# quantum_AnalougeEngine_V5_1.net
KiCad netlist of a schematic drawn in EAGLE
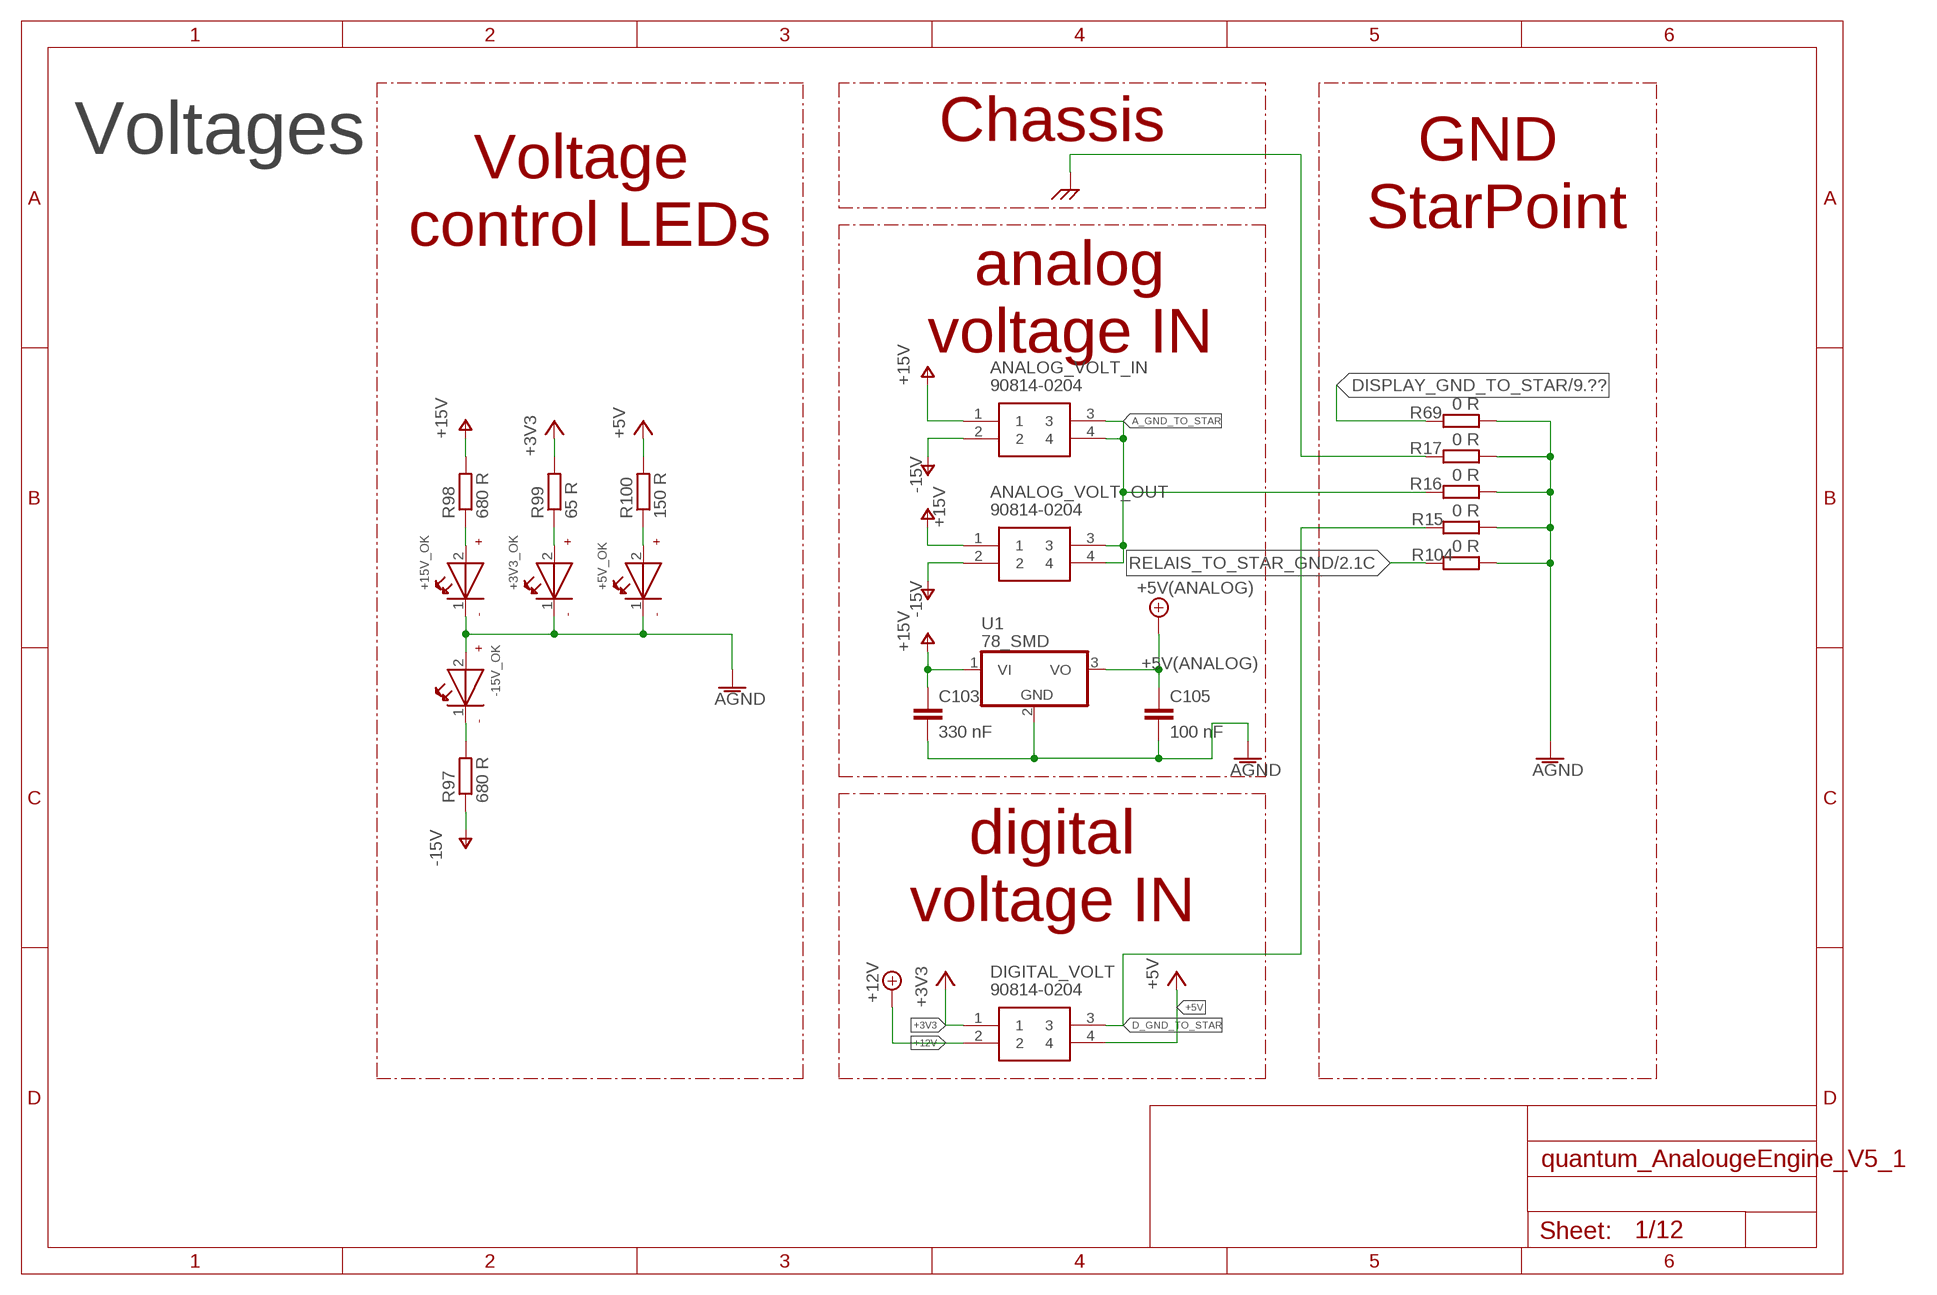
[diagram p0: schematic, sheet 1]
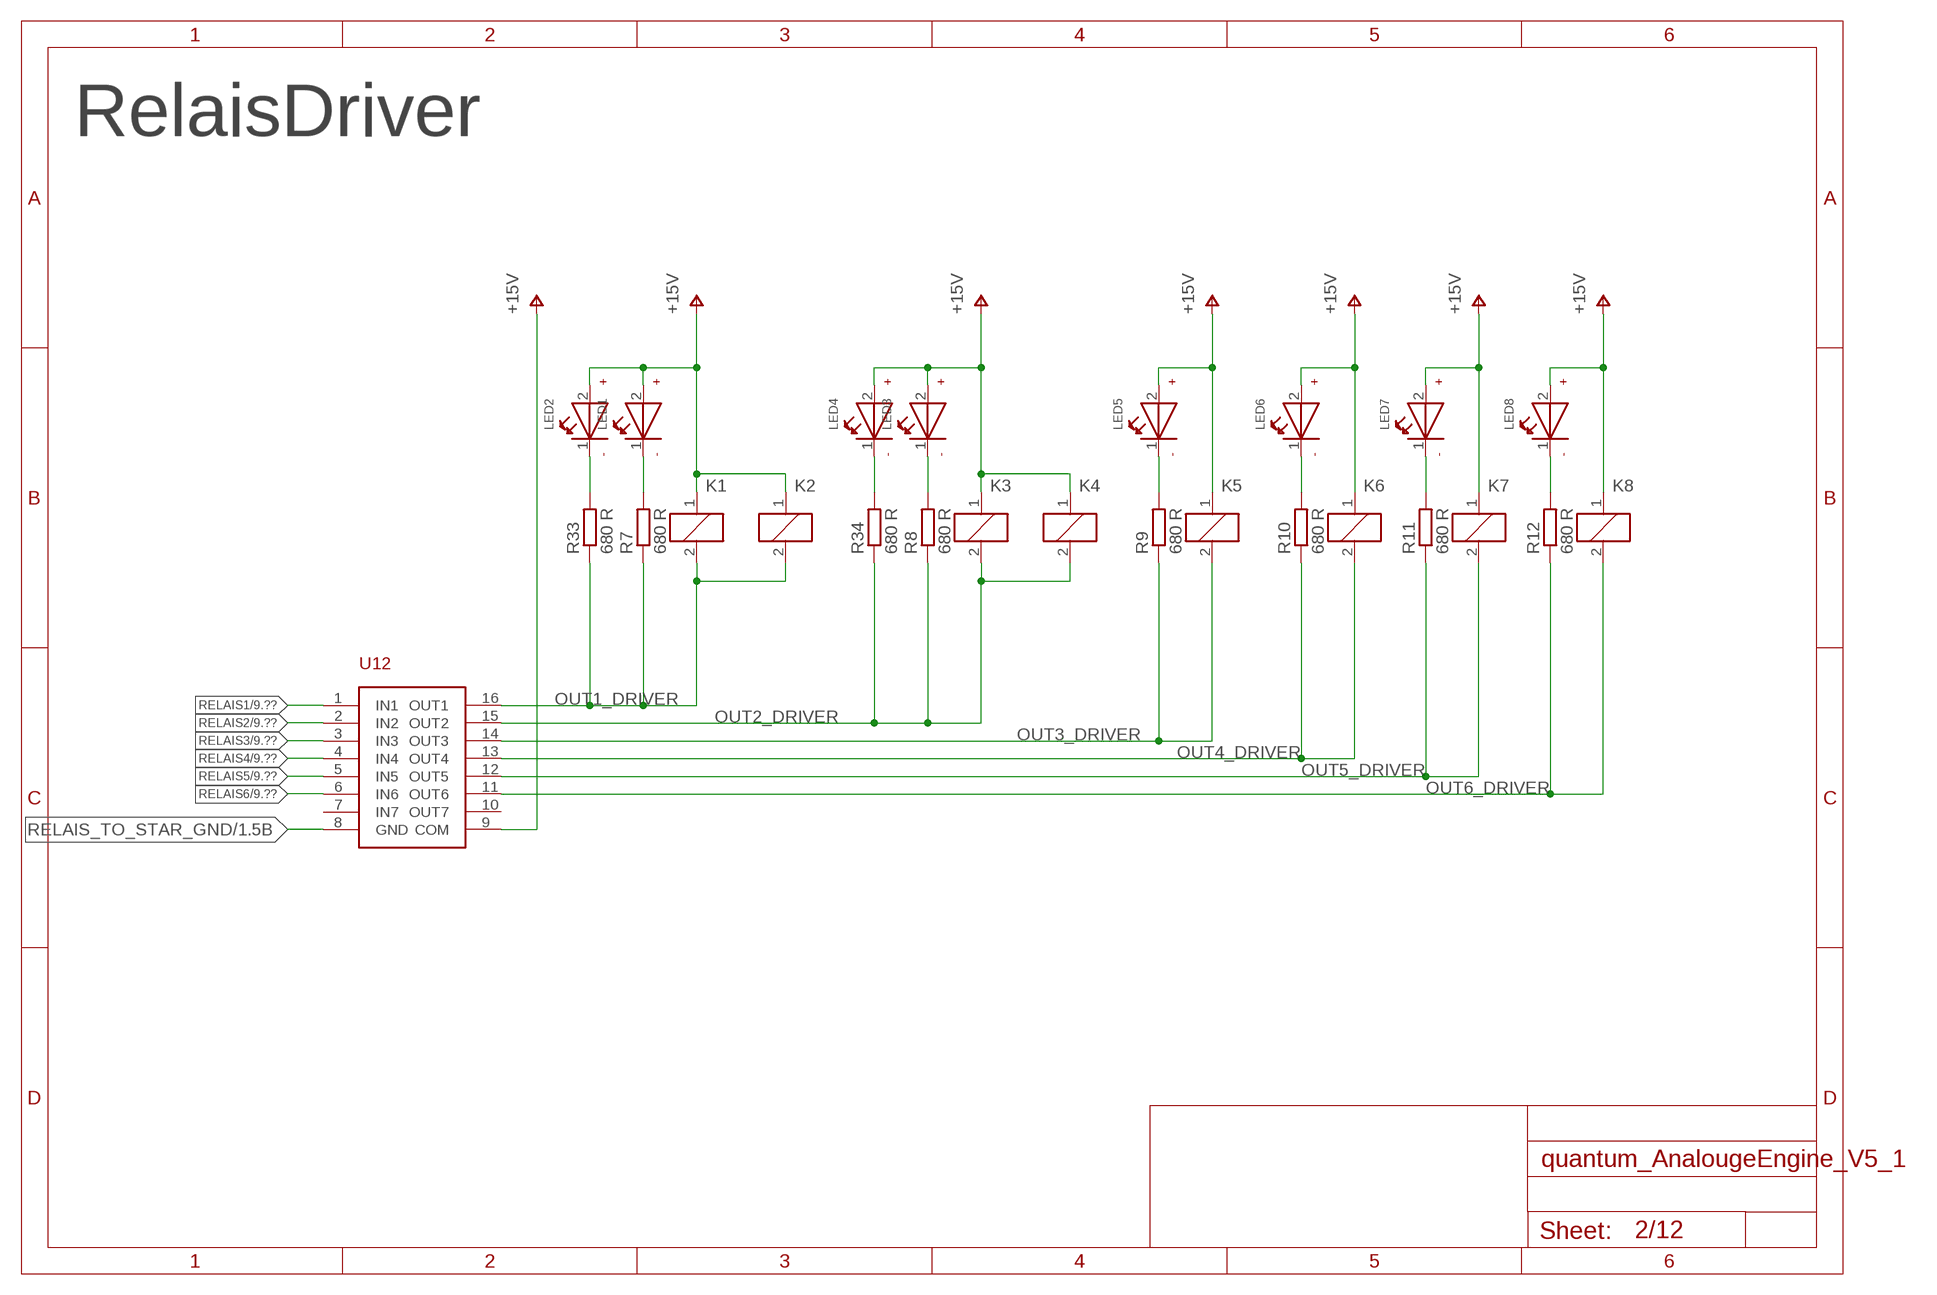
[diagram p1: schematic, sheet 2]
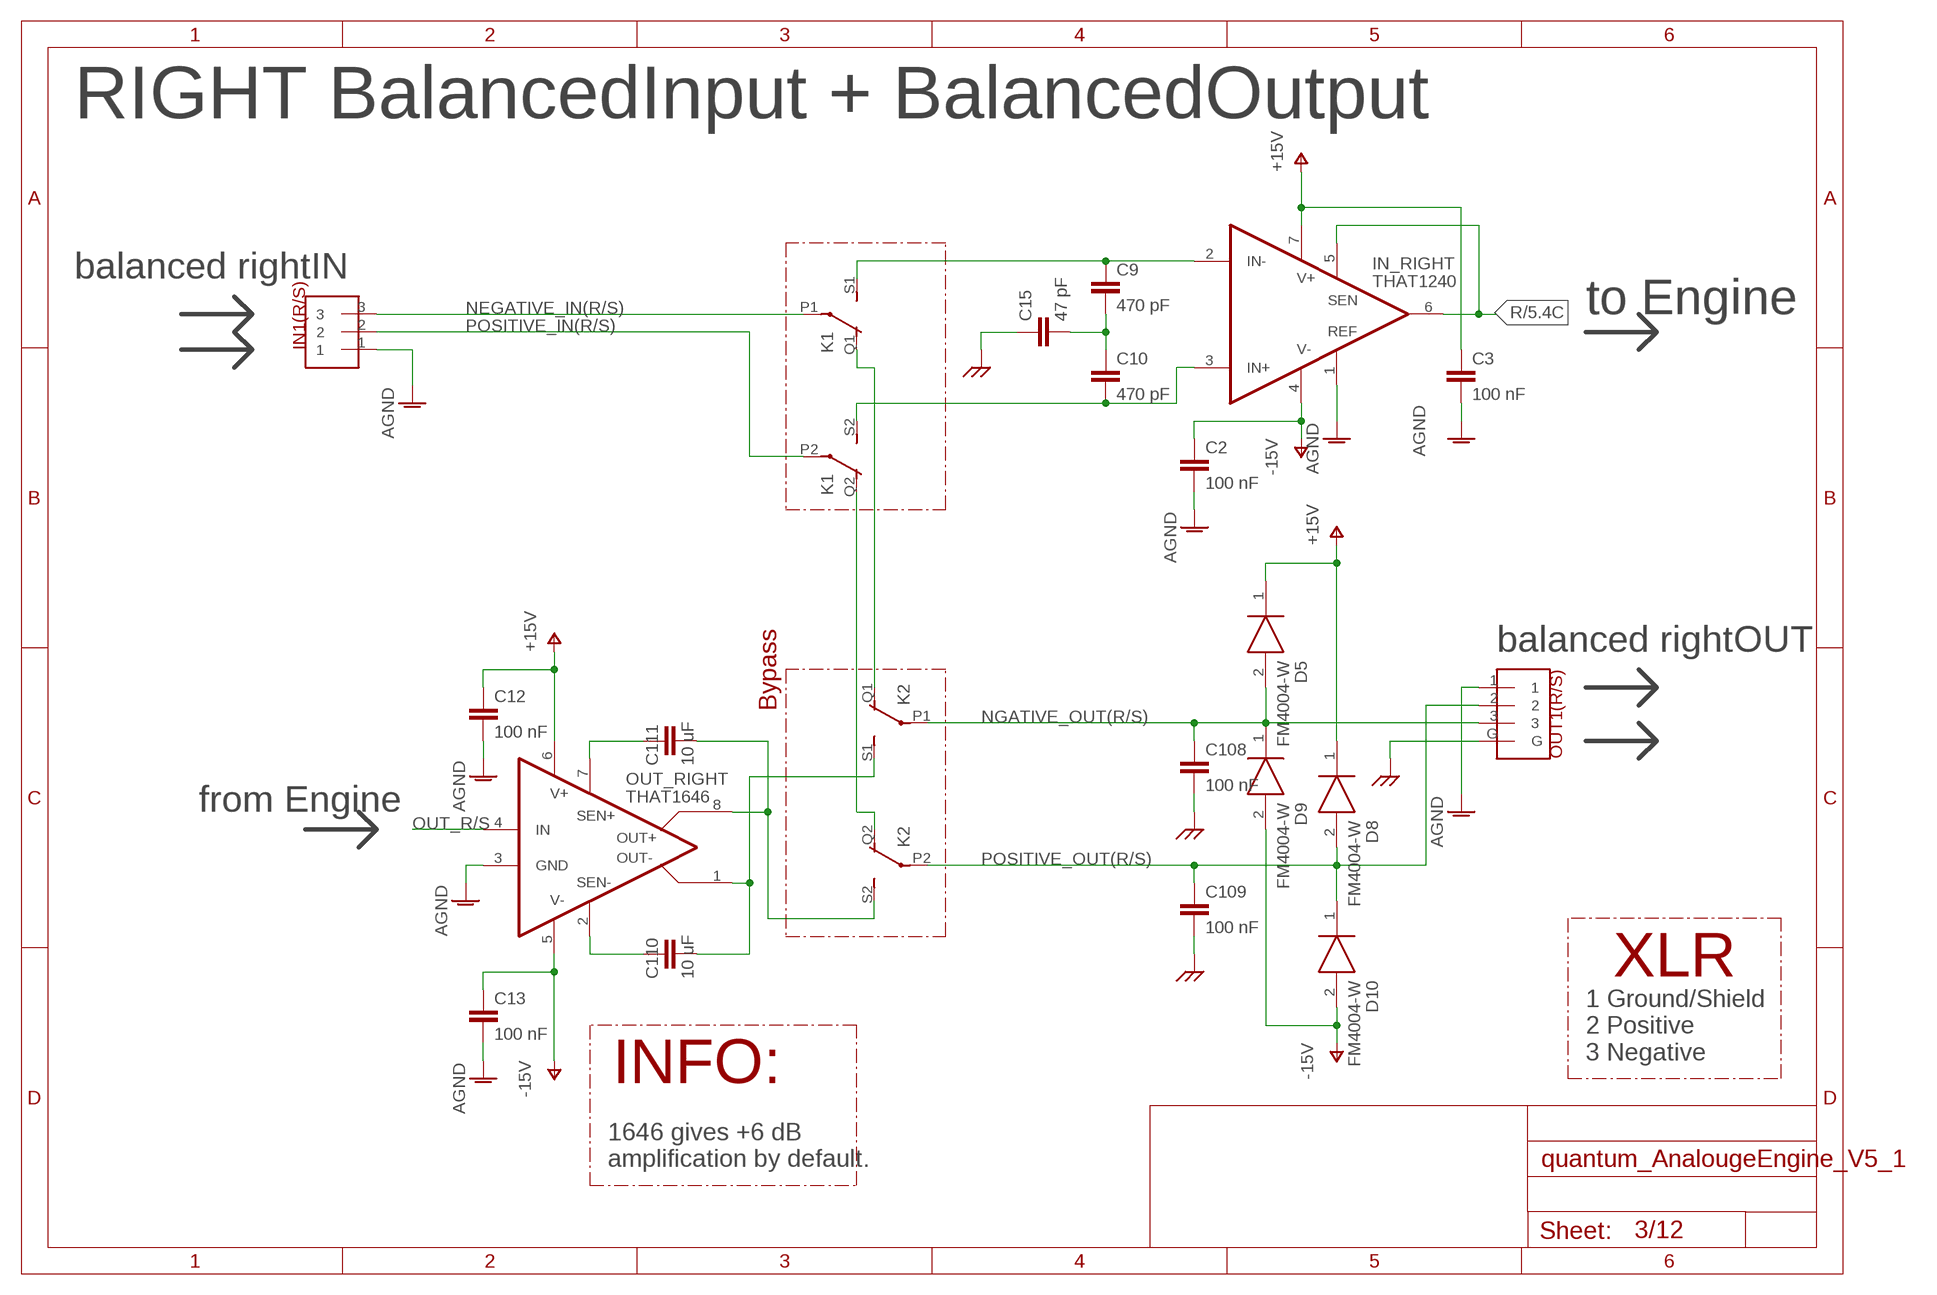
[diagram p2: schematic, sheet 3]
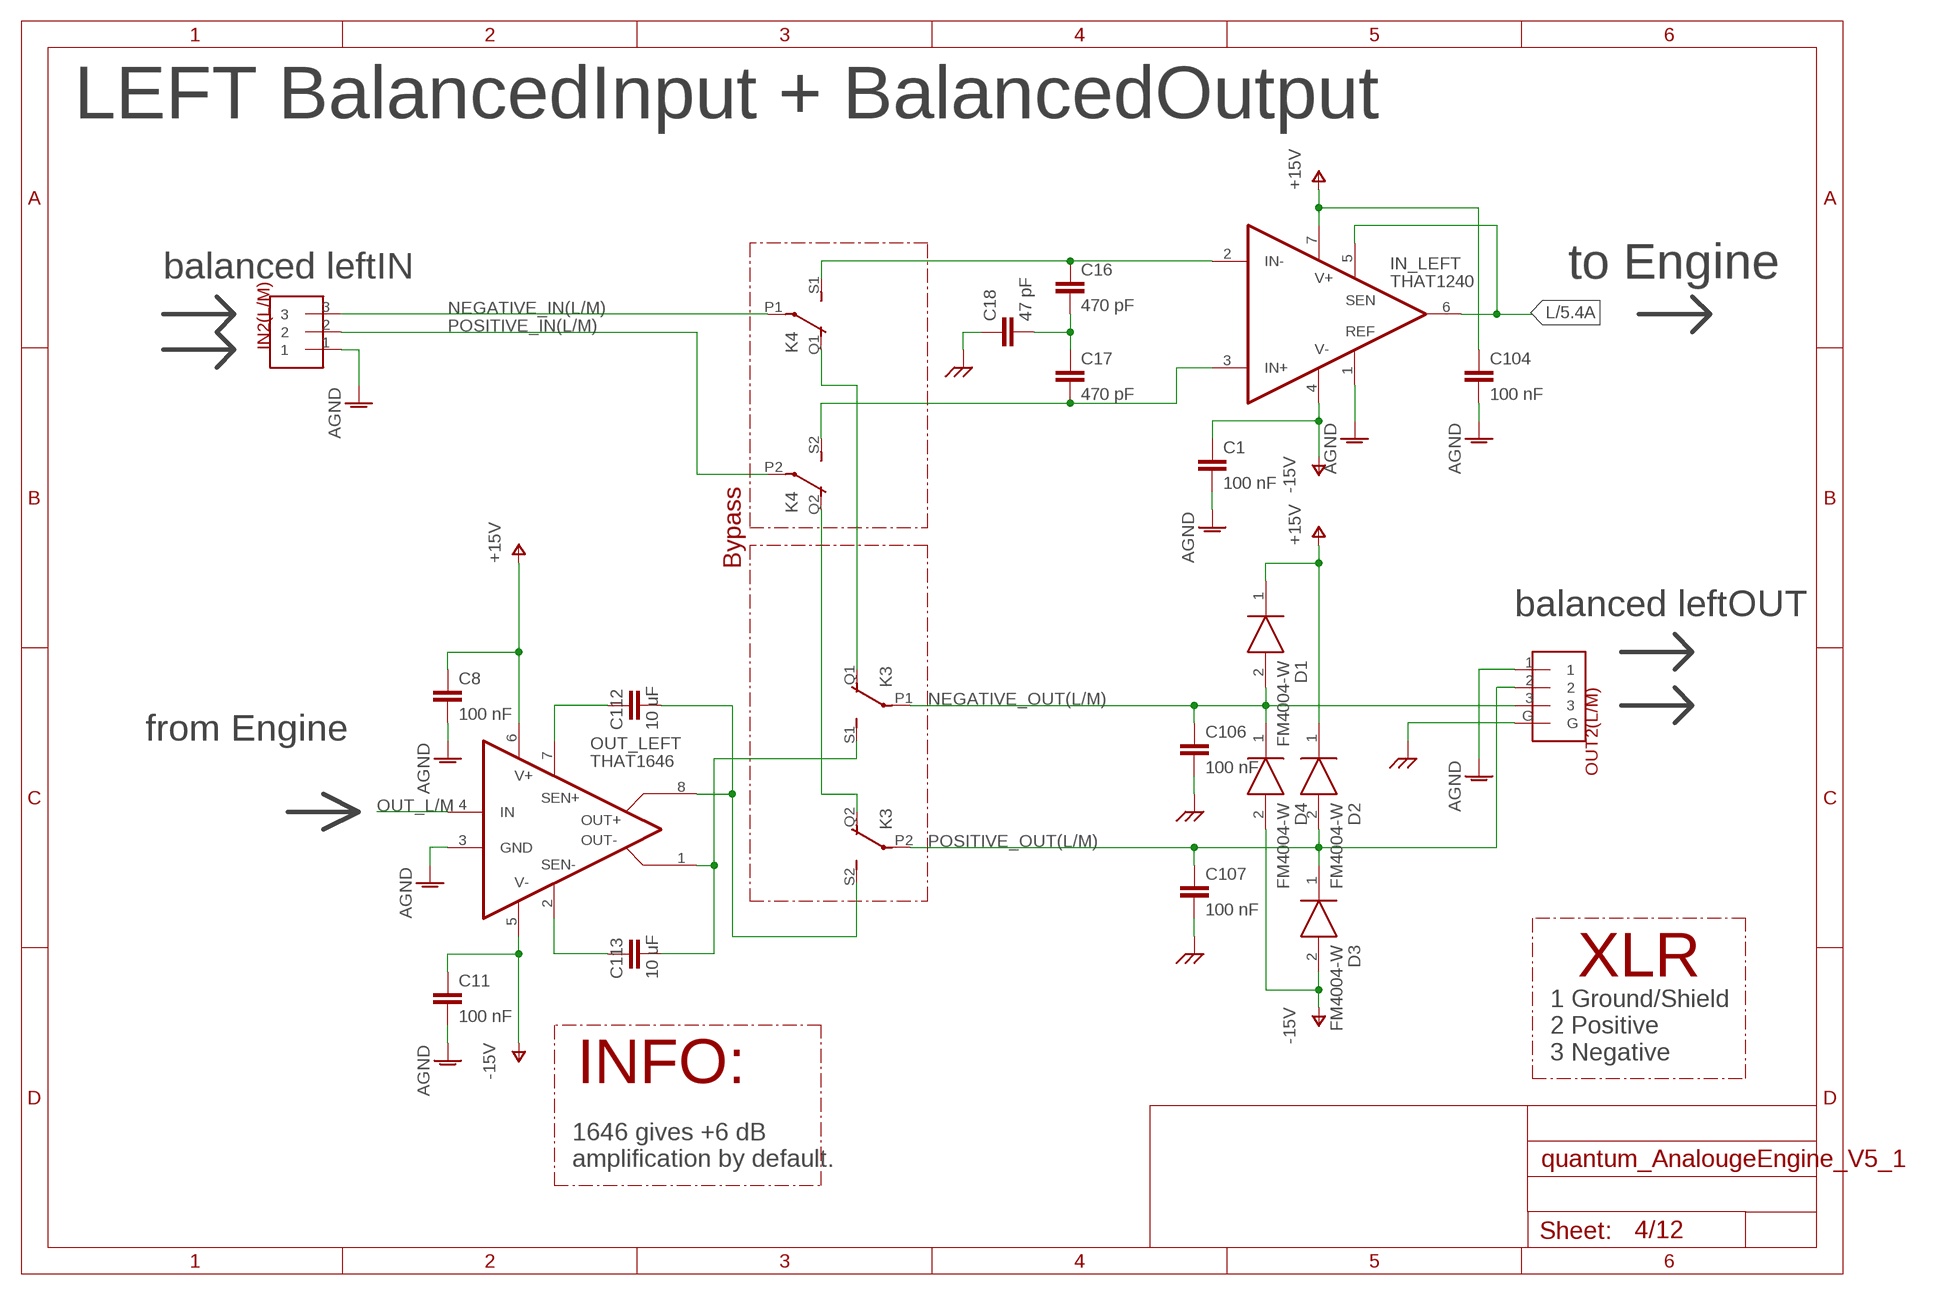
[diagram p3: schematic, sheet 4]
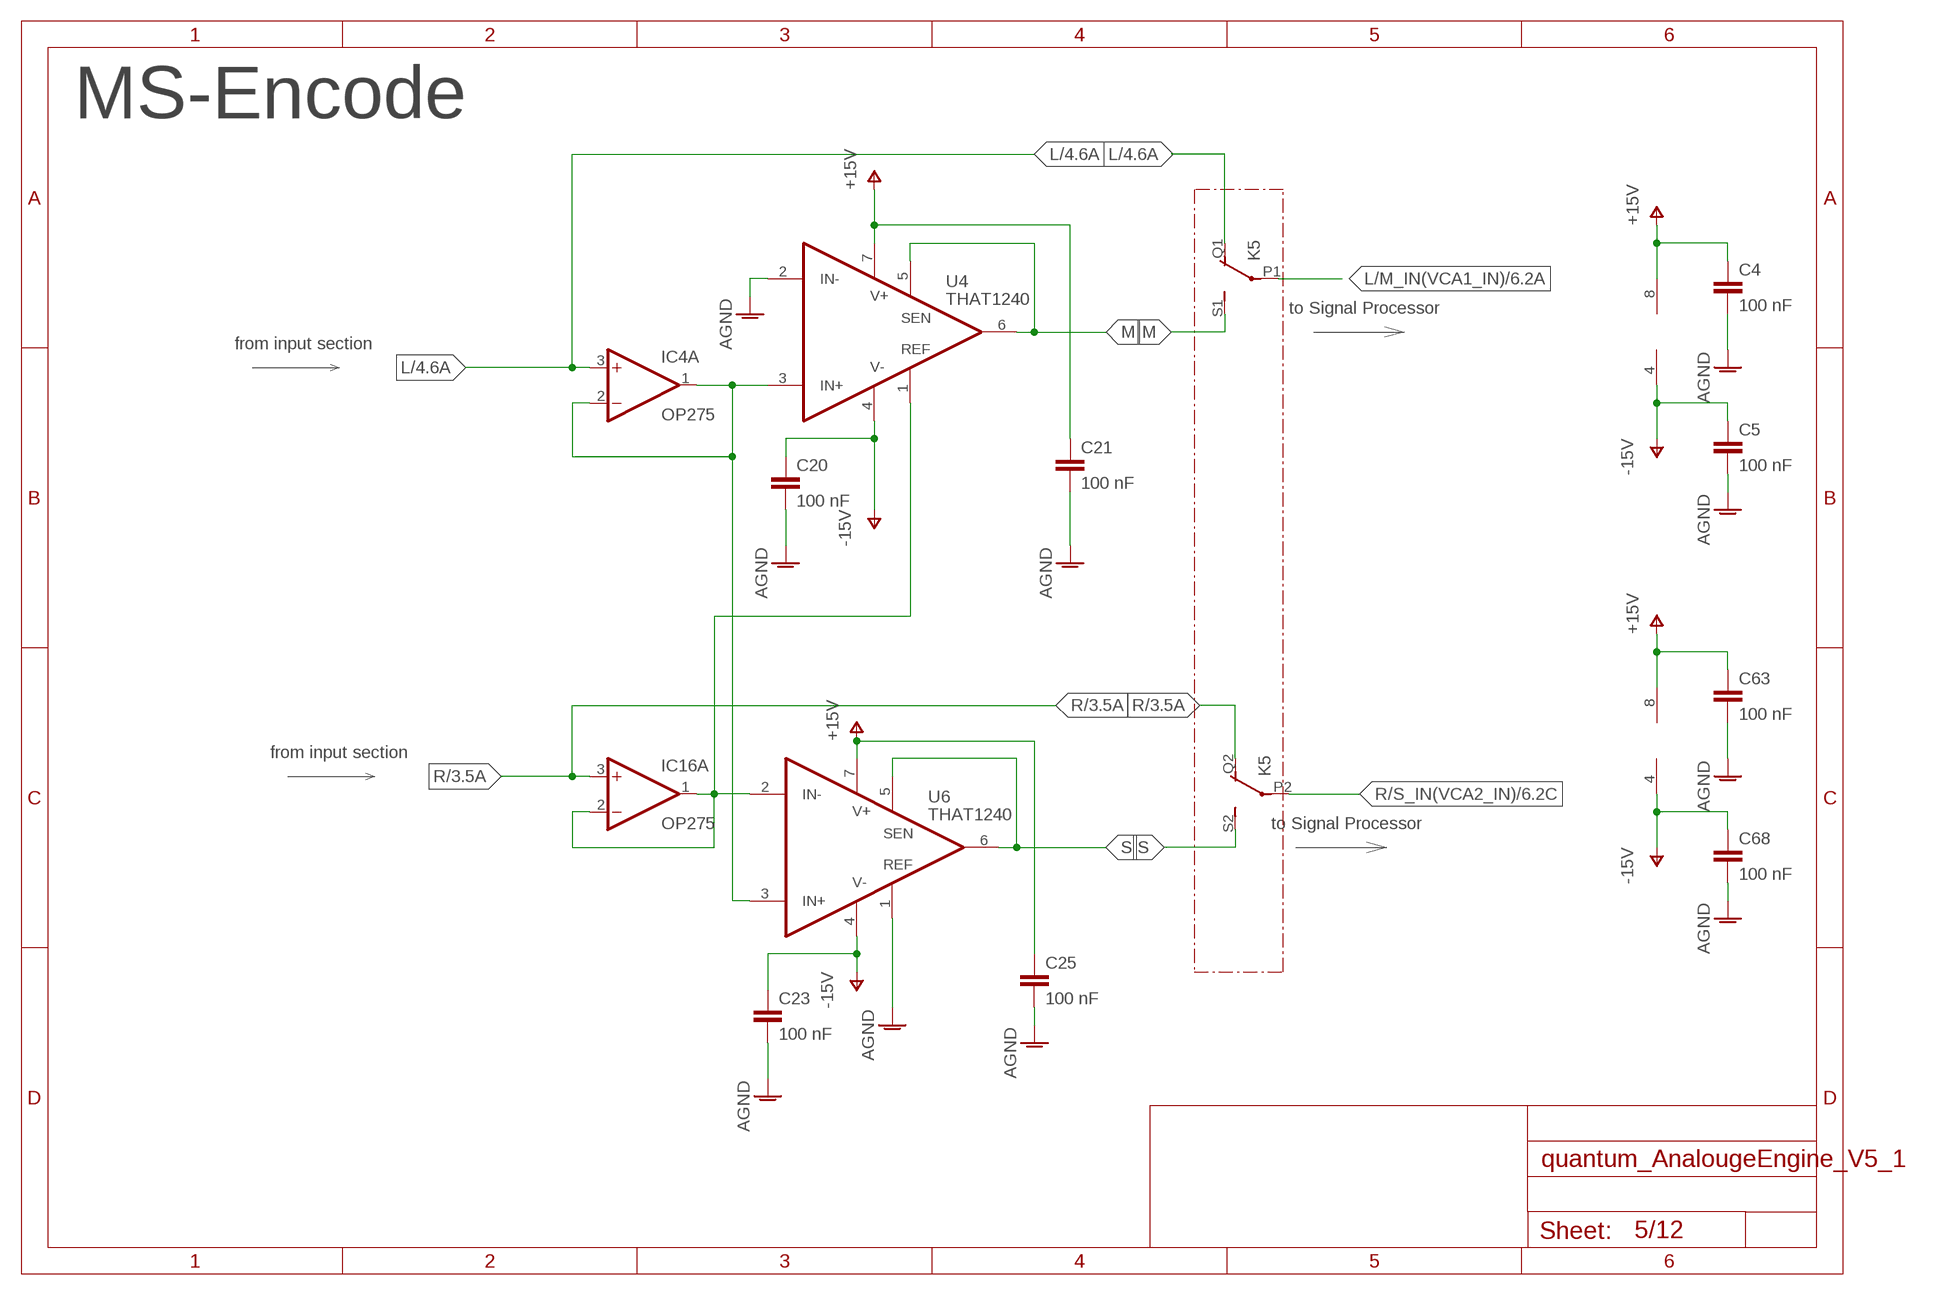
[diagram p4: schematic, sheet 5]
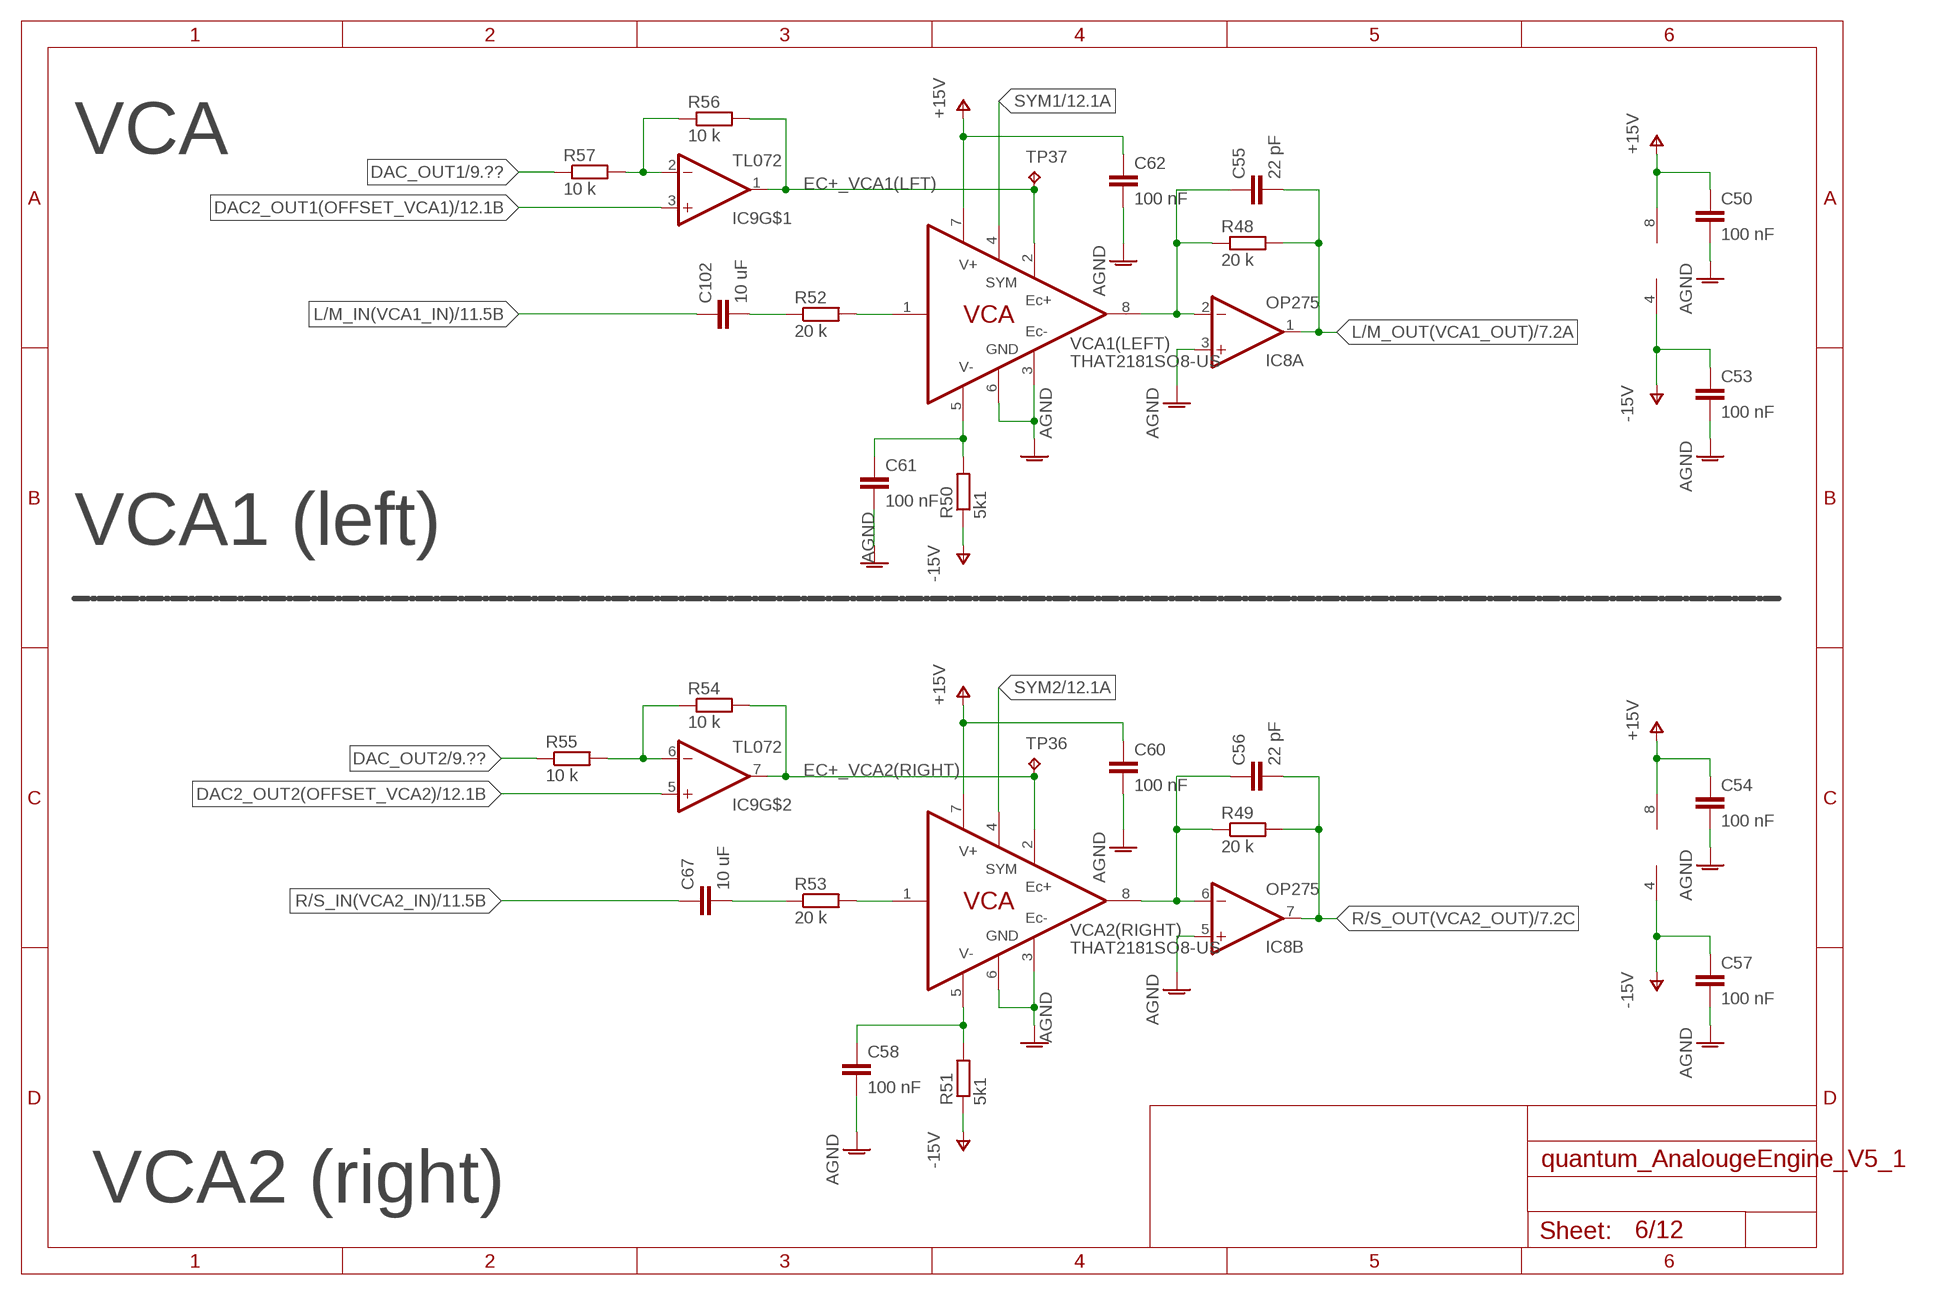
[diagram p5: schematic, sheet 6]
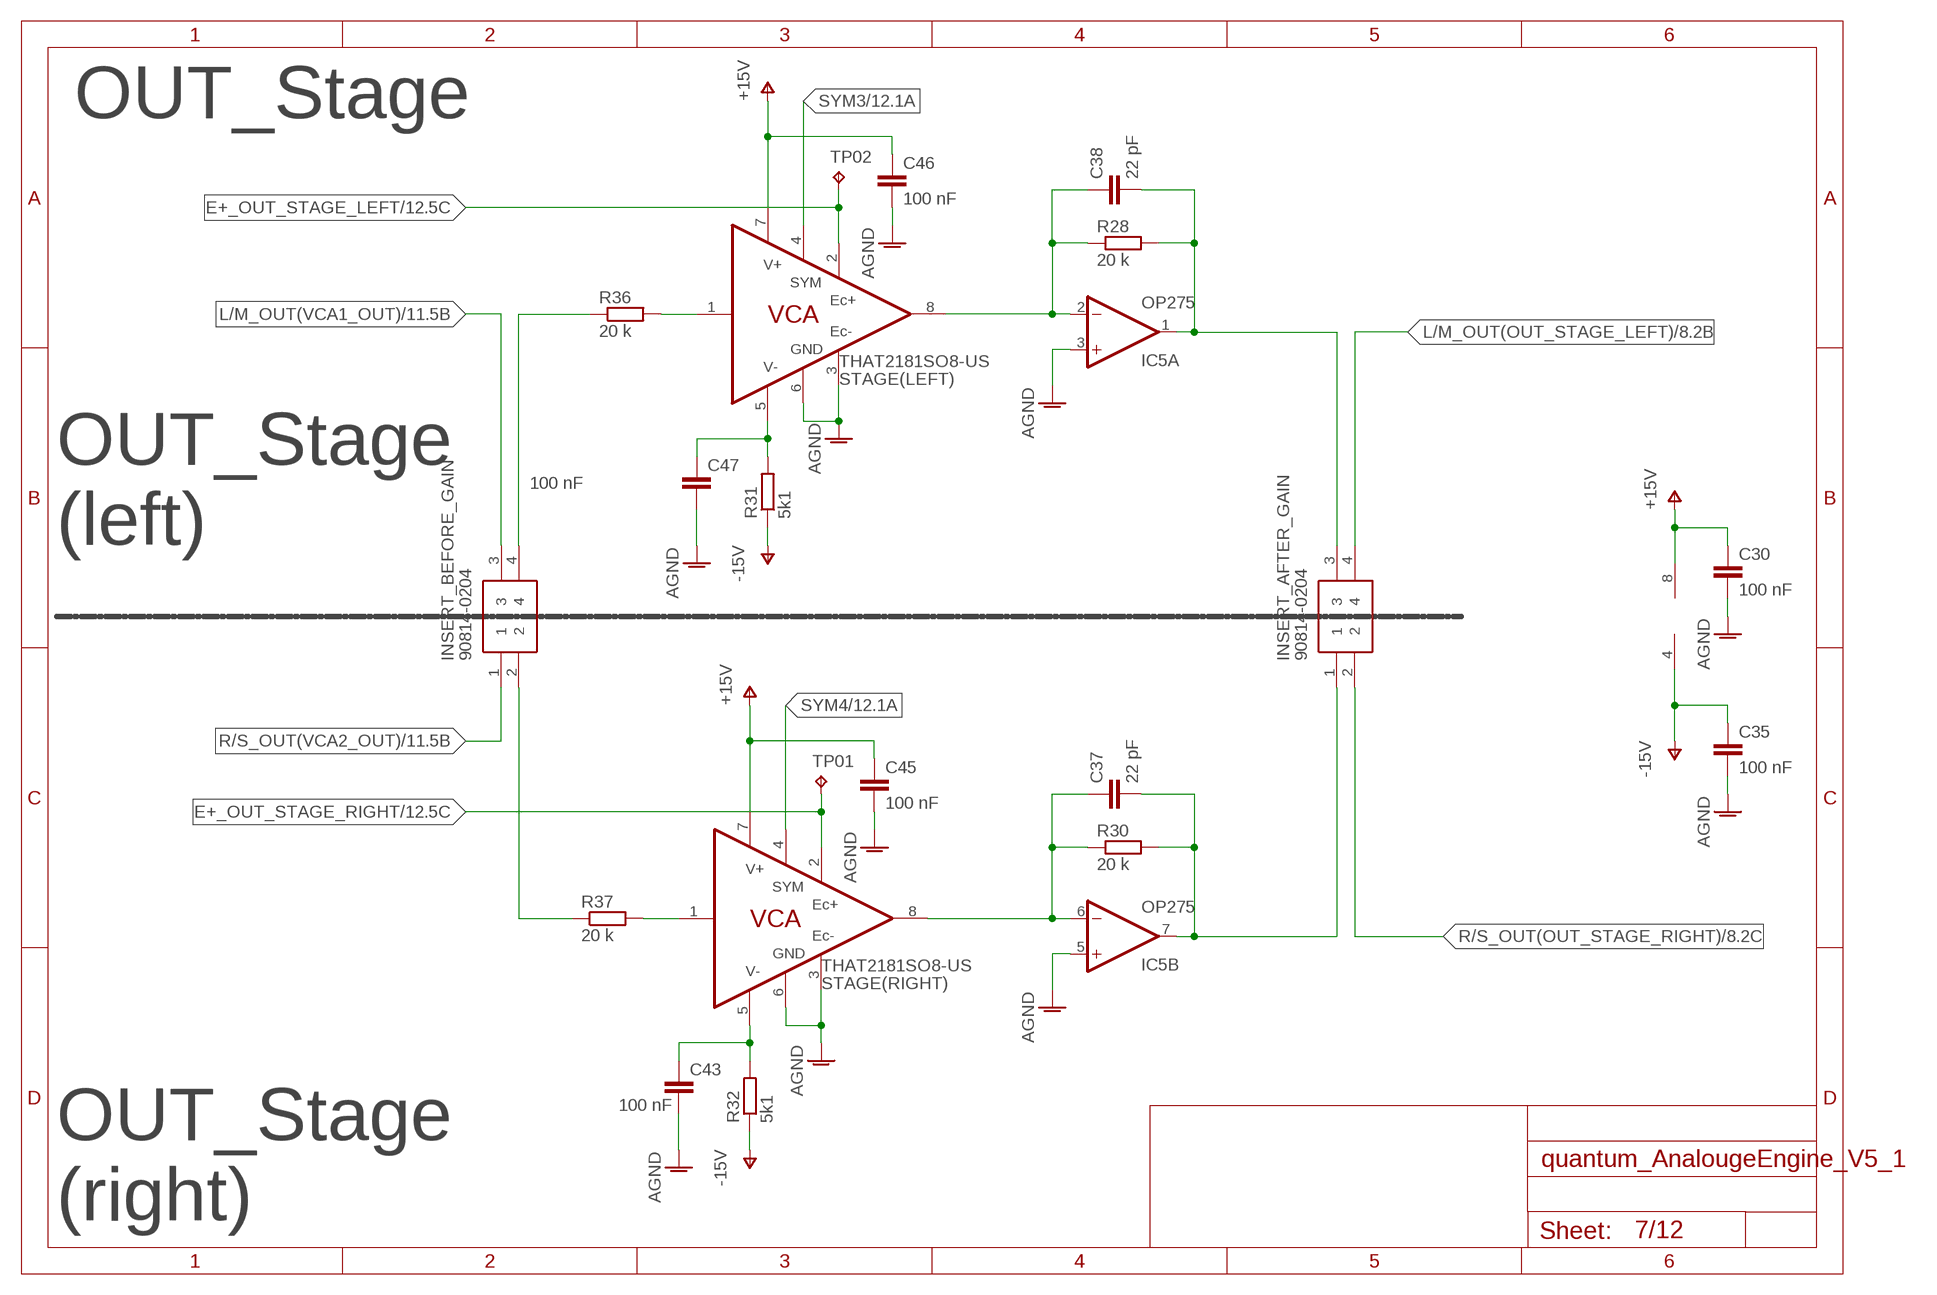
[diagram p6: schematic, sheet 7]
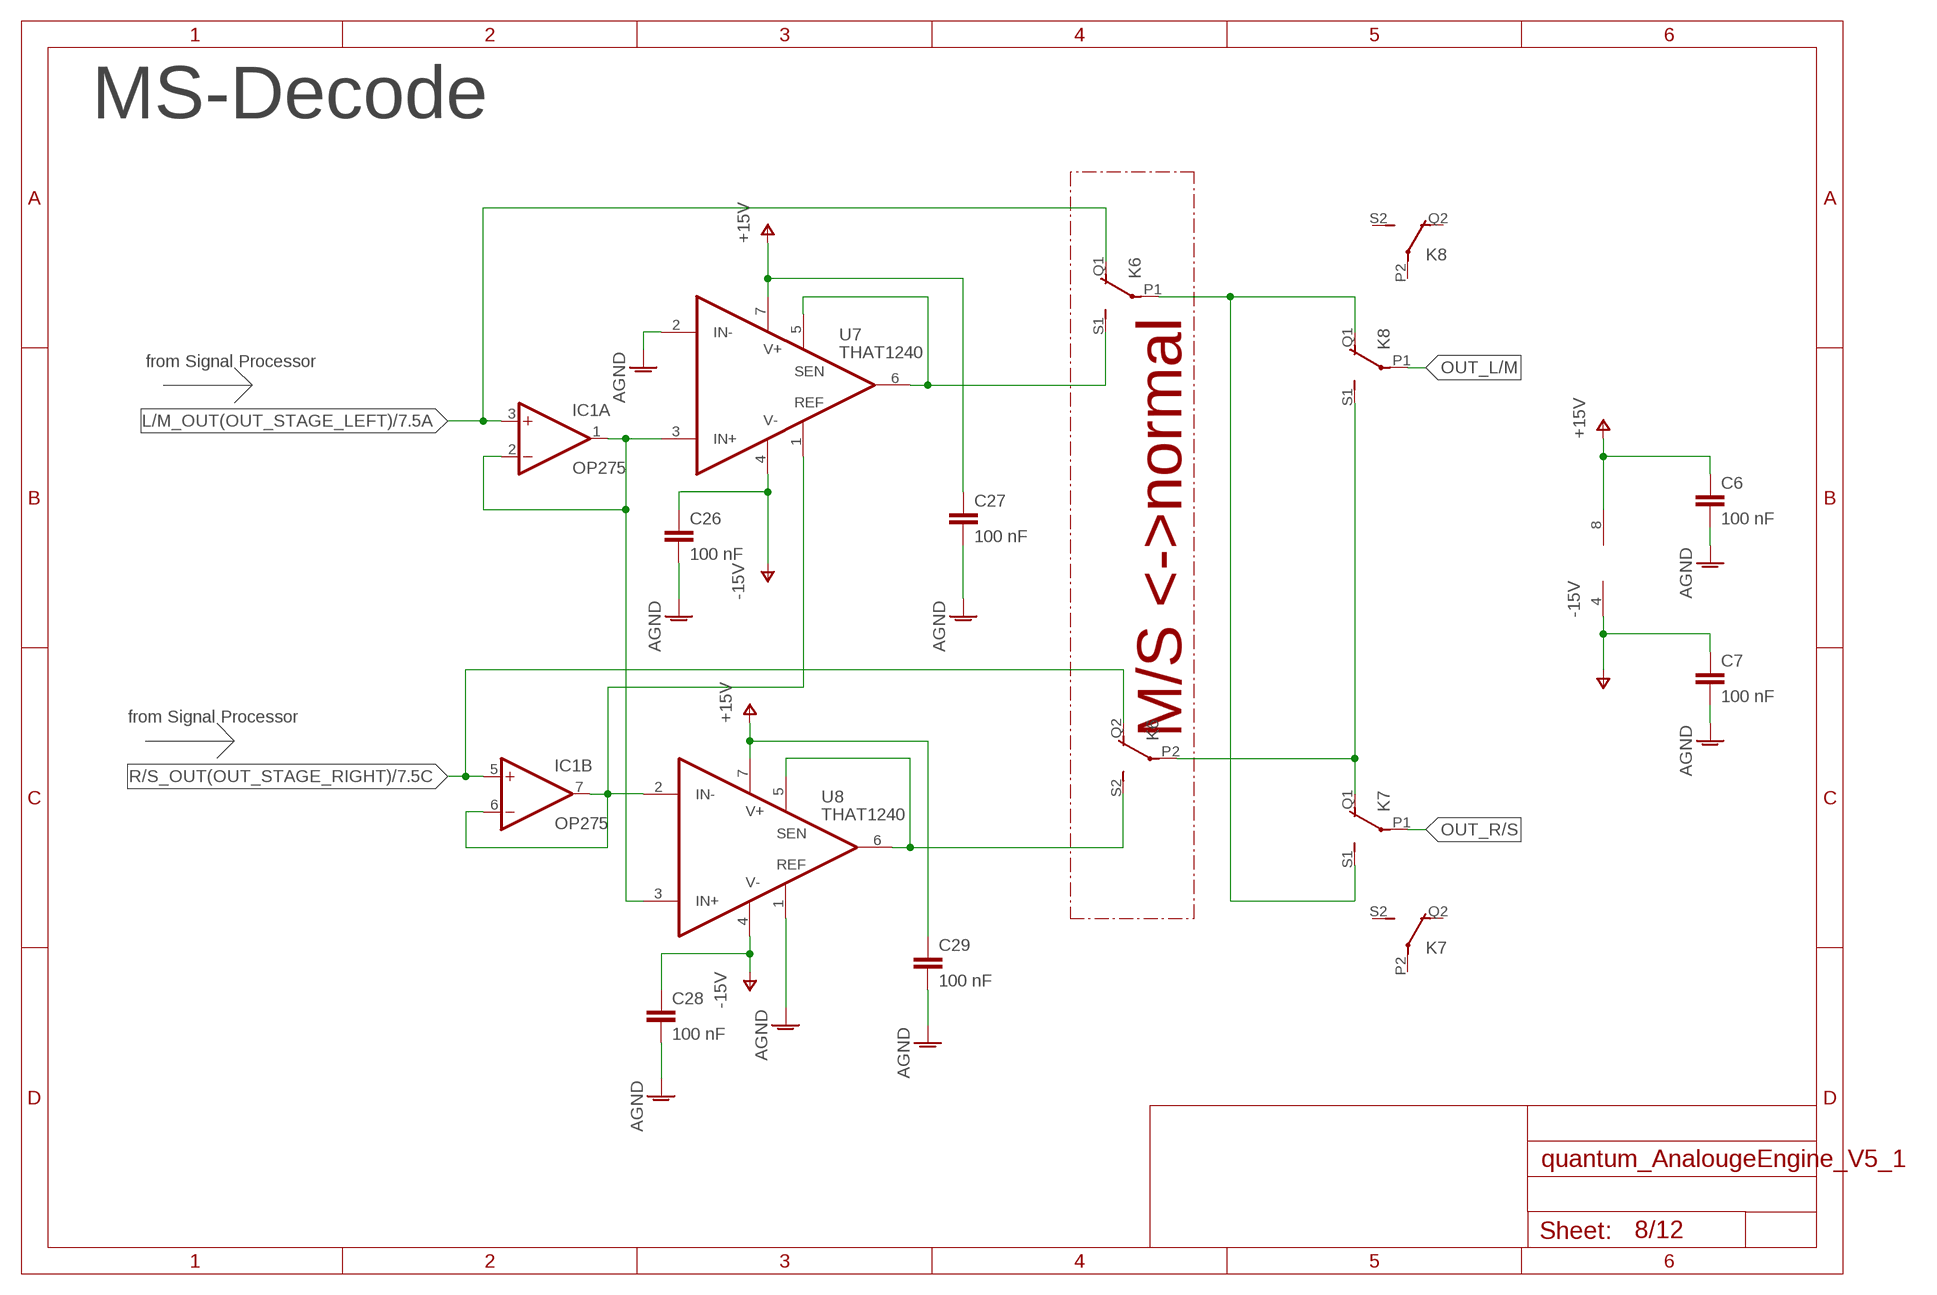
[diagram p7: schematic, sheet 8]
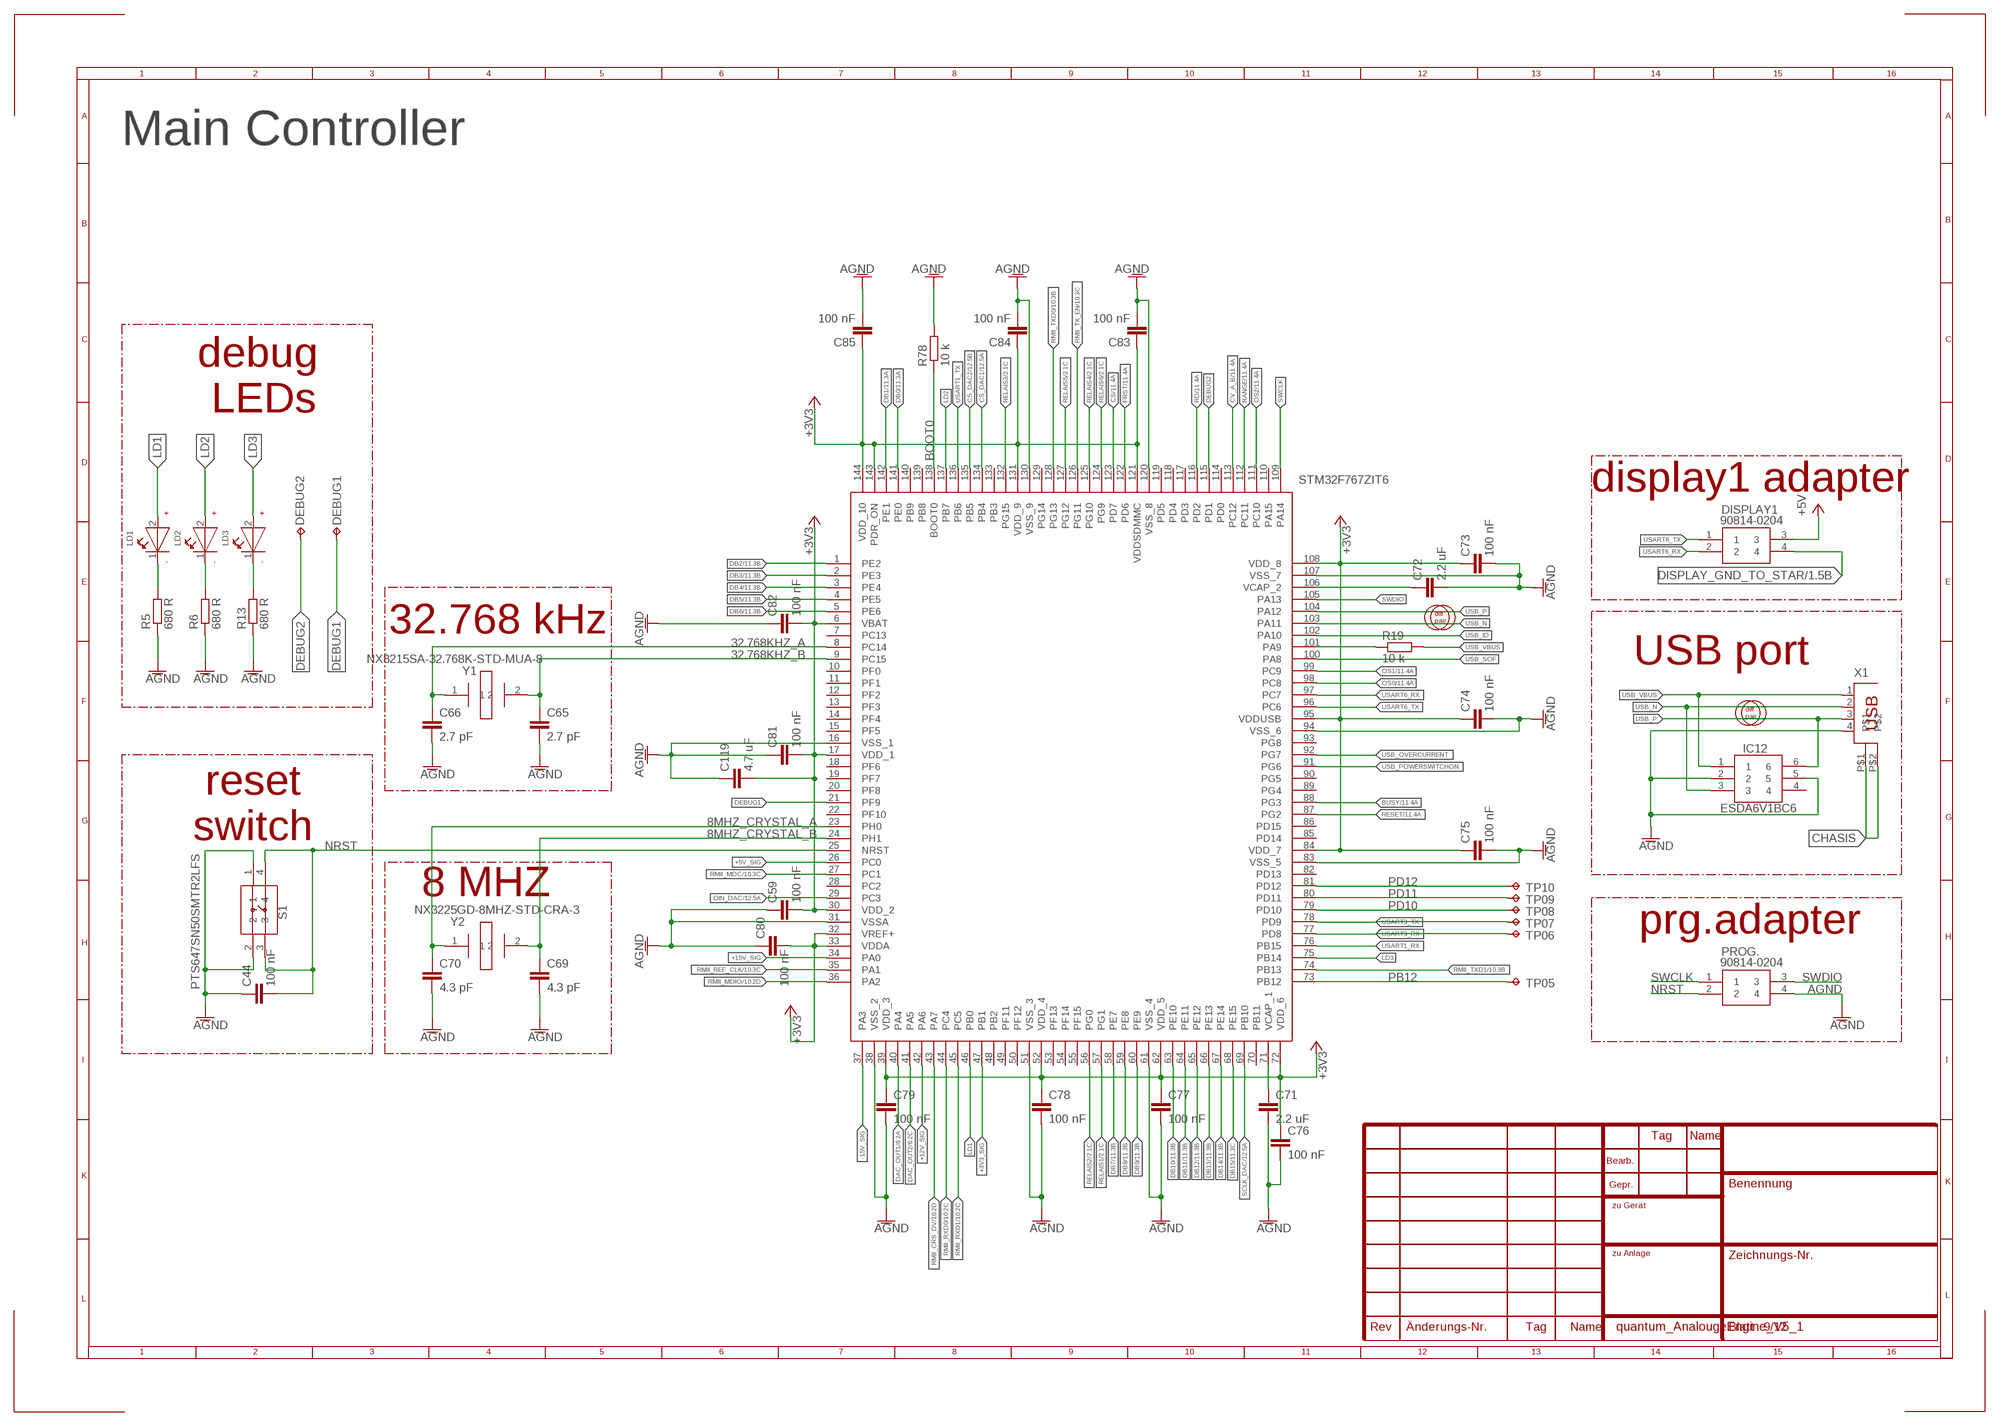
[diagram p8: schematic, sheet 9]
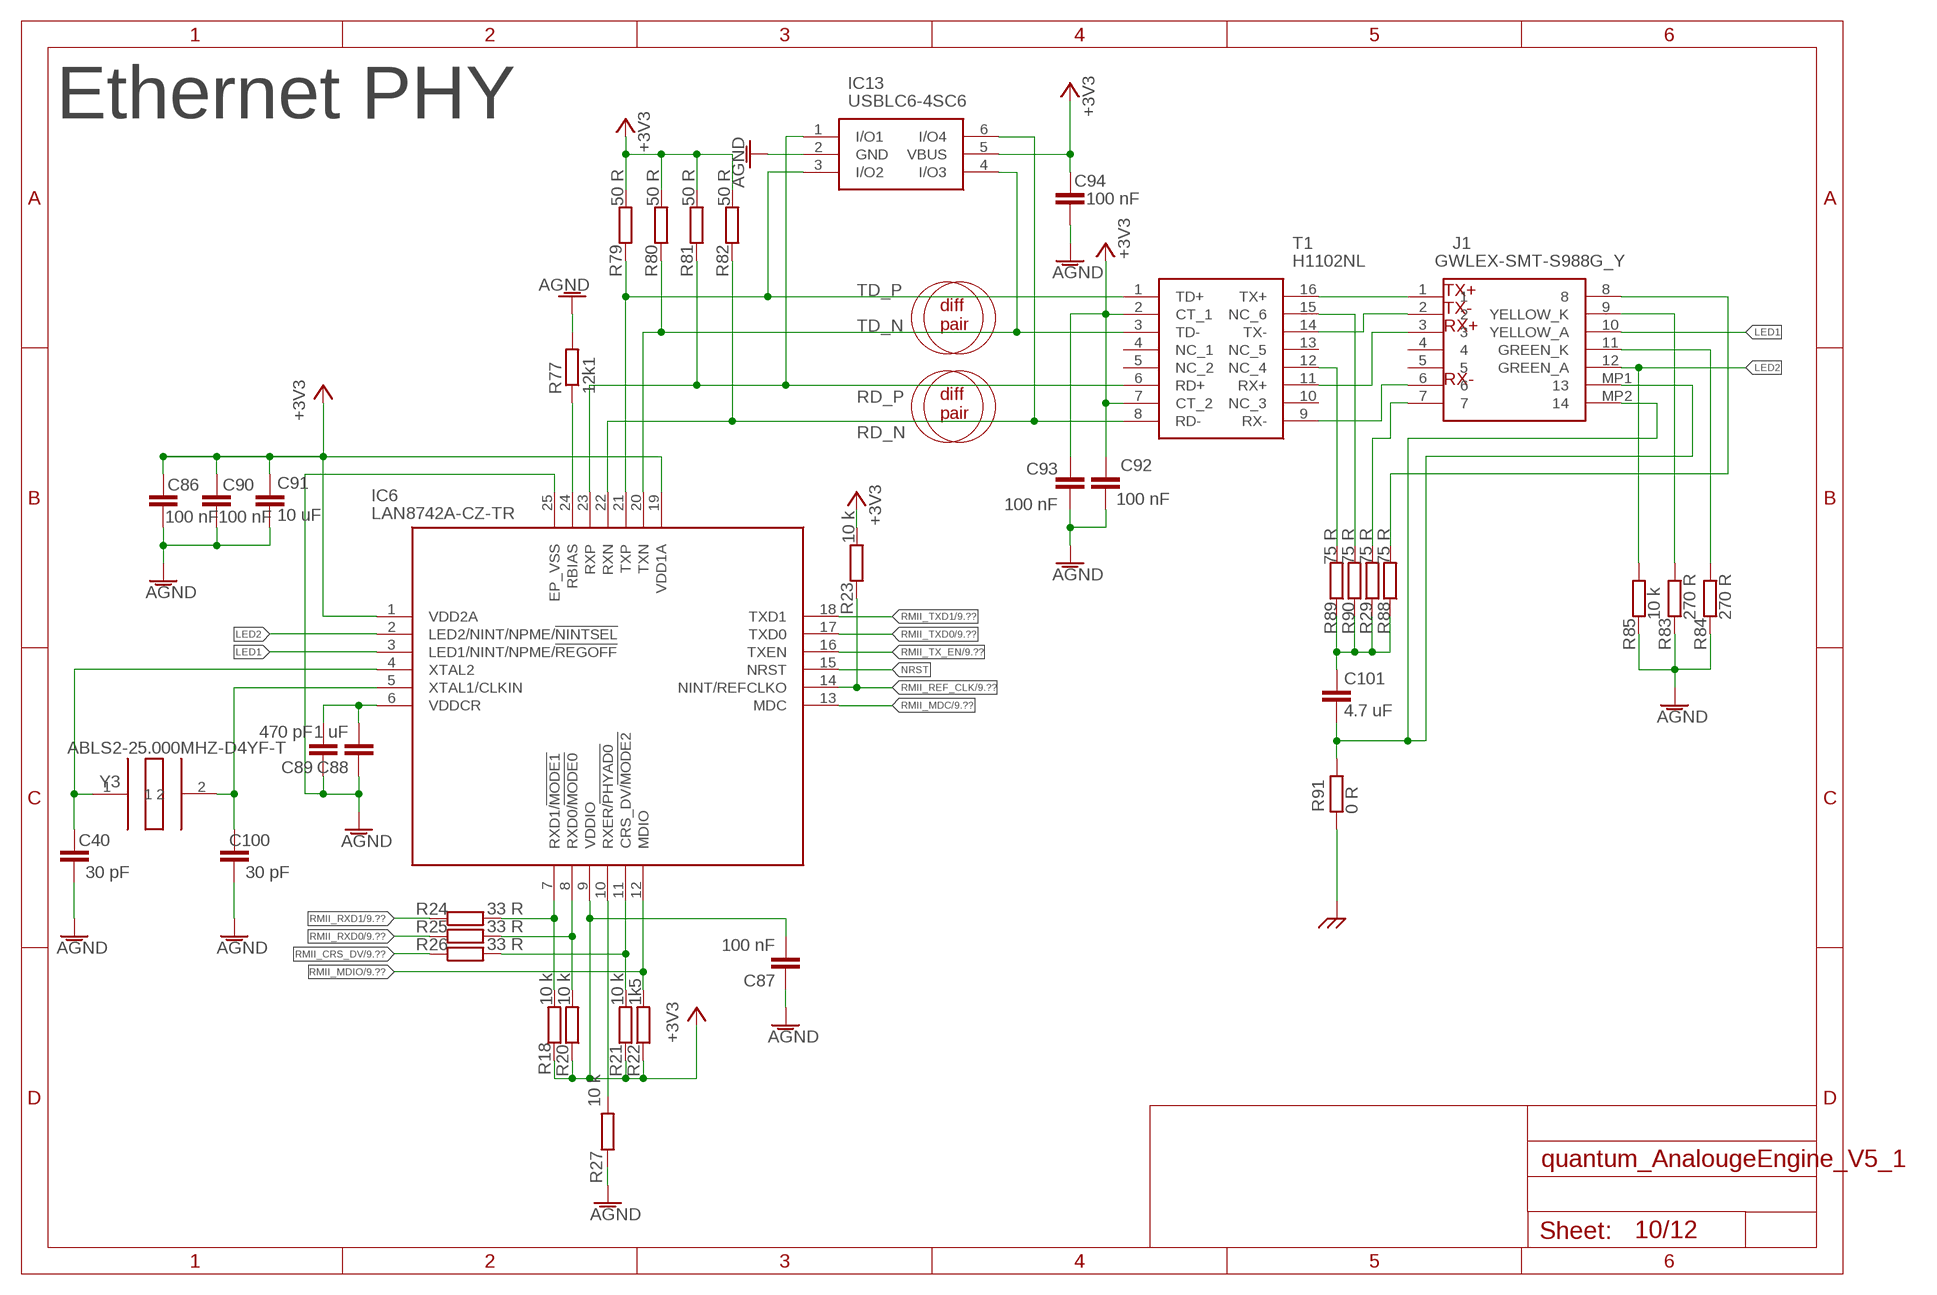
[diagram p9: schematic, sheet 10]
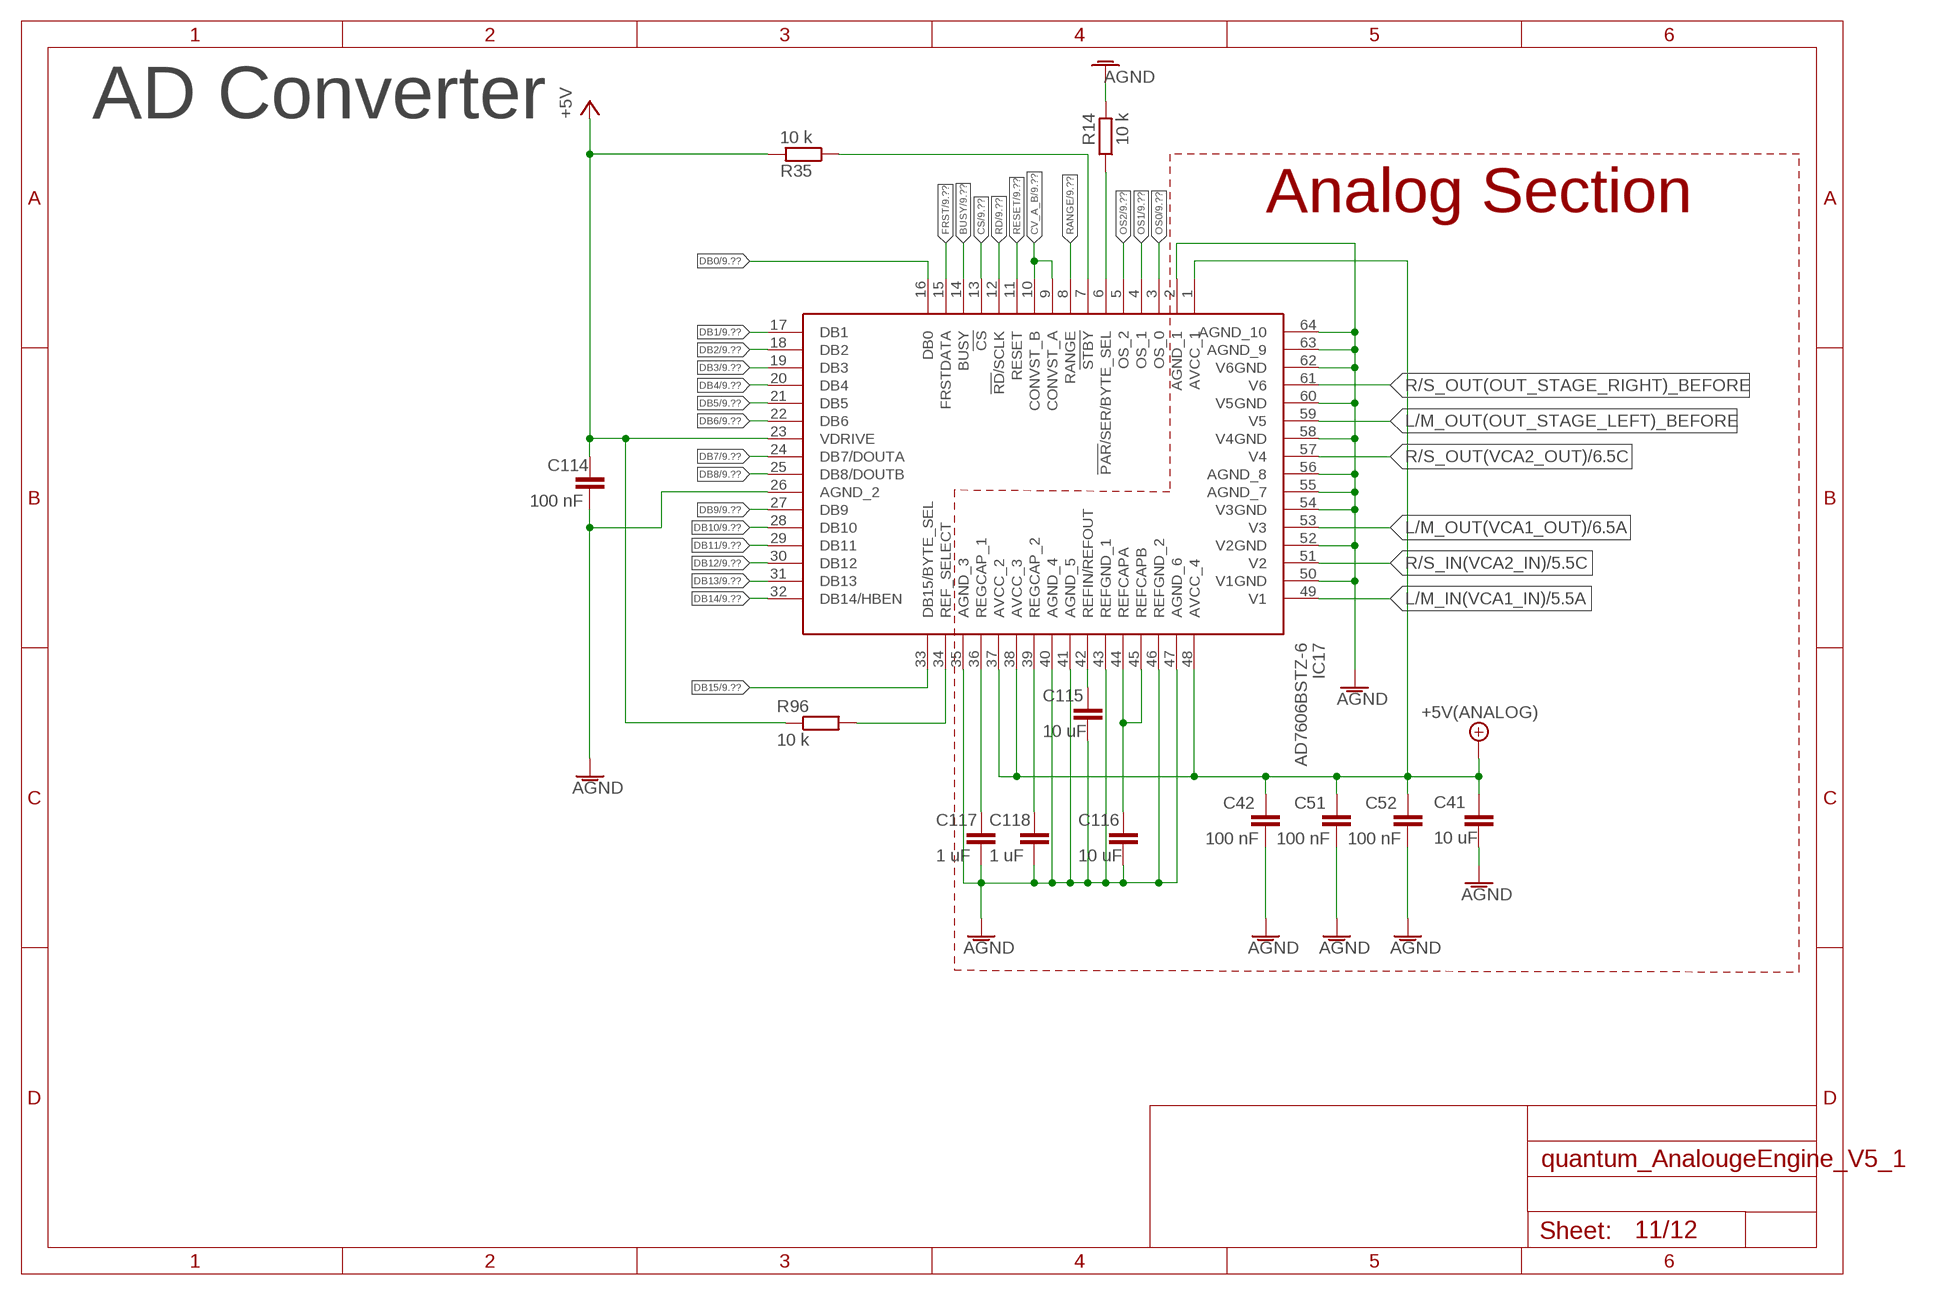
[diagram p10: schematic, sheet 11]
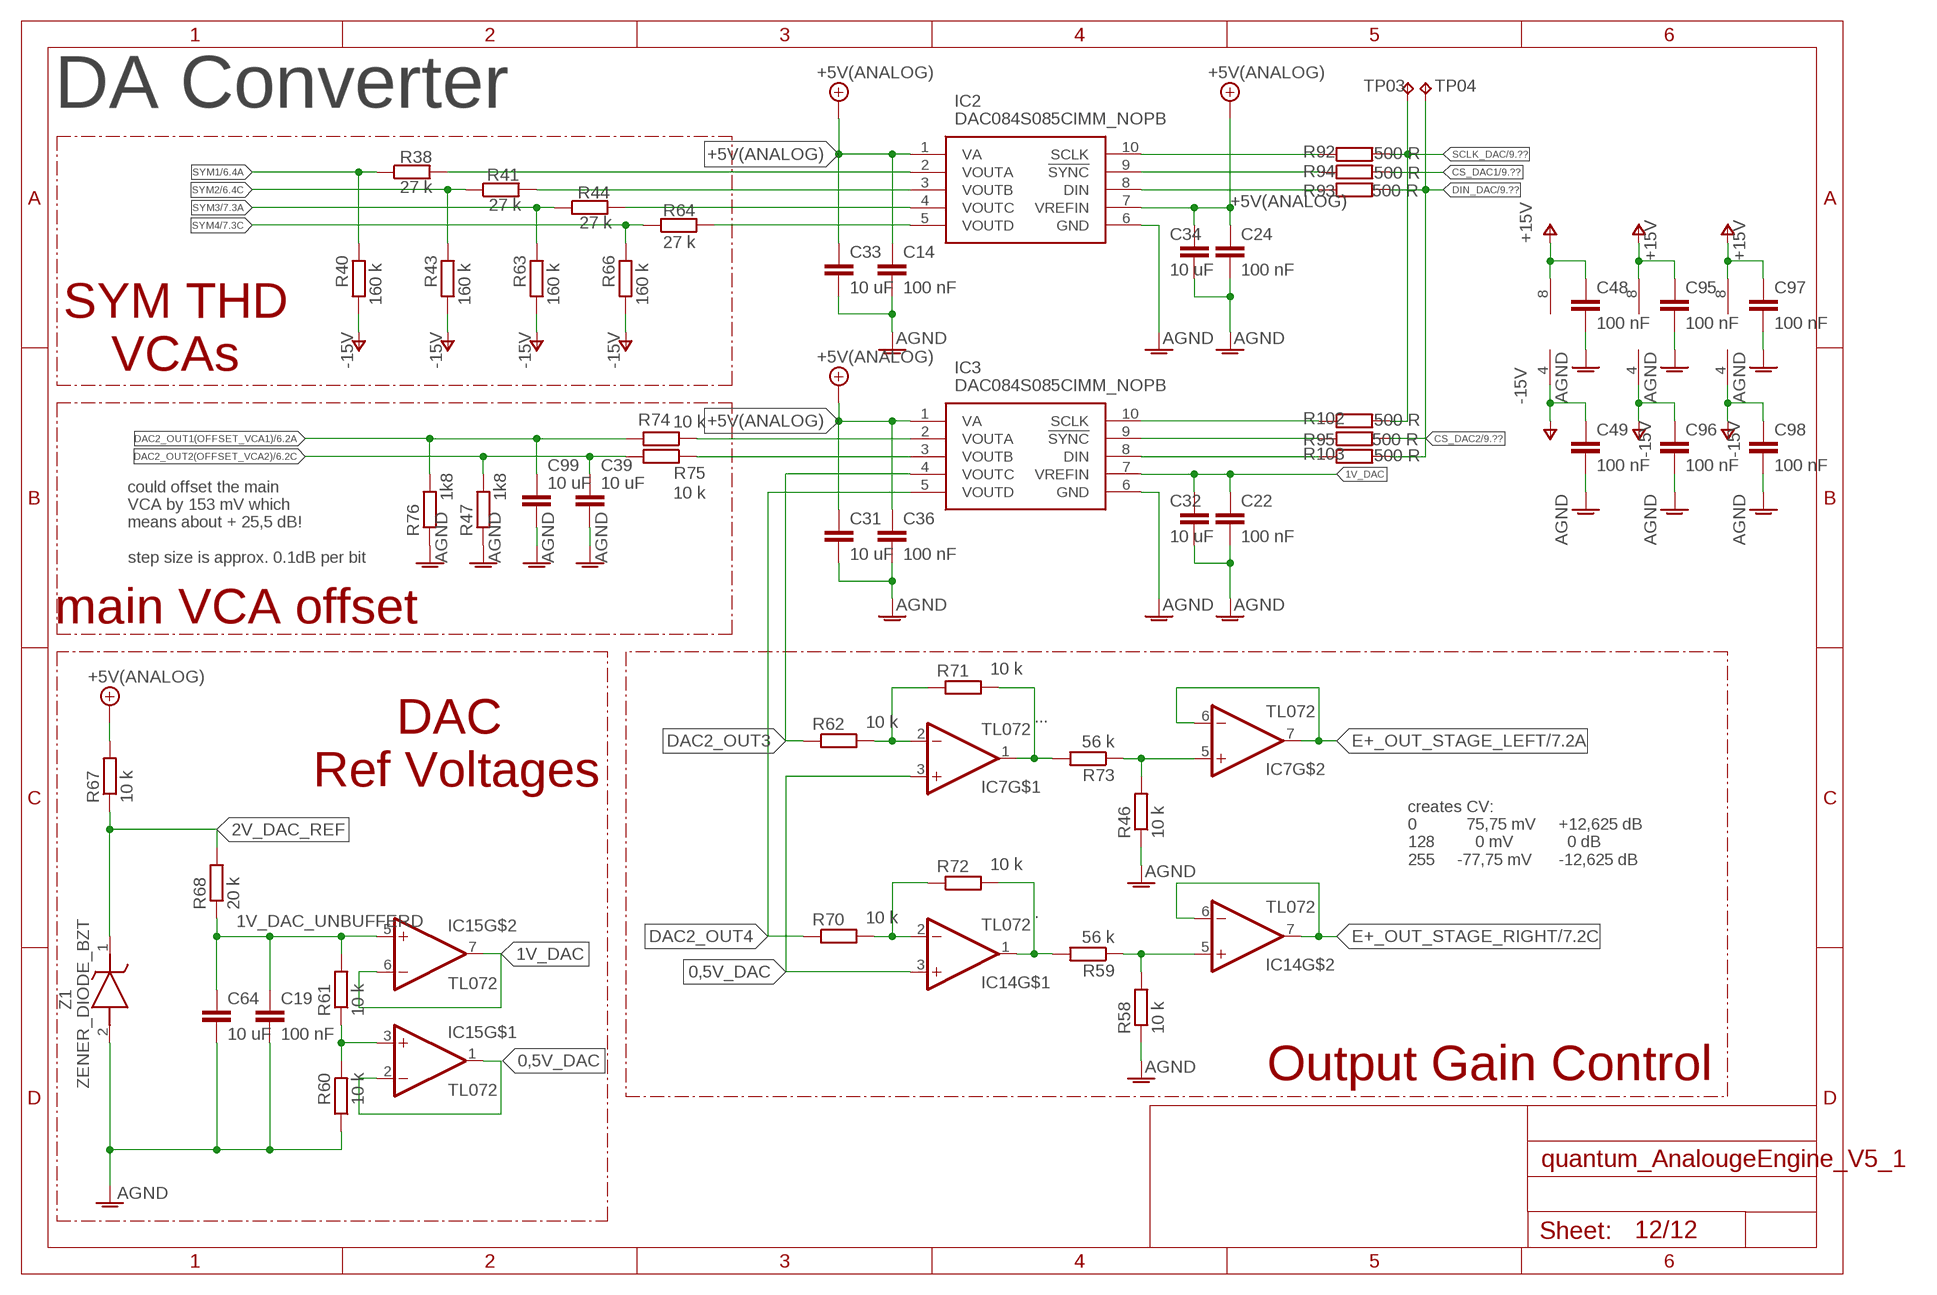
[diagram p11: schematic, sheet 12]

(export (version "E")
  (design (tool "Eeschema 10.0.6"))
  (components
    (comp (ref "C30")
      (value "100 nF")
      (footprint "eagle-import:C0603")
      (libsource (lib "eagle-import") (part "CAPACITOR_0603"))
    )
    (comp (ref "C35")
      (value "100 nF")
      (footprint "eagle-import:C0603")
      (libsource (lib "eagle-import") (part "CAPACITOR_0603"))
    )
    (comp (ref "C37")
      (value "22 pF")
      (footprint "eagle-import:C0603")
      (libsource (lib "eagle-import") (part "CAPACITOR_0603"))
    )
    (comp (ref "C38")
      (value "22 pF")
      (footprint "eagle-import:C0603")
      (libsource (lib "eagle-import") (part "CAPACITOR_0603"))
    )
    (comp (ref "C43")
      (value "100 nF")
      (footprint "eagle-import:C0603")
      (libsource (lib "eagle-import") (part "CAPACITOR_0603"))
    )
    (comp (ref "C45")
      (value "100 nF")
      (footprint "eagle-import:C0603")
      (libsource (lib "eagle-import") (part "CAPACITOR_0603"))
    )
    (comp (ref "C46")
      (value "100 nF")
      (footprint "eagle-import:C0603")
      (libsource (lib "eagle-import") (part "CAPACITOR_0603"))
    )
    (comp (ref "C47")
      (value "100 nF")
      (footprint "eagle-import:C0603")
      (libsource (lib "eagle-import") (part "CAPACITOR_0603"))
    )
    (comp (ref "IC5")
      (value "OP275")
      (footprint "eagle-import:SOIC8")
      (libsource (lib "eagle-import") (part "OP275"))
    )
    (comp (ref "INSERT_AFTER_GAIN")
      (value "90814-0204")
      (footprint "eagle-import:MOLEX_90814-0204")
      (fields (field (name "MOUSER_PART_NUMBER") "538-90814-0204"))
      (libsource (lib "eagle-import") (part "90814-0204"))
    )
    (comp (ref "INSERT_BEFORE_GAIN")
      (value "90814-0204")
      (footprint "eagle-import:MOLEX_90814-0204")
      (fields (field (name "MOUSER_PART_NUMBER") "538-90814-0204"))
      (libsource (lib "eagle-import") (part "90814-0204"))
    )
    (comp (ref "R28")
      (value "20 k")
      (footprint "eagle-import:R0603")
      (libsource (lib "eagle-import") (part "RESISTOR_0603"))
    )
    (comp (ref "R30")
      (value "20 k")
      (footprint "eagle-import:R0603")
      (libsource (lib "eagle-import") (part "RESISTOR_0603"))
    )
    (comp (ref "R31")
      (value "5k1")
      (footprint "eagle-import:R0603")
      (libsource (lib "eagle-import") (part "RESISTOR_0603"))
    )
    (comp (ref "R32")
      (value "5k1")
      (footprint "eagle-import:R0603")
      (libsource (lib "eagle-import") (part "RESISTOR_0603"))
    )
    (comp (ref "R36")
      (value "20 k")
      (footprint "eagle-import:R0603")
      (libsource (lib "eagle-import") (part "RESISTOR_0603"))
    )
    (comp (ref "R37")
      (value "20 k")
      (footprint "eagle-import:R0603")
      (libsource (lib "eagle-import") (part "RESISTOR_0603"))
    )
    (comp (ref "STAGE(LEFT)")
      (value "THAT2181SO8-US")
      (footprint "eagle-import:SO08")
      (fields (field (name "MOUSER_PART_NUMBER") "887-2181CS08-U"))
      (libsource (lib "eagle-import") (part "THAT2181SSO8-U"))
    )
    (comp (ref "STAGE(RIGHT)")
      (value "THAT2181SO8-US")
      (footprint "eagle-import:SO08")
      (fields (field (name "MOUSER_PART_NUMBER") "887-2181CS08-U"))
      (libsource (lib "eagle-import") (part "THAT2181SSO8-U"))
    )
    (comp (ref "TP01")
      (value "TPTHT")
      (footprint "eagle-import:THT_PIN")
      (libsource (lib "eagle-import") (part "TPTHT"))
    )
    (comp (ref "TP02")
      (value "TPTHT")
      (footprint "eagle-import:THT_PIN")
      (libsource (lib "eagle-import") (part "TPTHT"))
    )
    (comp (ref "C44")
      (value "100 nF")
      (footprint "eagle-import:C0603")
      (libsource (lib "eagle-import") (part "CAPACITOR_0603"))
    )
    (comp (ref "C59")
      (value "100 nF")
      (footprint "eagle-import:C0603")
      (libsource (lib "eagle-import") (part "CAPACITOR_0603"))
    )
    (comp (ref "C65")
      (value "2.7 pF")
      (footprint "eagle-import:C0603")
      (libsource (lib "eagle-import") (part "CAPACITOR_0603"))
    )
    (comp (ref "C66")
      (value "2.7 pF")
      (footprint "eagle-import:C0603")
      (libsource (lib "eagle-import") (part "CAPACITOR_0603"))
    )
    (comp (ref "C69")
      (value "4.3 pF")
      (footprint "eagle-import:C0603")
      (libsource (lib "eagle-import") (part "CAPACITOR_0603"))
    )
    (comp (ref "C70")
      (value "4.3 pF")
      (footprint "eagle-import:C0603")
      (libsource (lib "eagle-import") (part "CAPACITOR_0603"))
    )
    (comp (ref "C71")
      (value "2.2 uF")
      (footprint "eagle-import:C1206")
      (libsource (lib "eagle-import") (part "CAPACITOR_1206"))
    )
    (comp (ref "C72")
      (value "2.2 uF")
      (footprint "eagle-import:C1206")
      (libsource (lib "eagle-import") (part "CAPACITOR_1206"))
    )
    (comp (ref "C73")
      (value "100 nF")
      (footprint "eagle-import:C0603")
      (libsource (lib "eagle-import") (part "CAPACITOR_0603"))
    )
    (comp (ref "C74")
      (value "100 nF")
      (footprint "eagle-import:C0603")
      (libsource (lib "eagle-import") (part "CAPACITOR_0603"))
    )
    (comp (ref "C75")
      (value "100 nF")
      (footprint "eagle-import:C0603")
      (libsource (lib "eagle-import") (part "CAPACITOR_0603"))
    )
    (comp (ref "C76")
      (value "100 nF")
      (footprint "eagle-import:C0603")
      (libsource (lib "eagle-import") (part "CAPACITOR_0603"))
    )
    (comp (ref "C77")
      (value "100 nF")
      (footprint "eagle-import:C0603")
      (libsource (lib "eagle-import") (part "CAPACITOR_0603"))
    )
    (comp (ref "C78")
      (value "100 nF")
      (footprint "eagle-import:C0603")
      (libsource (lib "eagle-import") (part "CAPACITOR_0603"))
    )
    (comp (ref "C79")
      (value "100 nF")
      (footprint "eagle-import:C0603")
      (libsource (lib "eagle-import") (part "CAPACITOR_0603"))
    )
    (comp (ref "C80")
      (value "100 nF")
      (footprint "eagle-import:C0603")
      (libsource (lib "eagle-import") (part "CAPACITOR_0603"))
    )
    (comp (ref "C81")
      (value "100 nF")
      (footprint "eagle-import:C0603")
      (libsource (lib "eagle-import") (part "CAPACITOR_0603"))
    )
    (comp (ref "C82")
      (value "100 nF")
      (footprint "eagle-import:C0603")
      (libsource (lib "eagle-import") (part "CAPACITOR_0603"))
    )
    (comp (ref "C83")
      (value "100 nF")
      (footprint "eagle-import:C0603")
      (libsource (lib "eagle-import") (part "CAPACITOR_0603"))
    )
    (comp (ref "C84")
      (value "100 nF")
      (footprint "eagle-import:C0603")
      (libsource (lib "eagle-import") (part "CAPACITOR_0603"))
    )
    (comp (ref "C85")
      (value "100 nF")
      (footprint "eagle-import:C0603")
      (libsource (lib "eagle-import") (part "CAPACITOR_0603"))
    )
    (comp (ref "C119")
      (value "4.7 uF")
      (footprint "eagle-import:C1206")
      (libsource (lib "eagle-import") (part "CAPACITOR_1206"))
    )
    (comp (ref "DEBUG1")
      (value "TPTHT")
      (footprint "eagle-import:THT_PIN")
      (libsource (lib "eagle-import") (part "TPTHT"))
    )
    (comp (ref "DEBUG2")
      (value "TPTHT")
      (footprint "eagle-import:THT_PIN")
      (libsource (lib "eagle-import") (part "TPTHT"))
    )
    (comp (ref "DISPLAY1")
      (value "90814-0204")
      (footprint "eagle-import:MOLEX_90814-0204")
      (fields (field (name "MOUSER_PART_NUMBER") "538-90814-0204"))
      (libsource (lib "eagle-import") (part "90814-0204"))
    )
    (comp (ref "IC10")
      (value "STM32F767ZIT6")
      (footprint "eagle-import:QFP50P2200X2200X160-144N")
      (fields (field (name "MOUSER_PART_NUMBER") "511-STM32F767ZIT6"))
      (libsource (lib "eagle-import") (part "STM32F767ZIT6"))
    )
    (comp (ref "IC12")
      (value "ESDA6V1BC6")
      (footprint "eagle-import:SOT95P280X145-6N")
      (fields (field (name "MOUSER_PART_NUMBER") "511-ESDA6V1BC6"))
      (libsource (lib "eagle-import") (part "ESDA6V1BC6"))
    )
    (comp (ref "LD1")
      (value "LED_YELOW_SMD")
      (footprint "eagle-import:WL-SMCW_0603")
      (fields (field (name "MOUSER_PART_NUMBER") "..."))
      (libsource (lib "eagle-import") (part "LED_SMD_YELOW"))
    )
    (comp (ref "LD2")
      (value "LED_RED_SMD")
      (footprint "eagle-import:WL-SMCW_0603")
      (fields (field (name "MOUSER_PART_NUMBER") "..."))
      (libsource (lib "eagle-import") (part "LED_SMD_RED"))
    )
    (comp (ref "LD3")
      (value "LED_GREEN_SMD")
      (footprint "eagle-import:WL-SMCW_0603")
      (fields (field (name "MOUSER_PART_NUMBER") "..."))
      (libsource (lib "eagle-import") (part "LED_SMD_GREEN"))
    )
    (comp (ref "PROG.")
      (value "90814-0204")
      (footprint "eagle-import:MOLEX_90814-0204")
      (fields (field (name "MOUSER_PART_NUMBER") "538-90814-0204"))
      (libsource (lib "eagle-import") (part "90814-0204"))
    )
    (comp (ref "R5")
      (value "680 R")
      (footprint "eagle-import:R0603")
      (libsource (lib "eagle-import") (part "RESISTOR_0603"))
    )
    (comp (ref "R6")
      (value "680 R")
      (footprint "eagle-import:R0603")
      (libsource (lib "eagle-import") (part "RESISTOR_0603"))
    )
    (comp (ref "R13")
      (value "680 R")
      (footprint "eagle-import:R0603")
      (libsource (lib "eagle-import") (part "RESISTOR_0603"))
    )
    (comp (ref "R19")
      (value "10 k")
      (footprint "eagle-import:R0603")
      (libsource (lib "eagle-import") (part "RESISTOR_0603"))
    )
    (comp (ref "R78")
      (value "10 k")
      (footprint "eagle-import:R0603")
      (libsource (lib "eagle-import") (part "RESISTOR_0603"))
    )
    (comp (ref "S1")
      (value "PTS647SN50SMTR2LFS")
      (footprint "eagle-import:PTS647SN50SMTR2LFS")
      (fields (field (name "MOUSER_PART_NUMBER") "611-PTS647SN50SMTR2L"))
      (libsource (lib "eagle-import") (part "PTS647SN50SMTR2LFS"))
    )
    (comp (ref "TP05")
      (value "TPTHT")
      (footprint "eagle-import:THT_PIN")
      (libsource (lib "eagle-import") (part "TPTHT"))
    )
    (comp (ref "TP06")
      (value "TPTHT")
      (footprint "eagle-import:THT_PIN")
      (libsource (lib "eagle-import") (part "TPTHT"))
    )
    (comp (ref "TP07")
      (value "TPTHT")
      (footprint "eagle-import:THT_PIN")
      (libsource (lib "eagle-import") (part "TPTHT"))
    )
    (comp (ref "TP08")
      (value "TPTHT")
      (footprint "eagle-import:THT_PIN")
      (libsource (lib "eagle-import") (part "TPTHT"))
    )
    (comp (ref "TP09")
      (value "TPTHT")
      (footprint "eagle-import:THT_PIN")
      (libsource (lib "eagle-import") (part "TPTHT"))
    )
    (comp (ref "TP10")
      (value "TPTHT")
      (footprint "eagle-import:THT_PIN")
      (libsource (lib "eagle-import") (part "TPTHT"))
    )
    (comp (ref "X1")
      (value "USB_B_CONNECTOR")
      (footprint "eagle-import:SMARTPRJ_PN61729")
      (fields (field (name "MOUSER_PART_NUMBER") "649-61729-0010BLF"))
      (libsource (lib "eagle-import") (part "USB_B_CONNECTOR"))
    )
    (comp (ref "Y1")
      (value "NX3215SA-32.768K-STD-MUA-8")
      (footprint "eagle-import:NX3215SA")
      (fields (field (name "MOUSER_PART_NUMBER") "344-NX3215SA32768K8"))
      (libsource (lib "eagle-import") (part "NX3215SA-32.768K-STD-MUA-8"))
    )
    (comp (ref "Y2")
      (value "NX3225GD-8MHZ-STD-CRA-3")
      (footprint "eagle-import:RESC3226X100N")
      (fields (field (name "MOUSER_PART_NUMBER") "344-NX3225GD8MCRA3"))
      (libsource (lib "eagle-import") (part "NX3225GD-8MHZ-STD-CRA-3"))
    )
    (comp (ref "C14")
      (value "100 nF")
      (footprint "eagle-import:C0603")
      (libsource (lib "eagle-import") (part "CAPACITOR_0603"))
    )
    (comp (ref "C19")
      (value "100 nF")
      (footprint "eagle-import:C0603")
      (libsource (lib "eagle-import") (part "CAPACITOR_0603"))
    )
    (comp (ref "C22")
      (value "100 nF")
      (footprint "eagle-import:C0603")
      (libsource (lib "eagle-import") (part "CAPACITOR_0603"))
    )
    (comp (ref "C24")
      (value "100 nF")
      (footprint "eagle-import:C0603")
      (libsource (lib "eagle-import") (part "CAPACITOR_0603"))
    )
    (comp (ref "C31")
      (value "10 uF")
      (footprint "eagle-import:C1206")
      (libsource (lib "eagle-import") (part "CAPACITOR_1206"))
    )
    (comp (ref "C32")
      (value "10 uF")
      (footprint "eagle-import:C1206")
      (libsource (lib "eagle-import") (part "CAPACITOR_1206"))
    )
    (comp (ref "C33")
      (value "10 uF")
      (footprint "eagle-import:C1206")
      (libsource (lib "eagle-import") (part "CAPACITOR_1206"))
    )
    (comp (ref "C34")
      (value "10 uF")
      (footprint "eagle-import:C1206")
      (libsource (lib "eagle-import") (part "CAPACITOR_1206"))
    )
    (comp (ref "C36")
      (value "100 nF")
      (footprint "eagle-import:C0603")
      (libsource (lib "eagle-import") (part "CAPACITOR_0603"))
    )
    (comp (ref "C39")
      (value "10 uF")
      (footprint "eagle-import:C1206")
      (libsource (lib "eagle-import") (part "CAPACITOR_1206"))
    )
    (comp (ref "C48")
      (value "100 nF")
      (footprint "eagle-import:C0603")
      (libsource (lib "eagle-import") (part "CAPACITOR_0603"))
    )
    (comp (ref "C49")
      (value "100 nF")
      (footprint "eagle-import:C0603")
      (libsource (lib "eagle-import") (part "CAPACITOR_0603"))
    )
    (comp (ref "C64")
      (value "10 uF")
      (footprint "eagle-import:C1206")
      (libsource (lib "eagle-import") (part "CAPACITOR_1206"))
    )
    (comp (ref "C95")
      (value "100 nF")
      (footprint "eagle-import:C0603")
      (libsource (lib "eagle-import") (part "CAPACITOR_0603"))
    )
    (comp (ref "C96")
      (value "100 nF")
      (footprint "eagle-import:C0603")
      (libsource (lib "eagle-import") (part "CAPACITOR_0603"))
    )
    (comp (ref "C97")
      (value "100 nF")
      (footprint "eagle-import:C0603")
      (libsource (lib "eagle-import") (part "CAPACITOR_0603"))
    )
    (comp (ref "C98")
      (value "100 nF")
      (footprint "eagle-import:C0603")
      (libsource (lib "eagle-import") (part "CAPACITOR_0603"))
    )
    (comp (ref "C99")
      (value "10 uF")
      (footprint "eagle-import:C1206")
      (libsource (lib "eagle-import") (part "CAPACITOR_1206"))
    )
    (comp (ref "IC2")
      (value "DAC084S085CIMM_NOPB")
      (footprint "eagle-import:SOP50P490X110-10N")
      (fields (field (name "MOUSER_PART_NUMBER") "926-DAC084S085CIMMNO"))
      (libsource (lib "eagle-import") (part "DAC084S085CIMM_NOPB"))
    )
    (comp (ref "IC3")
      (value "DAC084S085CIMM_NOPB")
      (footprint "eagle-import:SOP50P490X110-10N")
      (fields (field (name "MOUSER_PART_NUMBER") "926-DAC084S085CIMMNO"))
      (libsource (lib "eagle-import") (part "DAC084S085CIMM_NOPB"))
    )
    (comp (ref "IC7")
      (value "TL072")
      (footprint "eagle-import:SOIC8")
      (libsource (lib "eagle-import") (part "TL072"))
    )
    (comp (ref "IC14")
      (value "TL072")
      (footprint "eagle-import:SOIC8")
      (libsource (lib "eagle-import") (part "TL072"))
    )
    (comp (ref "IC15")
      (value "TL072")
      (footprint "eagle-import:SOIC8")
      (libsource (lib "eagle-import") (part "TL072"))
    )
    (comp (ref "R38")
      (value "27 k")
      (footprint "eagle-import:R0603")
      (libsource (lib "eagle-import") (part "RESISTOR_0603"))
    )
    (comp (ref "R40")
      (value "160 k")
      (footprint "eagle-import:R0603")
      (libsource (lib "eagle-import") (part "RESISTOR_0603"))
    )
    (comp (ref "R41")
      (value "27 k")
      (footprint "eagle-import:R0603")
      (libsource (lib "eagle-import") (part "RESISTOR_0603"))
    )
    (comp (ref "R43")
      (value "160 k")
      (footprint "eagle-import:R0603")
      (libsource (lib "eagle-import") (part "RESISTOR_0603"))
    )
    (comp (ref "R44")
      (value "27 k")
      (footprint "eagle-import:R0603")
      (libsource (lib "eagle-import") (part "RESISTOR_0603"))
    )
    (comp (ref "R46")
      (value "10 k")
      (footprint "eagle-import:R0603")
      (libsource (lib "eagle-import") (part "RESISTOR_0603"))
    )
    (comp (ref "R47")
      (value "1k8")
      (footprint "eagle-import:R0603")
      (libsource (lib "eagle-import") (part "RESISTOR_0603"))
    )
    (comp (ref "R58")
      (value "10 k")
      (footprint "eagle-import:R0603")
      (libsource (lib "eagle-import") (part "RESISTOR_0603"))
    )
    (comp (ref "R59")
      (value "56 k")
      (footprint "eagle-import:R0603")
      (libsource (lib "eagle-import") (part "RESISTOR_0603"))
    )
    (comp (ref "R60")
      (value "10 k")
      (footprint "eagle-import:R0603")
      (libsource (lib "eagle-import") (part "RESISTOR_0603"))
    )
    (comp (ref "R61")
      (value "10 k")
      (footprint "eagle-import:R0603")
      (libsource (lib "eagle-import") (part "RESISTOR_0603"))
    )
    (comp (ref "R62")
      (value "10 k")
      (footprint "eagle-import:R0603")
      (libsource (lib "eagle-import") (part "RESISTOR_0603"))
    )
    (comp (ref "R63")
      (value "160 k")
      (footprint "eagle-import:R0603")
      (libsource (lib "eagle-import") (part "RESISTOR_0603"))
    )
    (comp (ref "R64")
      (value "27 k")
      (footprint "eagle-import:R0603")
      (libsource (lib "eagle-import") (part "RESISTOR_0603"))
    )
    (comp (ref "R66")
      (value "160 k")
      (footprint "eagle-import:R0603")
      (libsource (lib "eagle-import") (part "RESISTOR_0603"))
    )
    (comp (ref "R67")
      (value "10 k")
      (footprint "eagle-import:R0603")
      (libsource (lib "eagle-import") (part "RESISTOR_0603"))
    )
    (comp (ref "R68")
      (value "20 k")
      (footprint "eagle-import:R0603")
      (libsource (lib "eagle-import") (part "RESISTOR_0603"))
    )
    (comp (ref "R70")
      (value "10 k")
      (footprint "eagle-import:R0603")
      (libsource (lib "eagle-import") (part "RESISTOR_0603"))
    )
    (comp (ref "R71")
      (value "10 k")
      (footprint "eagle-import:R0603")
      (libsource (lib "eagle-import") (part "RESISTOR_0603"))
    )
    (comp (ref "R72")
      (value "10 k")
      (footprint "eagle-import:R0603")
      (libsource (lib "eagle-import") (part "RESISTOR_0603"))
    )
    (comp (ref "R73")
      (value "56 k")
      (footprint "eagle-import:R0603")
      (libsource (lib "eagle-import") (part "RESISTOR_0603"))
    )
    (comp (ref "R74")
      (value "10 k")
      (footprint "eagle-import:R0603")
      (libsource (lib "eagle-import") (part "RESISTOR_0603"))
    )
    (comp (ref "R75")
      (value "10 k")
      (footprint "eagle-import:R0603")
      (libsource (lib "eagle-import") (part "RESISTOR_0603"))
    )
    (comp (ref "R76")
      (value "1k8")
      (footprint "eagle-import:R0603")
      (libsource (lib "eagle-import") (part "RESISTOR_0603"))
    )
    (comp (ref "R92")
      (value "500 R")
      (footprint "eagle-import:R0603")
      (libsource (lib "eagle-import") (part "RESISTOR_0603"))
    )
    (comp (ref "R93")
      (value "500 R")
      (footprint "eagle-import:R0603")
      (libsource (lib "eagle-import") (part "RESISTOR_0603"))
    )
    (comp (ref "R94")
      (value "500 R")
      (footprint "eagle-import:R0603")
      (libsource (lib "eagle-import") (part "RESISTOR_0603"))
    )
    (comp (ref "R95")
      (value "500 R")
      (footprint "eagle-import:R0603")
      (libsource (lib "eagle-import") (part "RESISTOR_0603"))
    )
    (comp (ref "R102")
      (value "500 R")
      (footprint "eagle-import:R0603")
      (libsource (lib "eagle-import") (part "RESISTOR_0603"))
    )
    (comp (ref "R103")
      (value "500 R")
      (footprint "eagle-import:R0603")
      (libsource (lib "eagle-import") (part "RESISTOR_0603"))
    )
    (comp (ref "TP03")
      (value "TPTHT")
      (footprint "eagle-import:THT_PIN")
      (libsource (lib "eagle-import") (part "TPTHT"))
    )
    (comp (ref "TP04")
      (value "TPTHT")
      (footprint "eagle-import:THT_PIN")
      (libsource (lib "eagle-import") (part "TPTHT"))
    )
    (comp (ref "Z1")
      (value "ZENER_DIODE_BZT")
      (footprint "eagle-import:SODFL1608X65N")
      (fields (field (name "MOUSER_PART_NUMBER") "621-BZT52C2V0T-7"))
      (libsource (lib "eagle-import") (part "ZENER_DIODE_BZT"))
    )
    (comp (ref "C1")
      (value "100 nF")
      (footprint "eagle-import:C0603")
      (libsource (lib "eagle-import") (part "CAPACITOR_0603"))
    )
    (comp (ref "C8")
      (value "100 nF")
      (footprint "eagle-import:C0603")
      (libsource (lib "eagle-import") (part "CAPACITOR_0603"))
    )
    (comp (ref "C11")
      (value "100 nF")
      (footprint "eagle-import:C0603")
      (libsource (lib "eagle-import") (part "CAPACITOR_0603"))
    )
    (comp (ref "C16")
      (value "470 pF")
      (footprint "eagle-import:C0603")
      (libsource (lib "eagle-import") (part "CAPACITOR_0603"))
    )
    (comp (ref "C17")
      (value "470 pF")
      (footprint "eagle-import:C0603")
      (libsource (lib "eagle-import") (part "CAPACITOR_0603"))
    )
    (comp (ref "C18")
      (value "47 pF")
      (footprint "eagle-import:C0603")
      (libsource (lib "eagle-import") (part "CAPACITOR_0603"))
    )
    (comp (ref "C104")
      (value "100 nF")
      (footprint "eagle-import:C0603")
      (libsource (lib "eagle-import") (part "CAPACITOR_0603"))
    )
    (comp (ref "C106")
      (value "100 nF")
      (footprint "eagle-import:C0603")
      (libsource (lib "eagle-import") (part "CAPACITOR_0603"))
    )
    (comp (ref "C107")
      (value "100 nF")
      (footprint "eagle-import:C0603")
      (libsource (lib "eagle-import") (part "CAPACITOR_0603"))
    )
    (comp (ref "C112")
      (value "10 uF")
      (footprint "eagle-import:C1206")
      (libsource (lib "eagle-import") (part "CAPACITOR_1206"))
    )
    (comp (ref "C113")
      (value "10 uF")
      (footprint "eagle-import:C1206")
      (libsource (lib "eagle-import") (part "CAPACITOR_1206"))
    )
    (comp (ref "D1")
      (value "FM4004-W")
      (footprint "eagle-import:DIONM5025X231N")
      (fields (field (name "MOUSER_PART_NUMBER") "583-FM4004"))
      (libsource (lib "eagle-import") (part "FM4004-W"))
    )
    (comp (ref "D2")
      (value "FM4004-W")
      (footprint "eagle-import:DIONM5025X231N")
      (fields (field (name "MOUSER_PART_NUMBER") "583-FM4004"))
      (libsource (lib "eagle-import") (part "FM4004-W"))
    )
    (comp (ref "D3")
      (value "FM4004-W")
      (footprint "eagle-import:DIONM5025X231N")
      (fields (field (name "MOUSER_PART_NUMBER") "583-FM4004"))
      (libsource (lib "eagle-import") (part "FM4004-W"))
    )
    (comp (ref "D4")
      (value "FM4004-W")
      (footprint "eagle-import:DIONM5025X231N")
      (fields (field (name "MOUSER_PART_NUMBER") "583-FM4004"))
      (libsource (lib "eagle-import") (part "FM4004-W"))
    )
    (comp (ref "IN2(L/M)")
      (value "NEUTRIK_NC3FAH")
      (footprint "eagle-import:NEUTRIK_NC3FAH")
      (libsource (lib "eagle-import") (part "NEUTRIK_NC3FAH"))
    )
    (comp (ref "IN_LEFT")
      (value "THAT1240")
      (footprint "eagle-import:SO08")
      (fields (field (name "MOUSER_PART_NUMBER") "887-1240S08-U"))
      (libsource (lib "eagle-import") (part "THAT1240SO8-USO8-U"))
    )
    (comp (ref "K3")
      (value "Relay")
      (footprint "eagle-import:351")
      (libsource (lib "eagle-import") (part "RELAY_EE2-5NU"))
    )
    (comp (ref "K4")
      (value "Relay")
      (footprint "eagle-import:351")
      (libsource (lib "eagle-import") (part "RELAY_EE2-5NU"))
    )
    (comp (ref "OUT2(L/M)")
      (value "NEUTRIK_NC3MAH")
      (footprint "eagle-import:NEUTRIK_NC3MAH")
      (libsource (lib "eagle-import") (part "NEUTRIK_NC3MAH"))
    )
    (comp (ref "OUT_LEFT")
      (value "THAT1646")
      (footprint "eagle-import:SO08")
      (fields (field (name "MOUSER_PART_NUMBER") "887-1646S08-U"))
      (libsource (lib "eagle-import") (part "THAT1646SO8-USO8-U"))
    )
    (comp (ref "K1")
      (value "Relay")
      (footprint "eagle-import:351")
      (libsource (lib "eagle-import") (part "RELAY_EE2-5NU"))
    )
    (comp (ref "K2")
      (value "Relay")
      (footprint "eagle-import:351")
      (libsource (lib "eagle-import") (part "RELAY_EE2-5NU"))
    )
    (comp (ref "K5")
      (value "Relay")
      (footprint "eagle-import:351")
      (fields (field (name "SPICEPREFIX") "B"))
      (libsource (lib "eagle-import") (part "RELAY_EE2-5NU"))
    )
    (comp (ref "K6")
      (value "Relay")
      (footprint "eagle-import:351")
      (fields (field (name "SPICEPREFIX") "B"))
      (libsource (lib "eagle-import") (part "RELAY_EE2-5NU"))
    )
    (comp (ref "K7")
      (value "Relay")
      (footprint "eagle-import:351")
      (libsource (lib "eagle-import") (part "RELAY_EE2-5NU"))
    )
    (comp (ref "K8")
      (value "Relay")
      (footprint "eagle-import:351")
      (libsource (lib "eagle-import") (part "RELAY_EE2-5NU"))
    )
    (comp (ref "LED1")
      (value "LED_BLUE_SMD")
      (footprint "eagle-import:WL-SMCW_0603")
      (fields (field (name "MOUSER_PART_NUMBER") "..."))
      (libsource (lib "eagle-import") (part "LED_SMD_BLUE"))
    )
    (comp (ref "LED2")
      (value "LED_BLUE_SMD")
      (footprint "eagle-import:WL-SMCW_0603")
      (fields (field (name "MOUSER_PART_NUMBER") "..."))
      (libsource (lib "eagle-import") (part "LED_SMD_BLUE"))
    )
    (comp (ref "LED3")
      (value "LED_BLUE_SMD")
      (footprint "eagle-import:WL-SMCW_0603")
      (fields (field (name "MOUSER_PART_NUMBER") "..."))
      (libsource (lib "eagle-import") (part "LED_SMD_BLUE"))
    )
    (comp (ref "LED4")
      (value "LED_BLUE_SMD")
      (footprint "eagle-import:WL-SMCW_0603")
      (fields (field (name "MOUSER_PART_NUMBER") "..."))
      (libsource (lib "eagle-import") (part "LED_SMD_BLUE"))
    )
    (comp (ref "LED5")
      (value "LED_BLUE_SMD")
      (footprint "eagle-import:WL-SMCW_0603")
      (fields (field (name "MOUSER_PART_NUMBER") "..."))
      (libsource (lib "eagle-import") (part "LED_SMD_BLUE"))
    )
    (comp (ref "LED6")
      (value "LED_BLUE_SMD")
      (footprint "eagle-import:WL-SMCW_0603")
      (fields (field (name "MOUSER_PART_NUMBER") "..."))
      (libsource (lib "eagle-import") (part "LED_SMD_BLUE"))
    )
    (comp (ref "LED7")
      (value "LED_BLUE_SMD")
      (footprint "eagle-import:WL-SMCW_0603")
      (fields (field (name "MOUSER_PART_NUMBER") "..."))
      (libsource (lib "eagle-import") (part "LED_SMD_BLUE"))
    )
    (comp (ref "LED8")
      (value "LED_BLUE_SMD")
      (footprint "eagle-import:WL-SMCW_0603")
      (fields (field (name "MOUSER_PART_NUMBER") "..."))
      (libsource (lib "eagle-import") (part "LED_SMD_BLUE"))
    )
    (comp (ref "R7")
      (value "680 R")
      (footprint "eagle-import:R0603")
      (libsource (lib "eagle-import") (part "RESISTOR_0603"))
    )
    (comp (ref "R8")
      (value "680 R")
      (footprint "eagle-import:R0603")
      (libsource (lib "eagle-import") (part "RESISTOR_0603"))
    )
    (comp (ref "R9")
      (value "680 R")
      (footprint "eagle-import:R0603")
      (libsource (lib "eagle-import") (part "RESISTOR_0603"))
    )
    (comp (ref "R10")
      (value "680 R")
      (footprint "eagle-import:R0603")
      (libsource (lib "eagle-import") (part "RESISTOR_0603"))
    )
    (comp (ref "R11")
      (value "680 R")
      (footprint "eagle-import:R0603")
      (libsource (lib "eagle-import") (part "RESISTOR_0603"))
    )
    (comp (ref "R12")
      (value "680 R")
      (footprint "eagle-import:R0603")
      (libsource (lib "eagle-import") (part "RESISTOR_0603"))
    )
    (comp (ref "R33")
      (value "680 R")
      (footprint "eagle-import:R0603")
      (libsource (lib "eagle-import") (part "RESISTOR_0603"))
    )
    (comp (ref "R34")
      (value "680 R")
      (footprint "eagle-import:R0603")
      (libsource (lib "eagle-import") (part "RESISTOR_0603"))
    )
    (comp (ref "U12")
      (value "ULN2003")
      (footprint "eagle-import:SOIC16")
      (libsource (lib "eagle-import") (part "ULN2003"))
    )
    (comp (ref "C50")
      (value "100 nF")
      (footprint "eagle-import:C0603")
      (libsource (lib "eagle-import") (part "CAPACITOR_0603"))
    )
    (comp (ref "C53")
      (value "100 nF")
      (footprint "eagle-import:C0603")
      (libsource (lib "eagle-import") (part "CAPACITOR_0603"))
    )
    (comp (ref "C54")
      (value "100 nF")
      (footprint "eagle-import:C0603")
      (libsource (lib "eagle-import") (part "CAPACITOR_0603"))
    )
    (comp (ref "C55")
      (value "22 pF")
      (footprint "eagle-import:C0603")
      (libsource (lib "eagle-import") (part "CAPACITOR_0603"))
    )
    (comp (ref "C56")
      (value "22 pF")
      (footprint "eagle-import:C0603")
      (libsource (lib "eagle-import") (part "CAPACITOR_0603"))
    )
    (comp (ref "C57")
      (value "100 nF")
      (footprint "eagle-import:C0603")
      (libsource (lib "eagle-import") (part "CAPACITOR_0603"))
    )
    (comp (ref "C58")
      (value "100 nF")
      (footprint "eagle-import:C0603")
      (libsource (lib "eagle-import") (part "CAPACITOR_0603"))
    )
    (comp (ref "C60")
      (value "100 nF")
      (footprint "eagle-import:C0603")
      (libsource (lib "eagle-import") (part "CAPACITOR_0603"))
    )
    (comp (ref "C61")
      (value "100 nF")
      (footprint "eagle-import:C0603")
      (libsource (lib "eagle-import") (part "CAPACITOR_0603"))
    )
    (comp (ref "C62")
      (value "100 nF")
      (footprint "eagle-import:C0603")
      (libsource (lib "eagle-import") (part "CAPACITOR_0603"))
    )
    (comp (ref "C67")
      (value "10 uF")
      (footprint "eagle-import:C1206")
      (libsource (lib "eagle-import") (part "CAPACITOR_1206"))
    )
    (comp (ref "C102")
      (value "10 uF")
      (footprint "eagle-import:C1206")
      (libsource (lib "eagle-import") (part "CAPACITOR_1206"))
    )
    (comp (ref "IC8")
      (value "OP275")
      (footprint "eagle-import:SOIC8")
      (libsource (lib "eagle-import") (part "OP275"))
    )
    (comp (ref "IC9")
      (value "TL072")
      (footprint "eagle-import:SOIC8")
      (libsource (lib "eagle-import") (part "TL072"))
    )
    (comp (ref "R48")
      (value "20 k")
      (footprint "eagle-import:R0603")
      (libsource (lib "eagle-import") (part "RESISTOR_0603"))
    )
    (comp (ref "R49")
      (value "20 k")
      (footprint "eagle-import:R0603")
      (libsource (lib "eagle-import") (part "RESISTOR_0603"))
    )
    (comp (ref "R50")
      (value "5k1")
      (footprint "eagle-import:R0603")
      (libsource (lib "eagle-import") (part "RESISTOR_0603"))
    )
    (comp (ref "R51")
      (value "5k1")
      (footprint "eagle-import:R0603")
      (libsource (lib "eagle-import") (part "RESISTOR_0603"))
    )
    (comp (ref "R52")
      (value "20 k")
      (footprint "eagle-import:R0603")
      (libsource (lib "eagle-import") (part "RESISTOR_0603"))
    )
    (comp (ref "R53")
      (value "20 k")
      (footprint "eagle-import:R0603")
      (libsource (lib "eagle-import") (part "RESISTOR_0603"))
    )
    (comp (ref "R54")
      (value "10 k")
      (footprint "eagle-import:R0603")
      (libsource (lib "eagle-import") (part "RESISTOR_0603"))
    )
    (comp (ref "R55")
      (value "10 k")
      (footprint "eagle-import:R0603")
      (libsource (lib "eagle-import") (part "RESISTOR_0603"))
    )
    (comp (ref "R56")
      (value "10 k")
      (footprint "eagle-import:R0603")
      (libsource (lib "eagle-import") (part "RESISTOR_0603"))
    )
    (comp (ref "R57")
      (value "10 k")
      (footprint "eagle-import:R0603")
      (libsource (lib "eagle-import") (part "RESISTOR_0603"))
    )
    (comp (ref "TP36")
      (value "TPTHT")
      (footprint "eagle-import:THT_PIN")
      (libsource (lib "eagle-import") (part "TPTHT"))
    )
    (comp (ref "TP37")
      (value "TPTHT")
      (footprint "eagle-import:THT_PIN")
      (libsource (lib "eagle-import") (part "TPTHT"))
    )
    (comp (ref "VCA1(LEFT)")
      (value "THAT2181SO8-US")
      (footprint "eagle-import:SO08")
      (fields (field (name "MOUSER_PART_NUMBER") "887-2181CS08-U"))
      (libsource (lib "eagle-import") (part "THAT2181SSO8-U"))
    )
    (comp (ref "VCA2(RIGHT)")
      (value "THAT2181SO8-US")
      (footprint "eagle-import:SO08")
      (fields (field (name "MOUSER_PART_NUMBER") "887-2181CS08-U"))
      (libsource (lib "eagle-import") (part "THAT2181SSO8-U"))
    )
    (comp (ref "+3V3_OK")
      (value "LED_GREEN_SMD")
      (footprint "eagle-import:WL-SMCW_0603")
      (fields (field (name "MOUSER_PART_NUMBER") "..."))
      (libsource (lib "eagle-import") (part "LED_SMD_GREEN"))
    )
    (comp (ref "+5V_OK")
      (value "LED_GREEN_SMD")
      (footprint "eagle-import:WL-SMCW_0603")
      (fields (field (name "MOUSER_PART_NUMBER") "..."))
      (libsource (lib "eagle-import") (part "LED_SMD_GREEN"))
    )
    (comp (ref "+15V_OK")
      (value "LED_GREEN_SMD")
      (footprint "eagle-import:WL-SMCW_0603")
      (fields (field (name "MOUSER_PART_NUMBER") "..."))
      (libsource (lib "eagle-import") (part "LED_SMD_GREEN"))
    )
    (comp (ref "-15V_OK")
      (value "LED_GREEN_SMD")
      (footprint "eagle-import:WL-SMCW_0603")
      (fields (field (name "MOUSER_PART_NUMBER") "..."))
      (libsource (lib "eagle-import") (part "LED_SMD_GREEN"))
    )
    (comp (ref "ANALOG_VOLT_IN")
      (value "90814-0204")
      (footprint "eagle-import:MOLEX_90814-0204")
      (fields (field (name "MOUSER_PART_NUMBER") "538-90814-0204"))
      (libsource (lib "eagle-import") (part "90814-0204"))
    )
    (comp (ref "ANALOG_VOLT_OUT")
      (value "90814-0204")
      (footprint "eagle-import:MOLEX_90814-0204")
      (fields (field (name "MOUSER_PART_NUMBER") "538-90814-0204"))
      (libsource (lib "eagle-import") (part "90814-0204"))
    )
    (comp (ref "C103")
      (value "330 nF")
      (footprint "eagle-import:C0603")
      (libsource (lib "eagle-import") (part "CAPACITOR_0603"))
    )
    (comp (ref "C105")
      (value "100 nF")
      (footprint "eagle-import:C0603")
      (libsource (lib "eagle-import") (part "CAPACITOR_0603"))
    )
    (comp (ref "DIGITAL_VOLT")
      (value "90814-0204")
      (footprint "eagle-import:MOLEX_90814-0204")
      (fields (field (name "MOUSER_PART_NUMBER") "538-90814-0204"))
      (libsource (lib "eagle-import") (part "90814-0204"))
    )
    (comp (ref "R15")
      (value "0 R")
      (footprint "eagle-import:R0603")
      (libsource (lib "eagle-import") (part "RESISTOR_0603"))
    )
    (comp (ref "R16")
      (value "0 R")
      (footprint "eagle-import:R0603")
      (libsource (lib "eagle-import") (part "RESISTOR_0603"))
    )
    (comp (ref "R17")
      (value "0 R")
      (footprint "eagle-import:R0603")
      (libsource (lib "eagle-import") (part "RESISTOR_0603"))
    )
    (comp (ref "R69")
      (value "0 R")
      (footprint "eagle-import:R0603")
      (libsource (lib "eagle-import") (part "RESISTOR_0603"))
    )
    (comp (ref "R97")
      (value "680 R")
      (footprint "eagle-import:R0603")
      (libsource (lib "eagle-import") (part "RESISTOR_0603"))
    )
    (comp (ref "R98")
      (value "680 R")
      (footprint "eagle-import:R0603")
      (libsource (lib "eagle-import") (part "RESISTOR_0603"))
    )
    (comp (ref "R99")
      (value "65 R")
      (footprint "eagle-import:R0603")
      (libsource (lib "eagle-import") (part "RESISTOR_0603"))
    )
    (comp (ref "R100")
      (value "150 R")
      (footprint "eagle-import:R0603")
      (libsource (lib "eagle-import") (part "RESISTOR_0603"))
    )
    (comp (ref "R104")
      (value "0 R")
      (footprint "eagle-import:R0603")
      (libsource (lib "eagle-import") (part "RESISTOR_0603"))
    )
    (comp (ref "U1")
      (value "78_SMD")
      (footprint "eagle-import:TO252")
      (libsource (lib "eagle-import") (part "78_SMD"))
    )
    (comp (ref "C41")
      (value "10 uF")
      (footprint "eagle-import:C1206")
      (libsource (lib "eagle-import") (part "CAPACITOR_1206"))
    )
    (comp (ref "C42")
      (value "100 nF")
      (footprint "eagle-import:C0603")
      (libsource (lib "eagle-import") (part "CAPACITOR_0603"))
    )
    (comp (ref "C51")
      (value "100 nF")
      (footprint "eagle-import:C0603")
      (libsource (lib "eagle-import") (part "CAPACITOR_0603"))
    )
    (comp (ref "C52")
      (value "100 nF")
      (footprint "eagle-import:C0603")
      (libsource (lib "eagle-import") (part "CAPACITOR_0603"))
    )
    (comp (ref "C114")
      (value "100 nF")
      (footprint "eagle-import:C0603")
      (libsource (lib "eagle-import") (part "CAPACITOR_0603"))
    )
    (comp (ref "C115")
      (value "10 uF")
      (footprint "eagle-import:C1206")
      (libsource (lib "eagle-import") (part "CAPACITOR_1206"))
    )
    (comp (ref "C116")
      (value "10 uF")
      (footprint "eagle-import:C1206")
      (libsource (lib "eagle-import") (part "CAPACITOR_1206"))
    )
    (comp (ref "C117")
      (value "1 uF")
      (footprint "eagle-import:C0603")
      (libsource (lib "eagle-import") (part "CAPACITOR_0603"))
    )
    (comp (ref "C118")
      (value "1 uF")
      (footprint "eagle-import:C0603")
      (libsource (lib "eagle-import") (part "CAPACITOR_0603"))
    )
    (comp (ref "IC17")
      (value "AD7606BSTZ-6")
      (footprint "eagle-import:QFP50P1200X1200X160-64N")
      (fields (field (name "MOUSER_PART_NUMBER") "584-AD7606BSTZ-6"))
      (libsource (lib "eagle-import") (part "AD7606BSTZ-6"))
    )
    (comp (ref "R14")
      (value "10 k")
      (footprint "eagle-import:R0603")
      (libsource (lib "eagle-import") (part "RESISTOR_0603"))
    )
    (comp (ref "R35")
      (value "10 k")
      (footprint "eagle-import:R0603")
      (libsource (lib "eagle-import") (part "RESISTOR_0603"))
    )
    (comp (ref "R96")
      (value "10 k")
      (footprint "eagle-import:R0603")
      (libsource (lib "eagle-import") (part "RESISTOR_0603"))
    )
    (comp (ref "C4")
      (value "100 nF")
      (footprint "eagle-import:C0603")
      (libsource (lib "eagle-import") (part "CAPACITOR_0603"))
    )
    (comp (ref "C5")
      (value "100 nF")
      (footprint "eagle-import:C0603")
      (libsource (lib "eagle-import") (part "CAPACITOR_0603"))
    )
    (comp (ref "C20")
      (value "100 nF")
      (footprint "eagle-import:C0603")
      (libsource (lib "eagle-import") (part "CAPACITOR_0603"))
    )
    (comp (ref "C21")
      (value "100 nF")
      (footprint "eagle-import:C0603")
      (libsource (lib "eagle-import") (part "CAPACITOR_0603"))
    )
    (comp (ref "C23")
      (value "100 nF")
      (footprint "eagle-import:C0603")
      (libsource (lib "eagle-import") (part "CAPACITOR_0603"))
    )
    (comp (ref "C25")
      (value "100 nF")
      (footprint "eagle-import:C0603")
      (libsource (lib "eagle-import") (part "CAPACITOR_0603"))
    )
    (comp (ref "C63")
      (value "100 nF")
      (footprint "eagle-import:C0603")
      (libsource (lib "eagle-import") (part "CAPACITOR_0603"))
    )
    (comp (ref "C68")
      (value "100 nF")
      (footprint "eagle-import:C0603")
      (libsource (lib "eagle-import") (part "CAPACITOR_0603"))
    )
    (comp (ref "IC4")
      (value "OP275")
      (footprint "eagle-import:SOIC8")
      (libsource (lib "eagle-import") (part "OP275"))
    )
    (comp (ref "IC16")
      (value "OP275")
      (footprint "eagle-import:SOIC8")
      (libsource (lib "eagle-import") (part "OP275"))
    )
    (comp (ref "U4")
      (value "THAT1240")
      (footprint "eagle-import:SO08")
      (fields (field (name "MOUSER_PART_NUMBER") "887-1240S08-U"))
      (libsource (lib "eagle-import") (part "THAT1240SO8-USO8-U"))
    )
    (comp (ref "U6")
      (value "THAT1240")
      (footprint "eagle-import:SO08")
      (fields (field (name "MOUSER_PART_NUMBER") "887-1240S08-U"))
      (libsource (lib "eagle-import") (part "THAT1240SO8-USO8-U"))
    )
    (comp (ref "C40")
      (value "30 pF")
      (footprint "eagle-import:C0603")
      (libsource (lib "eagle-import") (part "CAPACITOR_0603"))
    )
    (comp (ref "C86")
      (value "100 nF")
      (footprint "eagle-import:C0603")
      (libsource (lib "eagle-import") (part "CAPACITOR_0603"))
    )
    (comp (ref "C87")
      (value "100 nF")
      (footprint "eagle-import:C0603")
      (libsource (lib "eagle-import") (part "CAPACITOR_0603"))
    )
    (comp (ref "C88")
      (value "1 uF")
      (footprint "eagle-import:C0603")
      (libsource (lib "eagle-import") (part "CAPACITOR_0603"))
    )
    (comp (ref "C89")
      (value "470 pF")
      (footprint "eagle-import:C0603")
      (libsource (lib "eagle-import") (part "CAPACITOR_0603"))
    )
    (comp (ref "C90")
      (value "100 nF")
      (footprint "eagle-import:C0603")
      (libsource (lib "eagle-import") (part "CAPACITOR_0603"))
    )
    (comp (ref "C91")
      (value "10 uF")
      (footprint "eagle-import:C1206")
      (libsource (lib "eagle-import") (part "CAPACITOR_1206"))
    )
    (comp (ref "C92")
      (value "100 nF")
      (footprint "eagle-import:C0603")
      (libsource (lib "eagle-import") (part "CAPACITOR_0603"))
    )
    (comp (ref "C93")
      (value "100 nF")
      (footprint "eagle-import:C0603")
      (libsource (lib "eagle-import") (part "CAPACITOR_0603"))
    )
    (comp (ref "C94")
      (value "100 nF")
      (footprint "eagle-import:C0603")
      (libsource (lib "eagle-import") (part "CAPACITOR_0603"))
    )
    (comp (ref "C100")
      (value "30 pF")
      (footprint "eagle-import:C0603")
      (libsource (lib "eagle-import") (part "CAPACITOR_0603"))
    )
    (comp (ref "C101")
      (value "4.7 uF")
      (footprint "eagle-import:C1206")
      (libsource (lib "eagle-import") (part "CAPACITOR_1206"))
    )
    (comp (ref "IC6")
      (value "LAN8742A-CZ-TR")
      (footprint "eagle-import:QFN50P400X400X100-25N")
      (fields (field (name "MOUSER_PART_NUMBER") "579-LAN8742A-CZ-TR"))
      (libsource (lib "eagle-import") (part "LAN8742A-CZ-TR"))
    )
    (comp (ref "IC13")
      (value "USBLC6-4SC6")
      (footprint "eagle-import:SOT95P280X145-6N")
      (fields (field (name "MOUSER_PART_NUMBER") "511-USBLC6-4SC6"))
      (libsource (lib "eagle-import") (part "USBLC6-4SC6"))
    )
    (comp (ref "J1")
      (value "GWLEX-SMT-S988G_Y")
      (footprint "eagle-import:GWLEXSMTS988GY")
      (fields
        (field (name "MANUFACTURER_PART_NUMBER") "GWLEX-SMT-S988G/Y")
        (field (name "MOUSER_PART_NUMBER") "806-GWLEX-SMT-S988GY")
      )
      (libsource (lib "eagle-import") (part "GWLEX-SMT-S988G_Y"))
    )
    (comp (ref "R18")
      (value "10 k")
      (footprint "eagle-import:R0603")
      (libsource (lib "eagle-import") (part "RESISTOR_0603"))
    )
    (comp (ref "R20")
      (value "10 k")
      (footprint "eagle-import:R0603")
      (libsource (lib "eagle-import") (part "RESISTOR_0603"))
    )
    (comp (ref "R21")
      (value "10 k")
      (footprint "eagle-import:R0603")
      (libsource (lib "eagle-import") (part "RESISTOR_0603"))
    )
    (comp (ref "R22")
      (value "1k5")
      (footprint "eagle-import:R0603")
      (libsource (lib "eagle-import") (part "RESISTOR_0603"))
    )
    (comp (ref "R23")
      (value "10 k")
      (footprint "eagle-import:R0603")
      (libsource (lib "eagle-import") (part "RESISTOR_0603"))
    )
    (comp (ref "R24")
      (value "33 R")
      (footprint "eagle-import:R0603")
      (libsource (lib "eagle-import") (part "RESISTOR_0603"))
    )
    (comp (ref "R25")
      (value "33 R")
      (footprint "eagle-import:R0603")
      (libsource (lib "eagle-import") (part "RESISTOR_0603"))
    )
    (comp (ref "R26")
      (value "33 R")
      (footprint "eagle-import:R0603")
      (libsource (lib "eagle-import") (part "RESISTOR_0603"))
    )
    (comp (ref "R27")
      (value "10 k")
      (footprint "eagle-import:R0603")
      (libsource (lib "eagle-import") (part "RESISTOR_0603"))
    )
    (comp (ref "R29")
      (value "75 R")
      (footprint "eagle-import:R0603")
      (libsource (lib "eagle-import") (part "RESISTOR_0603"))
    )
    (comp (ref "R77")
      (value "12k1")
      (footprint "eagle-import:R0603")
      (libsource (lib "eagle-import") (part "RESISTOR_0603"))
    )
    (comp (ref "R79")
      (value "50 R")
      (footprint "eagle-import:R0603")
      (libsource (lib "eagle-import") (part "RESISTOR_0603"))
    )
    (comp (ref "R80")
      (value "50 R")
      (footprint "eagle-import:R0603")
      (libsource (lib "eagle-import") (part "RESISTOR_0603"))
    )
    (comp (ref "R81")
      (value "50 R")
      (footprint "eagle-import:R0603")
      (libsource (lib "eagle-import") (part "RESISTOR_0603"))
    )
    (comp (ref "R82")
      (value "50 R")
      (footprint "eagle-import:R0603")
      (libsource (lib "eagle-import") (part "RESISTOR_0603"))
    )
    (comp (ref "R83")
      (value "270 R")
      (footprint "eagle-import:R0603")
      (libsource (lib "eagle-import") (part "RESISTOR_0603"))
    )
    (comp (ref "R84")
      (value "270 R")
      (footprint "eagle-import:R0603")
      (libsource (lib "eagle-import") (part "RESISTOR_0603"))
    )
    (comp (ref "R85")
      (value "10 k")
      (footprint "eagle-import:R0603")
      (libsource (lib "eagle-import") (part "RESISTOR_0603"))
    )
    (comp (ref "R88")
      (value "75 R")
      (footprint "eagle-import:R0603")
      (libsource (lib "eagle-import") (part "RESISTOR_0603"))
    )
    (comp (ref "R89")
      (value "75 R")
      (footprint "eagle-import:R0603")
      (libsource (lib "eagle-import") (part "RESISTOR_0603"))
    )
    (comp (ref "R90")
      (value "75 R")
      (footprint "eagle-import:R0603")
      (libsource (lib "eagle-import") (part "RESISTOR_0603"))
    )
    (comp (ref "R91")
      (value "0 R")
      (footprint "eagle-import:R0603")
      (libsource (lib "eagle-import") (part "RESISTOR_0603"))
    )
    (comp (ref "T1")
      (value "H1102NL")
      (footprint "eagle-import:SOIC127P940X597-16N")
      (fields (field (name "MOUSER_PART_NUMBER") "673-H1102NL"))
      (libsource (lib "eagle-import") (part "H1102NL"))
    )
    (comp (ref "Y3")
      (value "ABLS2-25.000MHZ-D4YF-T")
      (footprint "eagle-import:ABLS")
      (fields (field (name "MOUSER_PART_NUMBER") "815-ABLS2-25-D4YF-T"))
      (libsource (lib "eagle-import") (part "ABLS2-25.000MHZ-D4YF-T"))
    )
    (comp (ref "C2")
      (value "100 nF")
      (footprint "eagle-import:C0603")
      (libsource (lib "eagle-import") (part "CAPACITOR_0603"))
    )
    (comp (ref "C3")
      (value "100 nF")
      (footprint "eagle-import:C0603")
      (libsource (lib "eagle-import") (part "CAPACITOR_0603"))
    )
    (comp (ref "C9")
      (value "470 pF")
      (footprint "eagle-import:C0603")
      (libsource (lib "eagle-import") (part "CAPACITOR_0603"))
    )
    (comp (ref "C10")
      (value "470 pF")
      (footprint "eagle-import:C0603")
      (libsource (lib "eagle-import") (part "CAPACITOR_0603"))
    )
    (comp (ref "C12")
      (value "100 nF")
      (footprint "eagle-import:C0603")
      (libsource (lib "eagle-import") (part "CAPACITOR_0603"))
    )
    (comp (ref "C13")
      (value "100 nF")
      (footprint "eagle-import:C0603")
      (libsource (lib "eagle-import") (part "CAPACITOR_0603"))
    )
    (comp (ref "C15")
      (value "47 pF")
      (footprint "eagle-import:C0603")
      (libsource (lib "eagle-import") (part "CAPACITOR_0603"))
    )
    (comp (ref "C108")
      (value "100 nF")
      (footprint "eagle-import:C0603")
      (libsource (lib "eagle-import") (part "CAPACITOR_0603"))
    )
    (comp (ref "C109")
      (value "100 nF")
      (footprint "eagle-import:C0603")
      (libsource (lib "eagle-import") (part "CAPACITOR_0603"))
    )
    (comp (ref "C110")
      (value "10 uF")
      (footprint "eagle-import:C1206")
      (libsource (lib "eagle-import") (part "CAPACITOR_1206"))
    )
    (comp (ref "C111")
      (value "10 uF")
      (footprint "eagle-import:C1206")
      (libsource (lib "eagle-import") (part "CAPACITOR_1206"))
    )
    (comp (ref "D5")
      (value "FM4004-W")
      (footprint "eagle-import:DIONM5025X231N")
      (fields (field (name "MOUSER_PART_NUMBER") "583-FM4004"))
      (libsource (lib "eagle-import") (part "FM4004-W"))
    )
    (comp (ref "D8")
      (value "FM4004-W")
      (footprint "eagle-import:DIONM5025X231N")
      (fields (field (name "MOUSER_PART_NUMBER") "583-FM4004"))
      (libsource (lib "eagle-import") (part "FM4004-W"))
    )
    (comp (ref "D9")
      (value "FM4004-W")
      (footprint "eagle-import:DIONM5025X231N")
      (fields (field (name "MOUSER_PART_NUMBER") "583-FM4004"))
      (libsource (lib "eagle-import") (part "FM4004-W"))
    )
    (comp (ref "D10")
      (value "FM4004-W")
      (footprint "eagle-import:DIONM5025X231N")
      (fields (field (name "MOUSER_PART_NUMBER") "583-FM4004"))
      (libsource (lib "eagle-import") (part "FM4004-W"))
    )
    (comp (ref "IN1(R/S)")
      (value "NEUTRIK_NC3FAH")
      (footprint "eagle-import:NEUTRIK_NC3FAH")
      (libsource (lib "eagle-import") (part "NEUTRIK_NC3FAH"))
    )
    (comp (ref "IN_RIGHT")
      (value "THAT1240")
      (footprint "eagle-import:SO08")
      (fields (field (name "MOUSER_PART_NUMBER") "887-1240S08-U"))
      (libsource (lib "eagle-import") (part "THAT1240SO8-USO8-U"))
    )
    (comp (ref "OUT1(R/S)")
      (value "NEUTRIK_NC3MAH")
      (footprint "eagle-import:NEUTRIK_NC3MAH")
      (libsource (lib "eagle-import") (part "NEUTRIK_NC3MAH"))
    )
    (comp (ref "OUT_RIGHT")
      (value "THAT1646")
      (footprint "eagle-import:SO08")
      (fields (field (name "MOUSER_PART_NUMBER") "887-1646S08-U"))
      (libsource (lib "eagle-import") (part "THAT1646SO8-USO8-U"))
    )
    (comp (ref "C6")
      (value "100 nF")
      (footprint "eagle-import:C0603")
      (libsource (lib "eagle-import") (part "CAPACITOR_0603"))
    )
    (comp (ref "C7")
      (value "100 nF")
      (footprint "eagle-import:C0603")
      (libsource (lib "eagle-import") (part "CAPACITOR_0603"))
    )
    (comp (ref "C26")
      (value "100 nF")
      (footprint "eagle-import:C0603")
      (libsource (lib "eagle-import") (part "CAPACITOR_0603"))
    )
    (comp (ref "C27")
      (value "100 nF")
      (footprint "eagle-import:C0603")
      (libsource (lib "eagle-import") (part "CAPACITOR_0603"))
    )
    (comp (ref "C28")
      (value "100 nF")
      (footprint "eagle-import:C0603")
      (libsource (lib "eagle-import") (part "CAPACITOR_0603"))
    )
    (comp (ref "C29")
      (value "100 nF")
      (footprint "eagle-import:C0603")
      (libsource (lib "eagle-import") (part "CAPACITOR_0603"))
    )
    (comp (ref "IC1")
      (value "OP275")
      (footprint "eagle-import:SOIC8")
      (libsource (lib "eagle-import") (part "OP275"))
    )
    (comp (ref "U7")
      (value "THAT1240")
      (footprint "eagle-import:SO08")
      (fields (field (name "MOUSER_PART_NUMBER") "887-1240S08-U"))
      (libsource (lib "eagle-import") (part "THAT1240SO8-USO8-U"))
    )
    (comp (ref "U8")
      (value "THAT1240")
      (footprint "eagle-import:SO08")
      (fields (field (name "MOUSER_PART_NUMBER") "887-1240S08-U"))
      (libsource (lib "eagle-import") (part "THAT1240SO8-USO8-U"))
    )
  )
  (nets
    (net (code "1") (name "+3V3") (class "Default")
      (node (ref "C119") (pin "2") (pinfunction "2_2") (pintype "passive"))
      (node (ref "C59") (pin "2") (pinfunction "2_2") (pintype "passive"))
      (node (ref "C73") (pin "1") (pinfunction "1_1") (pintype "passive"))
      (node (ref "C74") (pin "1") (pinfunction "1_1") (pintype "passive"))
      (node (ref "C75") (pin "1") (pinfunction "1_1") (pintype "passive"))
      (node (ref "C76") (pin "1") (pinfunction "1_1") (pintype "passive"))
      (node (ref "C77") (pin "1") (pinfunction "1_1") (pintype "passive"))
      (node (ref "C78") (pin "1") (pinfunction "1_1") (pintype "passive"))
      (node (ref "C79") (pin "1") (pinfunction "1_1") (pintype "passive"))
      (node (ref "C80") (pin "2") (pinfunction "2_2") (pintype "passive"))
      (node (ref "C81") (pin "2") (pinfunction "2_2") (pintype "passive"))
      (node (ref "C82") (pin "2") (pinfunction "2_2") (pintype "passive"))
      (node (ref "C83") (pin "1") (pinfunction "1_1") (pintype "passive"))
      (node (ref "C84") (pin "1") (pinfunction "1_1") (pintype "passive"))
      (node (ref "C85") (pin "1") (pinfunction "1_1") (pintype "passive"))
      (node (ref "C86") (pin "2") (pinfunction "2_2") (pintype "passive"))
      (node (ref "C87") (pin "2") (pinfunction "2_2") (pintype "passive"))
      (node (ref "C90") (pin "2") (pinfunction "2_2") (pintype "passive"))
      (node (ref "C91") (pin "1") (pinfunction "1_1") (pintype "passive"))
      (node (ref "C92") (pin "2") (pinfunction "2_2") (pintype "passive"))
      (node (ref "C93") (pin "2") (pinfunction "2_2") (pintype "passive"))
      (node (ref "C94") (pin "2") (pinfunction "2_2") (pintype "passive"))
      (node (ref "DIGITAL_VOLT") (pin "1") (pinfunction "1_1") (pintype "bidirectional"))
      (node (ref "IC10") (pin "108") (pinfunction "VDD_8_108") (pintype "bidirectional"))
      (node (ref "IC10") (pin "121") (pinfunction "VDDSDMMC_121") (pintype "bidirectional"))
      (node (ref "IC10") (pin "131") (pinfunction "VDD_9_131") (pintype "bidirectional"))
      (node (ref "IC10") (pin "143") (pinfunction "PDR_ON_143") (pintype "bidirectional"))
      (node (ref "IC10") (pin "144") (pinfunction "VDD_10_144") (pintype "bidirectional"))
      (node (ref "IC10") (pin "17") (pinfunction "VDD_1_17") (pintype "bidirectional"))
      (node (ref "IC10") (pin "30") (pinfunction "VDD_2_30") (pintype "bidirectional"))
      (node (ref "IC10") (pin "32") (pinfunction "VREF+_32") (pintype "bidirectional"))
      (node (ref "IC10") (pin "33") (pinfunction "VDDA_33") (pintype "bidirectional"))
      (node (ref "IC10") (pin "39") (pinfunction "VDD_3_39") (pintype "bidirectional"))
      (node (ref "IC10") (pin "52") (pinfunction "VDD_4_52") (pintype "bidirectional"))
      (node (ref "IC10") (pin "6") (pinfunction "VBAT_6") (pintype "bidirectional"))
      (node (ref "IC10") (pin "62") (pinfunction "VDD_5_62") (pintype "bidirectional"))
      (node (ref "IC10") (pin "72") (pinfunction "VDD_6_72") (pintype "bidirectional"))
      (node (ref "IC10") (pin "84") (pinfunction "VDD_7_84") (pintype "bidirectional"))
      (node (ref "IC10") (pin "95") (pinfunction "VDDUSB_95") (pintype "bidirectional"))
      (node (ref "IC13") (pin "5") (pinfunction "VBUS_5") (pintype "bidirectional"))
      (node (ref "IC6") (pin "1") (pinfunction "VDD2A_1") (pintype "power_in"))
      (node (ref "IC6") (pin "19") (pinfunction "VDD1A_19") (pintype "power_in"))
      (node (ref "IC6") (pin "9") (pinfunction "VDDIO_9") (pintype "power_in"))
      (node (ref "R18") (pin "1") (pinfunction "1_1") (pintype "passive"))
      (node (ref "R20") (pin "1") (pinfunction "1_1") (pintype "passive"))
      (node (ref "R21") (pin "1") (pinfunction "1_1") (pintype "passive"))
      (node (ref "R22") (pin "1") (pinfunction "1_1") (pintype "passive"))
      (node (ref "R23") (pin "2") (pinfunction "2_2") (pintype "passive"))
      (node (ref "R79") (pin "2") (pinfunction "2_2") (pintype "passive"))
      (node (ref "R80") (pin "2") (pinfunction "2_2") (pintype "passive"))
      (node (ref "R81") (pin "2") (pinfunction "2_2") (pintype "passive"))
      (node (ref "R82") (pin "2") (pinfunction "2_2") (pintype "passive"))
      (node (ref "R99") (pin "2") (pinfunction "2_2") (pintype "passive"))
      (node (ref "T1") (pin "2") (pinfunction "CT_1_2") (pintype "bidirectional"))
      (node (ref "T1") (pin "7") (pinfunction "CT_2_7") (pintype "bidirectional"))
    )
    (net (code "2") (name "+3V3_SIG") (class "Default")
      (node (ref "IC10") (pin "47") (pinfunction "PB1_47") (pintype "bidirectional"))
    )
    (net (code "3") (name "+5V") (class "Default")
      (node (ref "C114") (pin "1") (pinfunction "1_1") (pintype "passive"))
      (node (ref "DIGITAL_VOLT") (pin "4") (pinfunction "4_4") (pintype "bidirectional"))
      (node (ref "DISPLAY1") (pin "3") (pinfunction "3_3") (pintype "bidirectional"))
      (node (ref "IC17") (pin "23") (pinfunction "VDRIVE_23") (pintype "bidirectional"))
      (node (ref "R100") (pin "2") (pinfunction "2_2") (pintype "passive"))
      (node (ref "R35") (pin "2") (pinfunction "2_2") (pintype "passive"))
      (node (ref "R96") (pin "1") (pinfunction "1_1") (pintype "passive"))
    )
    (net (code "4") (name "+5V(ANALOG)") (class "Default")
      (node (ref "C105") (pin "1") (pinfunction "1_1") (pintype "passive"))
      (node (ref "C14") (pin "1") (pinfunction "1_1") (pintype "passive"))
      (node (ref "C24") (pin "1") (pinfunction "1_1") (pintype "passive"))
      (node (ref "C31") (pin "1") (pinfunction "1_1") (pintype "passive"))
      (node (ref "C33") (pin "1") (pinfunction "1_1") (pintype "passive"))
      (node (ref "C34") (pin "1") (pinfunction "1_1") (pintype "passive"))
      (node (ref "C36") (pin "1") (pinfunction "1_1") (pintype "passive"))
      (node (ref "C41") (pin "1") (pinfunction "1_1") (pintype "passive"))
      (node (ref "C42") (pin "1") (pinfunction "1_1") (pintype "passive"))
      (node (ref "C51") (pin "1") (pinfunction "1_1") (pintype "passive"))
      (node (ref "C52") (pin "1") (pinfunction "1_1") (pintype "passive"))
      (node (ref "IC17") (pin "1") (pinfunction "AVCC_1_1") (pintype "bidirectional"))
      (node (ref "IC17") (pin "37") (pinfunction "AVCC_2_37") (pintype "bidirectional"))
      (node (ref "IC17") (pin "38") (pinfunction "AVCC_3_38") (pintype "bidirectional"))
      (node (ref "IC17") (pin "48") (pinfunction "AVCC_4_48") (pintype "bidirectional"))
      (node (ref "IC2") (pin "1") (pinfunction "VA_1") (pintype "bidirectional"))
      (node (ref "IC2") (pin "7") (pinfunction "VREFIN_7") (pintype "bidirectional"))
      (node (ref "IC3") (pin "1") (pinfunction "VA_1") (pintype "bidirectional"))
      (node (ref "R67") (pin "2") (pinfunction "2_2") (pintype "passive"))
      (node (ref "U1") (pin "3") (pinfunction "VO_3") (pintype "passive"))
    )
    (net (code "5") (name "+5V_SIG") (class "Default")
      (node (ref "IC10") (pin "26") (pinfunction "PC0_26") (pintype "bidirectional"))
    )
    (net (code "6") (name "+12V") (class "Default")
      (node (ref "DIGITAL_VOLT") (pin "2") (pinfunction "2_2") (pintype "bidirectional"))
    )
    (net (code "7") (name "+12V_SIG") (class "Default")
      (node (ref "IC10") (pin "42") (pinfunction "PA6_42") (pintype "bidirectional"))
    )
    (net (code "8") (name "+15V_SIG") (class "Default")
      (node (ref "IC10") (pin "34") (pinfunction "PA0_34") (pintype "bidirectional"))
    )
    (net (code "9") (name "-15V_SIG") (class "Default")
      (node (ref "IC10") (pin "37") (pinfunction "PA3_37") (pintype "bidirectional"))
    )
    (net (code "10") (name ".") (class "Default")
      (node (ref "IC14") (pin "1") (pinfunction "OUT_1") (pintype "output"))
      (node (ref "R59") (pin "2") (pinfunction "2_2") (pintype "passive"))
      (node (ref "R72") (pin "2") (pinfunction "2_2") (pintype "passive"))
    )
    (net (code "11") (name "...") (class "Default")
      (node (ref "IC7") (pin "1") (pinfunction "OUT_1") (pintype "output"))
      (node (ref "R71") (pin "2") (pinfunction "2_2") (pintype "passive"))
      (node (ref "R73") (pin "2") (pinfunction "2_2") (pintype "passive"))
    )
    (net (code "12") (name "0,5V_DAC") (class "Default")
      (node (ref "IC14") (pin "3") (pinfunction "+IN_3") (pintype "input"))
      (node (ref "IC15") (pin "1") (pinfunction "OUT_1") (pintype "output"))
      (node (ref "IC15") (pin "2") (pinfunction "-IN_2") (pintype "input"))
      (node (ref "IC7") (pin "3") (pinfunction "+IN_3") (pintype "input"))
    )
    (net (code "13") (name "1V_DAC") (class "Default")
      (node (ref "C22") (pin "1") (pinfunction "1_1") (pintype "passive"))
      (node (ref "C32") (pin "1") (pinfunction "1_1") (pintype "passive"))
      (node (ref "IC15") (pin "6") (pinfunction "-IN_6") (pintype "input"))
      (node (ref "IC15") (pin "7") (pinfunction "OUT_7") (pintype "output"))
      (node (ref "IC3") (pin "7") (pinfunction "VREFIN_7") (pintype "bidirectional"))
    )
    (net (code "14") (name "1V_DAC_UNBUFFERD") (class "Default")
      (node (ref "C19") (pin "1") (pinfunction "1_1") (pintype "passive"))
      (node (ref "C64") (pin "1") (pinfunction "1_1") (pintype "passive"))
      (node (ref "IC15") (pin "5") (pinfunction "+IN_5") (pintype "input"))
      (node (ref "R61") (pin "2") (pinfunction "2_2") (pintype "passive"))
      (node (ref "R68") (pin "1") (pinfunction "1_1") (pintype "passive"))
    )
    (net (code "15") (name "2V_DAC_REF") (class "Default")
      (node (ref "R67") (pin "1") (pinfunction "1_1") (pintype "passive"))
      (node (ref "R68") (pin "2") (pinfunction "2_2") (pintype "passive"))
      (node (ref "Z1") (pin "1") (pinfunction "K_1") (pintype "bidirectional"))
    )
    (net (code "16") (name "8MHZ_CRYSTAL_A") (class "Default")
      (node (ref "C70") (pin "1") (pinfunction "1_1") (pintype "passive"))
      (node (ref "IC10") (pin "23") (pinfunction "PH0_23") (pintype "bidirectional"))
      (node (ref "Y2") (pin "1") (pinfunction "1_1") (pintype "bidirectional"))
    )
    (net (code "17") (name "8MHZ_CRYSTAL_B") (class "Default")
      (node (ref "C69") (pin "1") (pinfunction "1_1") (pintype "passive"))
      (node (ref "IC10") (pin "24") (pinfunction "PH1_24") (pintype "bidirectional"))
      (node (ref "Y2") (pin "2") (pinfunction "2_2") (pintype "bidirectional"))
    )
    (net (code "18") (name "32.768KHZ_A") (class "Default")
      (node (ref "C66") (pin "1") (pinfunction "1_1") (pintype "passive"))
      (node (ref "IC10") (pin "8") (pinfunction "PC14_8") (pintype "bidirectional"))
      (node (ref "Y1") (pin "1") (pinfunction "1_1") (pintype "bidirectional"))
    )
    (net (code "19") (name "32.768KHZ_B") (class "Default")
      (node (ref "C65") (pin "1") (pinfunction "1_1") (pintype "passive"))
      (node (ref "IC10") (pin "9") (pinfunction "PC15_9") (pintype "bidirectional"))
      (node (ref "Y1") (pin "2") (pinfunction "2_2") (pintype "bidirectional"))
    )
    (net (code "20") (name "AGND") (class "Default")
      (node (ref "+15V_OK") (pin "1") (pinfunction "-_1") (pintype "passive"))
      (node (ref "+3V3_OK") (pin "1") (pinfunction "-_1") (pintype "passive"))
      (node (ref "+5V_OK") (pin "1") (pinfunction "-_1") (pintype "passive"))
      (node (ref "-15V_OK") (pin "2") (pinfunction "+_2") (pintype "passive"))
      (node (ref "C1") (pin "2") (pinfunction "2_2") (pintype "passive"))
      (node (ref "C100") (pin "1") (pinfunction "1_1") (pintype "passive"))
      (node (ref "C103") (pin "2") (pinfunction "2_2") (pintype "passive"))
      (node (ref "C104") (pin "2") (pinfunction "2_2") (pintype "passive"))
      (node (ref "C105") (pin "2") (pinfunction "2_2") (pintype "passive"))
      (node (ref "C11") (pin "2") (pinfunction "2_2") (pintype "passive"))
      (node (ref "C114") (pin "2") (pinfunction "2_2") (pintype "passive"))
      (node (ref "C115") (pin "2") (pinfunction "2_2") (pintype "passive"))
      (node (ref "C116") (pin "2") (pinfunction "2_2") (pintype "passive"))
      (node (ref "C117") (pin "2") (pinfunction "2_2") (pintype "passive"))
      (node (ref "C118") (pin "2") (pinfunction "2_2") (pintype "passive"))
      (node (ref "C119") (pin "1") (pinfunction "1_1") (pintype "passive"))
      (node (ref "C12") (pin "2") (pinfunction "2_2") (pintype "passive"))
      (node (ref "C13") (pin "2") (pinfunction "2_2") (pintype "passive"))
      (node (ref "C14") (pin "2") (pinfunction "2_2") (pintype "passive"))
      (node (ref "C19") (pin "2") (pinfunction "2_2") (pintype "passive"))
      (node (ref "C2") (pin "2") (pinfunction "2_2") (pintype "passive"))
      (node (ref "C20") (pin "2") (pinfunction "2_2") (pintype "passive"))
      (node (ref "C21") (pin "2") (pinfunction "2_2") (pintype "passive"))
      (node (ref "C22") (pin "2") (pinfunction "2_2") (pintype "passive"))
      (node (ref "C23") (pin "2") (pinfunction "2_2") (pintype "passive"))
      (node (ref "C24") (pin "2") (pinfunction "2_2") (pintype "passive"))
      (node (ref "C25") (pin "2") (pinfunction "2_2") (pintype "passive"))
      (node (ref "C26") (pin "2") (pinfunction "2_2") (pintype "passive"))
      (node (ref "C27") (pin "2") (pinfunction "2_2") (pintype "passive"))
      (node (ref "C28") (pin "2") (pinfunction "2_2") (pintype "passive"))
      (node (ref "C29") (pin "2") (pinfunction "2_2") (pintype "passive"))
      (node (ref "C3") (pin "2") (pinfunction "2_2") (pintype "passive"))
      (node (ref "C30") (pin "2") (pinfunction "2_2") (pintype "passive"))
      (node (ref "C31") (pin "2") (pinfunction "2_2") (pintype "passive"))
      (node (ref "C32") (pin "2") (pinfunction "2_2") (pintype "passive"))
      (node (ref "C33") (pin "2") (pinfunction "2_2") (pintype "passive"))
      (node (ref "C34") (pin "2") (pinfunction "2_2") (pintype "passive"))
      (node (ref "C35") (pin "2") (pinfunction "2_2") (pintype "passive"))
      (node (ref "C36") (pin "2") (pinfunction "2_2") (pintype "passive"))
      (node (ref "C39") (pin "2") (pinfunction "2_2") (pintype "passive"))
      (node (ref "C4") (pin "2") (pinfunction "2_2") (pintype "passive"))
      (node (ref "C40") (pin "1") (pinfunction "1_1") (pintype "passive"))
      (node (ref "C41") (pin "2") (pinfunction "2_2") (pintype "passive"))
      (node (ref "C42") (pin "2") (pinfunction "2_2") (pintype "passive"))
      (node (ref "C43") (pin "2") (pinfunction "2_2") (pintype "passive"))
      (node (ref "C44") (pin "1") (pinfunction "1_1") (pintype "passive"))
      (node (ref "C45") (pin "2") (pinfunction "2_2") (pintype "passive"))
      (node (ref "C46") (pin "2") (pinfunction "2_2") (pintype "passive"))
      (node (ref "C47") (pin "2") (pinfunction "2_2") (pintype "passive"))
      (node (ref "C48") (pin "2") (pinfunction "2_2") (pintype "passive"))
      (node (ref "C49") (pin "2") (pinfunction "2_2") (pintype "passive"))
      (node (ref "C5") (pin "2") (pinfunction "2_2") (pintype "passive"))
      (node (ref "C50") (pin "2") (pinfunction "2_2") (pintype "passive"))
      (node (ref "C51") (pin "2") (pinfunction "2_2") (pintype "passive"))
      (node (ref "C52") (pin "2") (pinfunction "2_2") (pintype "passive"))
      (node (ref "C53") (pin "2") (pinfunction "2_2") (pintype "passive"))
      (node (ref "C54") (pin "2") (pinfunction "2_2") (pintype "passive"))
      (node (ref "C57") (pin "2") (pinfunction "2_2") (pintype "passive"))
      (node (ref "C58") (pin "2") (pinfunction "2_2") (pintype "passive"))
      (node (ref "C59") (pin "1") (pinfunction "1_1") (pintype "passive"))
      (node (ref "C6") (pin "2") (pinfunction "2_2") (pintype "passive"))
      (node (ref "C60") (pin "2") (pinfunction "2_2") (pintype "passive"))
      (node (ref "C61") (pin "2") (pinfunction "2_2") (pintype "passive"))
      (node (ref "C62") (pin "2") (pinfunction "2_2") (pintype "passive"))
      (node (ref "C63") (pin "2") (pinfunction "2_2") (pintype "passive"))
      (node (ref "C64") (pin "2") (pinfunction "2_2") (pintype "passive"))
      (node (ref "C65") (pin "2") (pinfunction "2_2") (pintype "passive"))
      (node (ref "C66") (pin "2") (pinfunction "2_2") (pintype "passive"))
      (node (ref "C68") (pin "2") (pinfunction "2_2") (pintype "passive"))
      (node (ref "C69") (pin "2") (pinfunction "2_2") (pintype "passive"))
      (node (ref "C7") (pin "2") (pinfunction "2_2") (pintype "passive"))
      (node (ref "C70") (pin "2") (pinfunction "2_2") (pintype "passive"))
      (node (ref "C71") (pin "2") (pinfunction "2_2") (pintype "passive"))
      (node (ref "C72") (pin "2") (pinfunction "2_2") (pintype "passive"))
      (node (ref "C73") (pin "2") (pinfunction "2_2") (pintype "passive"))
      (node (ref "C74") (pin "2") (pinfunction "2_2") (pintype "passive"))
      (node (ref "C75") (pin "2") (pinfunction "2_2") (pintype "passive"))
      (node (ref "C76") (pin "2") (pinfunction "2_2") (pintype "passive"))
      (node (ref "C77") (pin "2") (pinfunction "2_2") (pintype "passive"))
      (node (ref "C78") (pin "2") (pinfunction "2_2") (pintype "passive"))
      (node (ref "C79") (pin "2") (pinfunction "2_2") (pintype "passive"))
      (node (ref "C8") (pin "2") (pinfunction "2_2") (pintype "passive"))
      (node (ref "C80") (pin "1") (pinfunction "1_1") (pintype "passive"))
      (node (ref "C81") (pin "1") (pinfunction "1_1") (pintype "passive"))
      (node (ref "C82") (pin "1") (pinfunction "1_1") (pintype "passive"))
      (node (ref "C83") (pin "2") (pinfunction "2_2") (pintype "passive"))
      (node (ref "C84") (pin "2") (pinfunction "2_2") (pintype "passive"))
      (node (ref "C85") (pin "2") (pinfunction "2_2") (pintype "passive"))
      (node (ref "C86") (pin "1") (pinfunction "1_1") (pintype "passive"))
      (node (ref "C87") (pin "1") (pinfunction "1_1") (pintype "passive"))
      (node (ref "C88") (pin "1") (pinfunction "1_1") (pintype "passive"))
      (node (ref "C89") (pin "1") (pinfunction "1_1") (pintype "passive"))
      (node (ref "C90") (pin "1") (pinfunction "1_1") (pintype "passive"))
      (node (ref "C91") (pin "2") (pinfunction "2_2") (pintype "passive"))
      (node (ref "C92") (pin "1") (pinfunction "1_1") (pintype "passive"))
      (node (ref "C93") (pin "1") (pinfunction "1_1") (pintype "passive"))
      (node (ref "C94") (pin "1") (pinfunction "1_1") (pintype "passive"))
      (node (ref "C95") (pin "2") (pinfunction "2_2") (pintype "passive"))
      (node (ref "C96") (pin "2") (pinfunction "2_2") (pintype "passive"))
      (node (ref "C97") (pin "2") (pinfunction "2_2") (pintype "passive"))
      (node (ref "C98") (pin "2") (pinfunction "2_2") (pintype "passive"))
      (node (ref "C99") (pin "2") (pinfunction "2_2") (pintype "passive"))
      (node (ref "IC10") (pin "107") (pinfunction "VSS_7_107") (pintype "bidirectional"))
      (node (ref "IC10") (pin "120") (pinfunction "VSS_8_120") (pintype "bidirectional"))
      (node (ref "IC10") (pin "130") (pinfunction "VSS_9_130") (pintype "bidirectional"))
      (node (ref "IC10") (pin "16") (pinfunction "VSS_1_16") (pintype "bidirectional"))
      (node (ref "IC10") (pin "31") (pinfunction "VSSA_31") (pintype "bidirectional"))
      (node (ref "IC10") (pin "38") (pinfunction "VSS_2_38") (pintype "bidirectional"))
      (node (ref "IC10") (pin "51") (pinfunction "VSS_3_51") (pintype "bidirectional"))
      (node (ref "IC10") (pin "61") (pinfunction "VSS_4_61") (pintype "bidirectional"))
      (node (ref "IC10") (pin "83") (pinfunction "VSS_5_83") (pintype "bidirectional"))
      (node (ref "IC10") (pin "94") (pinfunction "VSS_6_94") (pintype "bidirectional"))
      (node (ref "IC12") (pin "2") (pinfunction "2_2") (pintype "bidirectional"))
      (node (ref "IC12") (pin "5") (pinfunction "5_5") (pintype "bidirectional"))
      (node (ref "IC13") (pin "2") (pinfunction "GND_2") (pintype "power_in"))
      (node (ref "IC17") (pin "2") (pinfunction "AGND_1_2") (pintype "bidirectional"))
      (node (ref "IC17") (pin "26") (pinfunction "AGND_2_26") (pintype "bidirectional"))
      (node (ref "IC17") (pin "35") (pinfunction "AGND_3_35") (pintype "bidirectional"))
      (node (ref "IC17") (pin "40") (pinfunction "AGND_4_40") (pintype "bidirectional"))
      (node (ref "IC17") (pin "41") (pinfunction "AGND_5_41") (pintype "bidirectional"))
      (node (ref "IC17") (pin "43") (pinfunction "REFGND_1_43") (pintype "bidirectional"))
      (node (ref "IC17") (pin "46") (pinfunction "REFGND_2_46") (pintype "bidirectional"))
      (node (ref "IC17") (pin "47") (pinfunction "AGND_6_47") (pintype "bidirectional"))
      (node (ref "IC17") (pin "50") (pinfunction "V1GND_50") (pintype "bidirectional"))
      (node (ref "IC17") (pin "52") (pinfunction "V2GND_52") (pintype "bidirectional"))
      (node (ref "IC17") (pin "54") (pinfunction "V3GND_54") (pintype "bidirectional"))
      (node (ref "IC17") (pin "55") (pinfunction "AGND_7_55") (pintype "bidirectional"))
      (node (ref "IC17") (pin "56") (pinfunction "AGND_8_56") (pintype "bidirectional"))
      (node (ref "IC17") (pin "58") (pinfunction "V4GND_58") (pintype "bidirectional"))
      (node (ref "IC17") (pin "60") (pinfunction "V5GND_60") (pintype "bidirectional"))
      (node (ref "IC17") (pin "62") (pinfunction "V6GND_62") (pintype "bidirectional"))
      (node (ref "IC17") (pin "63") (pinfunction "AGND_9_63") (pintype "bidirectional"))
      (node (ref "IC17") (pin "64") (pinfunction "AGND_10_64") (pintype "bidirectional"))
      (node (ref "IC2") (pin "6") (pinfunction "GND_6") (pintype "bidirectional"))
      (node (ref "IC3") (pin "6") (pinfunction "GND_6") (pintype "bidirectional"))
      (node (ref "IC5") (pin "3") (pinfunction "+IN_3") (pintype "input"))
      (node (ref "IC5") (pin "5") (pinfunction "+IN_5") (pintype "input"))
      (node (ref "IC6") (pin "25") (pinfunction "EP_VSS_25") (pintype "power_in"))
      (node (ref "IC8") (pin "3") (pinfunction "+IN_3") (pintype "input"))
      (node (ref "IC8") (pin "5") (pinfunction "+IN_5") (pintype "input"))
      (node (ref "IN1(R/S)") (pin "1") (pinfunction "1_1") (pintype "bidirectional"))
      (node (ref "IN2(L/M)") (pin "1") (pinfunction "1_1") (pintype "bidirectional"))
      (node (ref "IN_LEFT") (pin "1") (pinfunction "REF_1") (pintype "passive"))
      (node (ref "IN_RIGHT") (pin "1") (pinfunction "REF_1") (pintype "passive"))
      (node (ref "OUT1(R/S)") (pin "1") (pinfunction "1_1") (pintype "bidirectional"))
      (node (ref "OUT2(L/M)") (pin "1") (pinfunction "1_1") (pintype "bidirectional"))
      (node (ref "OUT_LEFT") (pin "3") (pinfunction "GND_3") (pintype "input"))
      (node (ref "OUT_RIGHT") (pin "3") (pinfunction "GND_3") (pintype "input"))
      (node (ref "PROG.") (pin "4") (pinfunction "4_4") (pintype "bidirectional"))
      (node (ref "R104") (pin "2") (pinfunction "2_2") (pintype "passive"))
      (node (ref "R13") (pin "1") (pinfunction "1_1") (pintype "passive"))
      (node (ref "R14") (pin "2") (pinfunction "2_2") (pintype "passive"))
      (node (ref "R15") (pin "2") (pinfunction "2_2") (pintype "passive"))
      (node (ref "R16") (pin "2") (pinfunction "2_2") (pintype "passive"))
      (node (ref "R17") (pin "2") (pinfunction "2_2") (pintype "passive"))
      (node (ref "R27") (pin "1") (pinfunction "1_1") (pintype "passive"))
      (node (ref "R46") (pin "1") (pinfunction "1_1") (pintype "passive"))
      (node (ref "R47") (pin "1") (pinfunction "1_1") (pintype "passive"))
      (node (ref "R5") (pin "1") (pinfunction "1_1") (pintype "passive"))
      (node (ref "R58") (pin "1") (pinfunction "1_1") (pintype "passive"))
      (node (ref "R6") (pin "1") (pinfunction "1_1") (pintype "passive"))
      (node (ref "R60") (pin "1") (pinfunction "1_1") (pintype "passive"))
      (node (ref "R69") (pin "2") (pinfunction "2_2") (pintype "passive"))
      (node (ref "R76") (pin "1") (pinfunction "1_1") (pintype "passive"))
      (node (ref "R77") (pin "2") (pinfunction "2_2") (pintype "passive"))
      (node (ref "R78") (pin "2") (pinfunction "2_2") (pintype "passive"))
      (node (ref "R83") (pin "1") (pinfunction "1_1") (pintype "passive"))
      (node (ref "R84") (pin "1") (pinfunction "1_1") (pintype "passive"))
      (node (ref "R85") (pin "1") (pinfunction "1_1") (pintype "passive"))
      (node (ref "S1") (pin "1") (pinfunction "1_1") (pintype "bidirectional"))
      (node (ref "S1") (pin "2") (pinfunction "2_2") (pintype "bidirectional"))
      (node (ref "STAGE(LEFT)") (pin "3") (pinfunction "EC-_3") (pintype "output"))
      (node (ref "STAGE(LEFT)") (pin "6") (pinfunction "GND_6") (pintype "passive"))
      (node (ref "STAGE(RIGHT)") (pin "3") (pinfunction "EC-_3") (pintype "output"))
      (node (ref "STAGE(RIGHT)") (pin "6") (pinfunction "GND_6") (pintype "passive"))
      (node (ref "U1") (pin "2") (pinfunction "GND_2") (pintype "passive"))
      (node (ref "U4") (pin "2") (pinfunction "IN-_2") (pintype "input"))
      (node (ref "U6") (pin "1") (pinfunction "REF_1") (pintype "passive"))
      (node (ref "U7") (pin "2") (pinfunction "IN-_2") (pintype "input"))
      (node (ref "U8") (pin "1") (pinfunction "REF_1") (pintype "passive"))
      (node (ref "VCA1(LEFT)") (pin "3") (pinfunction "EC-_3") (pintype "output"))
      (node (ref "VCA1(LEFT)") (pin "6") (pinfunction "GND_6") (pintype "passive"))
      (node (ref "VCA2(RIGHT)") (pin "3") (pinfunction "EC-_3") (pintype "output"))
      (node (ref "VCA2(RIGHT)") (pin "6") (pinfunction "GND_6") (pintype "passive"))
      (node (ref "X1") (pin "4") (pinfunction "4_4") (pintype "bidirectional"))
      (node (ref "Z1") (pin "2") (pinfunction "A_2") (pintype "bidirectional"))
    )
    (net (code "21") (name "A_GND_TO_STAR") (class "Default")
      (node (ref "ANALOG_VOLT_IN") (pin "3") (pinfunction "3_3") (pintype "bidirectional"))
      (node (ref "ANALOG_VOLT_IN") (pin "4") (pinfunction "4_4") (pintype "bidirectional"))
      (node (ref "ANALOG_VOLT_OUT") (pin "3") (pinfunction "3_3") (pintype "bidirectional"))
      (node (ref "ANALOG_VOLT_OUT") (pin "4") (pinfunction "4_4") (pintype "bidirectional"))
      (node (ref "R16") (pin "1") (pinfunction "1_1") (pintype "passive"))
    )
    (net (code "22") (name "BOOT0") (class "Default")
      (node (ref "IC10") (pin "138") (pinfunction "BOOT0_138") (pintype "bidirectional"))
      (node (ref "R78") (pin "1") (pinfunction "1_1") (pintype "passive"))
    )
    (net (code "23") (name "BUSY") (class "Default")
      (node (ref "IC10") (pin "88") (pinfunction "PG3_88") (pintype "bidirectional"))
      (node (ref "IC17") (pin "14") (pinfunction "BUSY_14") (pintype "bidirectional"))
    )
    (net (code "24") (name "CHASIS") (class "Default")
      (node (ref "X1") (pin "P$1") (pinfunction "P$1_P$1") (pintype "bidirectional"))
      (node (ref "X1") (pin "P$2") (pinfunction "P$2_P$2") (pintype "bidirectional"))
    )
    (net (code "25") (name "CHASSIS") (class "Default")
      (node (ref "C106") (pin "2") (pinfunction "2_2") (pintype "passive"))
      (node (ref "C107") (pin "2") (pinfunction "2_2") (pintype "passive"))
      (node (ref "C108") (pin "2") (pinfunction "2_2") (pintype "passive"))
      (node (ref "C109") (pin "2") (pinfunction "2_2") (pintype "passive"))
      (node (ref "C15") (pin "1") (pinfunction "1_1") (pintype "passive"))
      (node (ref "C18") (pin "1") (pinfunction "1_1") (pintype "passive"))
      (node (ref "OUT1(R/S)") (pin "G") (pinfunction "G_G") (pintype "bidirectional"))
      (node (ref "OUT2(L/M)") (pin "G") (pinfunction "G_G") (pintype "bidirectional"))
      (node (ref "R17") (pin "1") (pinfunction "1_1") (pintype "passive"))
      (node (ref "R91") (pin "1") (pinfunction "1_1") (pintype "passive"))
    )
    (net (code "26") (name "CS") (class "Default")
      (node (ref "IC10") (pin "123") (pinfunction "PD7_123") (pintype "bidirectional"))
      (node (ref "IC17") (pin "13") (pinfunction "~{CS}_13") (pintype "bidirectional"))
    )
    (net (code "27") (name "CS_DAC1") (class "Default")
      (node (ref "IC10") (pin "134") (pinfunction "PB4_134") (pintype "bidirectional"))
      (node (ref "R94") (pin "2") (pinfunction "2_2") (pintype "passive"))
    )
    (net (code "28") (name "CS_DAC2") (class "Default")
      (node (ref "IC10") (pin "135") (pinfunction "PB5_135") (pintype "bidirectional"))
      (node (ref "R95") (pin "2") (pinfunction "2_2") (pintype "passive"))
    )
    (net (code "29") (name "CV_A_B") (class "Default")
      (node (ref "IC10") (pin "113") (pinfunction "PC12_113") (pintype "bidirectional"))
      (node (ref "IC17") (pin "10") (pinfunction "CONVST_B_10") (pintype "bidirectional"))
      (node (ref "IC17") (pin "9") (pinfunction "CONVST_A_9") (pintype "bidirectional"))
    )
    (net (code "30") (name "DAC2_OUT1(OFFSET_VCA1)") (class "Default")
      (node (ref "C99") (pin "1") (pinfunction "1_1") (pintype "passive"))
      (node (ref "IC9") (pin "3") (pinfunction "+IN_3") (pintype "input"))
      (node (ref "R74") (pin "2") (pinfunction "2_2") (pintype "passive"))
      (node (ref "R76") (pin "2") (pinfunction "2_2") (pintype "passive"))
    )
    (net (code "31") (name "DAC2_OUT2(OFFSET_VCA2)") (class "Default")
      (node (ref "C39") (pin "1") (pinfunction "1_1") (pintype "passive"))
      (node (ref "IC9") (pin "5") (pinfunction "+IN_5") (pintype "input"))
      (node (ref "R47") (pin "2") (pinfunction "2_2") (pintype "passive"))
      (node (ref "R75") (pin "2") (pinfunction "2_2") (pintype "passive"))
    )
    (net (code "32") (name "DAC2_OUT3") (class "Default")
      (node (ref "IC3") (pin "4") (pinfunction "VOUTC_4") (pintype "bidirectional"))
      (node (ref "R62") (pin "1") (pinfunction "1_1") (pintype "passive"))
    )
    (net (code "33") (name "DAC2_OUT4") (class "Default")
      (node (ref "IC3") (pin "5") (pinfunction "VOUTD_5") (pintype "bidirectional"))
      (node (ref "R70") (pin "1") (pinfunction "1_1") (pintype "passive"))
    )
    (net (code "34") (name "DAC_OUT1") (class "Default")
      (node (ref "IC10") (pin "40") (pinfunction "PA4_40") (pintype "bidirectional"))
      (node (ref "R57") (pin "1") (pinfunction "1_1") (pintype "passive"))
    )
    (net (code "35") (name "DAC_OUT2") (class "Default")
      (node (ref "IC10") (pin "41") (pinfunction "PA5_41") (pintype "bidirectional"))
      (node (ref "R55") (pin "1") (pinfunction "1_1") (pintype "passive"))
    )
    (net (code "36") (name "DB0") (class "Default")
      (node (ref "IC10") (pin "141") (pinfunction "PE0_141") (pintype "bidirectional"))
      (node (ref "IC17") (pin "16") (pinfunction "DB0_16") (pintype "bidirectional"))
    )
    (net (code "37") (name "DB1") (class "Default")
      (node (ref "IC10") (pin "142") (pinfunction "PE1_142") (pintype "bidirectional"))
      (node (ref "IC17") (pin "17") (pinfunction "DB1_17") (pintype "bidirectional"))
    )
    (net (code "38") (name "DB2") (class "Default")
      (node (ref "IC10") (pin "1") (pinfunction "PE2_1") (pintype "bidirectional"))
      (node (ref "IC17") (pin "18") (pinfunction "DB2_18") (pintype "bidirectional"))
    )
    (net (code "39") (name "DB3") (class "Default")
      (node (ref "IC10") (pin "2") (pinfunction "PE3_2") (pintype "bidirectional"))
      (node (ref "IC17") (pin "19") (pinfunction "DB3_19") (pintype "bidirectional"))
    )
    (net (code "40") (name "DB4") (class "Default")
      (node (ref "IC10") (pin "3") (pinfunction "PE4_3") (pintype "bidirectional"))
      (node (ref "IC17") (pin "20") (pinfunction "DB4_20") (pintype "bidirectional"))
    )
    (net (code "41") (name "DB5") (class "Default")
      (node (ref "IC10") (pin "4") (pinfunction "PE5_4") (pintype "bidirectional"))
      (node (ref "IC17") (pin "21") (pinfunction "DB5_21") (pintype "bidirectional"))
    )
    (net (code "42") (name "DB6") (class "Default")
      (node (ref "IC10") (pin "5") (pinfunction "PE6_5") (pintype "bidirectional"))
      (node (ref "IC17") (pin "22") (pinfunction "DB6_22") (pintype "bidirectional"))
    )
    (net (code "43") (name "DB7") (class "Default")
      (node (ref "IC10") (pin "58") (pinfunction "PE7_58") (pintype "bidirectional"))
      (node (ref "IC17") (pin "24") (pinfunction "DB7/DOUTA_24") (pintype "bidirectional"))
    )
    (net (code "44") (name "DB8") (class "Default")
      (node (ref "IC10") (pin "59") (pinfunction "PE8_59") (pintype "bidirectional"))
      (node (ref "IC17") (pin "25") (pinfunction "DB8/DOUTB_25") (pintype "bidirectional"))
    )
    (net (code "45") (name "DB9") (class "Default")
      (node (ref "IC10") (pin "60") (pinfunction "PE9_60") (pintype "bidirectional"))
      (node (ref "IC17") (pin "27") (pinfunction "DB9_27") (pintype "bidirectional"))
    )
    (net (code "46") (name "DB10") (class "Default")
      (node (ref "IC10") (pin "63") (pinfunction "PE10_63") (pintype "bidirectional"))
      (node (ref "IC17") (pin "28") (pinfunction "DB10_28") (pintype "bidirectional"))
    )
    (net (code "47") (name "DB11") (class "Default")
      (node (ref "IC10") (pin "64") (pinfunction "PE11_64") (pintype "bidirectional"))
      (node (ref "IC17") (pin "29") (pinfunction "DB11_29") (pintype "bidirectional"))
    )
    (net (code "48") (name "DB12") (class "Default")
      (node (ref "IC10") (pin "65") (pinfunction "PE12_65") (pintype "bidirectional"))
      (node (ref "IC17") (pin "30") (pinfunction "DB12_30") (pintype "bidirectional"))
    )
    (net (code "49") (name "DB13") (class "Default")
      (node (ref "IC10") (pin "66") (pinfunction "PE13_66") (pintype "bidirectional"))
      (node (ref "IC17") (pin "31") (pinfunction "DB13_31") (pintype "bidirectional"))
    )
    (net (code "50") (name "DB14") (class "Default")
      (node (ref "IC10") (pin "67") (pinfunction "PE14_67") (pintype "bidirectional"))
      (node (ref "IC17") (pin "32") (pinfunction "DB14/HBEN_32") (pintype "bidirectional"))
    )
    (net (code "51") (name "DB15") (class "Default")
      (node (ref "IC10") (pin "68") (pinfunction "PE15_68") (pintype "bidirectional"))
      (node (ref "IC17") (pin "33") (pinfunction "DB15/BYTE_SEL_33") (pintype "bidirectional"))
    )
    (net (code "52") (name "DEBUG1") (class "Default")
      (node (ref "DEBUG1") (pin "P$1") (pinfunction "TP_P$1") (pintype "input"))
      (node (ref "IC10") (pin "21") (pinfunction "PF9_21") (pintype "bidirectional"))
    )
    (net (code "53") (name "DEBUG2") (class "Default")
      (node (ref "DEBUG2") (pin "P$1") (pinfunction "TP_P$1") (pintype "input"))
      (node (ref "IC10") (pin "115") (pinfunction "PD1_115") (pintype "bidirectional"))
    )
    (net (code "54") (name "DIN_DAC") (class "Default")
      (node (ref "IC10") (pin "29") (pinfunction "PC3_29") (pintype "bidirectional"))
      (node (ref "R103") (pin "2") (pinfunction "2_2") (pintype "passive"))
      (node (ref "R93") (pin "2") (pinfunction "2_2") (pintype "passive"))
      (node (ref "TP04") (pin "P$1") (pinfunction "TP_P$1") (pintype "input"))
    )
    (net (code "55") (name "DISPLAY_GND_TO_STAR") (class "Default")
      (node (ref "DISPLAY1") (pin "4") (pinfunction "4_4") (pintype "bidirectional"))
      (node (ref "R69") (pin "1") (pinfunction "1_1") (pintype "passive"))
    )
    (net (code "56") (name "D_GND_TO_STAR") (class "Default")
      (node (ref "DIGITAL_VOLT") (pin "3") (pinfunction "3_3") (pintype "bidirectional"))
      (node (ref "R15") (pin "1") (pinfunction "1_1") (pintype "passive"))
    )
    (net (code "57") (name "E+_OUT_STAGE_LEFT") (class "Default")
      (node (ref "IC7") (pin "6") (pinfunction "-IN_6") (pintype "input"))
      (node (ref "IC7") (pin "7") (pinfunction "OUT_7") (pintype "output"))
      (node (ref "STAGE(LEFT)") (pin "2") (pinfunction "EC+_2") (pintype "passive"))
      (node (ref "TP02") (pin "P$1") (pinfunction "TP_P$1") (pintype "input"))
    )
    (net (code "58") (name "E+_OUT_STAGE_RIGHT") (class "Default")
      (node (ref "IC14") (pin "6") (pinfunction "-IN_6") (pintype "input"))
      (node (ref "IC14") (pin "7") (pinfunction "OUT_7") (pintype "output"))
      (node (ref "STAGE(RIGHT)") (pin "2") (pinfunction "EC+_2") (pintype "passive"))
      (node (ref "TP01") (pin "P$1") (pinfunction "TP_P$1") (pintype "input"))
    )
    (net (code "59") (name "EC+_VCA1(LFT)") (class "Default")
      (node (ref "IC9") (pin "1") (pinfunction "OUT_1") (pintype "output"))
      (node (ref "R56") (pin "2") (pinfunction "2_2") (pintype "passive"))
      (node (ref "TP37") (pin "P$1") (pinfunction "TP_P$1") (pintype "input"))
      (node (ref "VCA1(LEFT)") (pin "2") (pinfunction "EC+_2") (pintype "passive"))
    )
    (net (code "60") (name "EC+_VCA2(RIGHT)") (class "Default")
      (node (ref "IC9") (pin "7") (pinfunction "OUT_7") (pintype "output"))
      (node (ref "R54") (pin "2") (pinfunction "2_2") (pintype "passive"))
      (node (ref "TP36") (pin "P$1") (pinfunction "TP_P$1") (pintype "input"))
      (node (ref "VCA2(RIGHT)") (pin "2") (pinfunction "EC+_2") (pintype "passive"))
    )
    (net (code "61") (name "FRST") (class "Default")
      (node (ref "IC10") (pin "122") (pinfunction "PD6_122") (pintype "bidirectional"))
      (node (ref "IC17") (pin "15") (pinfunction "FRSTDATA_15") (pintype "bidirectional"))
    )
    (net (code "62") (name "L") (class "Default")
      (node (ref "IC4") (pin "3") (pinfunction "+IN_3") (pintype "input"))
      (node (ref "IN_LEFT") (pin "5") (pinfunction "SEN_5") (pintype "output"))
      (node (ref "IN_LEFT") (pin "6") (pinfunction "OUT_6") (pintype "output"))
      (node (ref "K5") (pin "Q1") (pinfunction "O_Q1") (pintype "passive"))
    )
    (net (code "63") (name "LD1") (class "Default")
      (node (ref "IC10") (pin "46") (pinfunction "PB0_46") (pintype "bidirectional"))
      (node (ref "LD1") (pin "2") (pinfunction "+_2") (pintype "passive"))
    )
    (net (code "64") (name "LD2") (class "Default")
      (node (ref "IC10") (pin "137") (pinfunction "PB7_137") (pintype "bidirectional"))
      (node (ref "LD2") (pin "2") (pinfunction "+_2") (pintype "passive"))
    )
    (net (code "65") (name "LD3") (class "Default")
      (node (ref "IC10") (pin "75") (pinfunction "PB14_75") (pintype "bidirectional"))
      (node (ref "LD3") (pin "2") (pinfunction "+_2") (pintype "passive"))
    )
    (net (code "66") (name "LED1") (class "Default")
      (node (ref "IC6") (pin "3") (pinfunction "LED1/NINT/NPME/~{REGOFF}_3") (pintype "input"))
      (node (ref "J1") (pin "10") (pinfunction "YELLOW_A_10") (pintype "bidirectional"))
    )
    (net (code "67") (name "LED2") (class "Default")
      (node (ref "IC6") (pin "2") (pinfunction "LED2/NINT/NPME/~{NINTSEL}_2") (pintype "input"))
      (node (ref "J1") (pin "12") (pinfunction "GREEN_A_12") (pintype "bidirectional"))
      (node (ref "R85") (pin "2") (pinfunction "2_2") (pintype "passive"))
    )
    (net (code "68") (name "L{slash}M_IN(VCA1_IN)") (class "Default")
      (node (ref "C102") (pin "1") (pinfunction "1_1") (pintype "passive"))
      (node (ref "IC17") (pin "49") (pinfunction "V1_49") (pintype "bidirectional"))
      (node (ref "K5") (pin "P1") (pinfunction "P_P1") (pintype "passive"))
    )
    (net (code "69") (name "L{slash}M_OUT(OUT_STAGE_LEFT)") (class "Default")
      (node (ref "IC1") (pin "3") (pinfunction "+IN_3") (pintype "input"))
      (node (ref "INSERT_AFTER_GAIN") (pin "4") (pinfunction "4_4") (pintype "bidirectional"))
      (node (ref "K6") (pin "Q1") (pinfunction "O_Q1") (pintype "passive"))
    )
    (net (code "70") (name "L{slash}M_OUT(OUT_STAGE_LEFT)_BEFORE") (class "Default")
      (node (ref "C38") (pin "2") (pinfunction "2_2") (pintype "passive"))
      (node (ref "IC17") (pin "59") (pinfunction "V5_59") (pintype "bidirectional"))
      (node (ref "IC5") (pin "1") (pinfunction "OUT_1") (pintype "output"))
      (node (ref "INSERT_AFTER_GAIN") (pin "3") (pinfunction "3_3") (pintype "bidirectional"))
      (node (ref "R28") (pin "2") (pinfunction "2_2") (pintype "passive"))
    )
    (net (code "71") (name "L{slash}M_OUT(VCA1_OUT)") (class "Default")
      (node (ref "C55") (pin "2") (pinfunction "2_2") (pintype "passive"))
      (node (ref "IC17") (pin "53") (pinfunction "V3_53") (pintype "bidirectional"))
      (node (ref "IC8") (pin "1") (pinfunction "OUT_1") (pintype "output"))
      (node (ref "INSERT_BEFORE_GAIN") (pin "3") (pinfunction "3_3") (pintype "bidirectional"))
      (node (ref "R48") (pin "2") (pinfunction "2_2") (pintype "passive"))
    )
    (net (code "72") (name "M") (class "Default")
      (node (ref "K5") (pin "S1") (pinfunction "S_S1") (pintype "passive"))
      (node (ref "U4") (pin "5") (pinfunction "SEN_5") (pintype "output"))
      (node (ref "U4") (pin "6") (pinfunction "OUT_6") (pintype "output"))
    )
    (net (code "73") (name "NEGATIVE_IN(L{slash}M)") (class "Default")
      (node (ref "IN2(L/M)") (pin "3") (pinfunction "3_3") (pintype "bidirectional"))
      (node (ref "K4") (pin "P1") (pinfunction "P_P1") (pintype "passive"))
    )
    (net (code "74") (name "NEGATIVE_IN(R{slash}S)") (class "Default")
      (node (ref "IN1(R/S)") (pin "3") (pinfunction "3_3") (pintype "bidirectional"))
      (node (ref "K1") (pin "P1") (pinfunction "P_P1") (pintype "passive"))
    )
    (net (code "75") (name "NEGATIVE_OUT(L{slash}M)") (class "Default")
      (node (ref "C106") (pin "1") (pinfunction "1_1") (pintype "passive"))
      (node (ref "D1") (pin "2") (pinfunction "A_2") (pintype "input"))
      (node (ref "D4") (pin "1") (pinfunction "K_1") (pintype "output"))
      (node (ref "K3") (pin "P1") (pinfunction "P_P1") (pintype "passive"))
      (node (ref "OUT2(L/M)") (pin "3") (pinfunction "3_3") (pintype "bidirectional"))
    )
    (net (code "76") (name "NGATIVE_OUT(R{slash}S)") (class "Default")
      (node (ref "C108") (pin "1") (pinfunction "1_1") (pintype "passive"))
      (node (ref "D5") (pin "2") (pinfunction "A_2") (pintype "input"))
      (node (ref "D9") (pin "1") (pinfunction "K_1") (pintype "output"))
      (node (ref "K2") (pin "P1") (pinfunction "P_P1") (pintype "passive"))
      (node (ref "OUT1(R/S)") (pin "3") (pinfunction "3_3") (pintype "bidirectional"))
    )
    (net (code "77") (name "NRST") (class "Default")
      (node (ref "C44") (pin "2") (pinfunction "2_2") (pintype "passive"))
      (node (ref "IC10") (pin "25") (pinfunction "NRST_25") (pintype "bidirectional"))
      (node (ref "IC6") (pin "15") (pinfunction "NRST_15") (pintype "input"))
      (node (ref "PROG.") (pin "2") (pinfunction "2_2") (pintype "bidirectional"))
      (node (ref "S1") (pin "3") (pinfunction "3_3") (pintype "bidirectional"))
      (node (ref "S1") (pin "4") (pinfunction "4_4") (pintype "bidirectional"))
    )
    (net (code "78") (name "Net-(+3V3_OK-+)") (class "Default")
      (node (ref "+3V3_OK") (pin "2") (pinfunction "+_2") (pintype "passive"))
      (node (ref "R99") (pin "1") (pinfunction "1_1") (pintype "passive"))
    )
    (net (code "79") (name "Net-(+5V_OK-+)") (class "Default")
      (node (ref "+5V_OK") (pin "2") (pinfunction "+_2") (pintype "passive"))
      (node (ref "R100") (pin "1") (pinfunction "1_1") (pintype "passive"))
    )
    (net (code "80") (name "Net-(+15V_OK-+)") (class "Default")
      (node (ref "+15V_OK") (pin "2") (pinfunction "+_2") (pintype "passive"))
      (node (ref "R98") (pin "1") (pinfunction "1_1") (pintype "passive"))
    )
    (net (code "81") (name "Net-(-15V_OK--)") (class "Default")
      (node (ref "-15V_OK") (pin "1") (pinfunction "-_1") (pintype "passive"))
      (node (ref "R97") (pin "2") (pinfunction "2_2") (pintype "passive"))
    )
    (net (code "82") (name "Net-(C10-Pad1)") (class "Default")
      (node (ref "C10") (pin "1") (pinfunction "1_1") (pintype "passive"))
      (node (ref "C15") (pin "2") (pinfunction "2_2") (pintype "passive"))
      (node (ref "C9") (pin "2") (pinfunction "2_2") (pintype "passive"))
    )
    (net (code "83") (name "Net-(C16-Pad2)") (class "Default")
      (node (ref "C16") (pin "2") (pinfunction "2_2") (pintype "passive"))
      (node (ref "C17") (pin "1") (pinfunction "1_1") (pintype "passive"))
      (node (ref "C18") (pin "2") (pinfunction "2_2") (pintype "passive"))
    )
    (net (code "84") (name "Net-(C67-Pad2)") (class "Default")
      (node (ref "C67") (pin "2") (pinfunction "2_2") (pintype "passive"))
      (node (ref "R53") (pin "1") (pinfunction "1_1") (pintype "passive"))
    )
    (net (code "85") (name "Net-(C101-Pad1)") (class "Default")
      (node (ref "C101") (pin "1") (pinfunction "1_1") (pintype "passive"))
      (node (ref "R29") (pin "1") (pinfunction "1_1") (pintype "passive"))
      (node (ref "R88") (pin "1") (pinfunction "1_1") (pintype "passive"))
      (node (ref "R89") (pin "1") (pinfunction "1_1") (pintype "passive"))
      (node (ref "R90") (pin "1") (pinfunction "1_1") (pintype "passive"))
    )
    (net (code "86") (name "Net-(C102-Pad2)") (class "Default")
      (node (ref "C102") (pin "2") (pinfunction "2_2") (pintype "passive"))
      (node (ref "R52") (pin "1") (pinfunction "1_1") (pintype "passive"))
    )
    (net (code "87") (name "Net-(IC1A--IN)") (class "Default")
      (node (ref "IC1") (pin "1") (pinfunction "OUT_1") (pintype "output"))
      (node (ref "IC1") (pin "2") (pinfunction "-IN_2") (pintype "input"))
      (node (ref "U7") (pin "3") (pinfunction "IN+_3") (pintype "input"))
      (node (ref "U8") (pin "3") (pinfunction "IN+_3") (pintype "input"))
    )
    (net (code "88") (name "Net-(IC1B--IN)") (class "Default")
      (node (ref "IC1") (pin "6") (pinfunction "-IN_6") (pintype "input"))
      (node (ref "IC1") (pin "7") (pinfunction "OUT_7") (pintype "output"))
      (node (ref "U7") (pin "1") (pinfunction "REF_1") (pintype "passive"))
      (node (ref "U8") (pin "2") (pinfunction "IN-_2") (pintype "input"))
    )
    (net (code "89") (name "Net-(IC2-DIN)") (class "Default")
      (node (ref "IC2") (pin "8") (pinfunction "DIN_8") (pintype "bidirectional"))
      (node (ref "R93") (pin "1") (pinfunction "1_1") (pintype "passive"))
    )
    (net (code "90") (name "Net-(IC2-SCLK)") (class "Default")
      (node (ref "IC2") (pin "10") (pinfunction "SCLK_10") (pintype "bidirectional"))
      (node (ref "R92") (pin "1") (pinfunction "1_1") (pintype "passive"))
    )
    (net (code "91") (name "Net-(IC2-VOUTA)") (class "Default")
      (node (ref "IC2") (pin "2") (pinfunction "VOUTA_2") (pintype "bidirectional"))
      (node (ref "R38") (pin "2") (pinfunction "2_2") (pintype "passive"))
    )
    (net (code "92") (name "Net-(IC2-VOUTB)") (class "Default")
      (node (ref "IC2") (pin "3") (pinfunction "VOUTB_3") (pintype "bidirectional"))
      (node (ref "R41") (pin "2") (pinfunction "2_2") (pintype "passive"))
    )
    (net (code "93") (name "Net-(IC2-VOUTC)") (class "Default")
      (node (ref "IC2") (pin "4") (pinfunction "VOUTC_4") (pintype "bidirectional"))
      (node (ref "R44") (pin "2") (pinfunction "2_2") (pintype "passive"))
    )
    (net (code "94") (name "Net-(IC2-VOUTD)") (class "Default")
      (node (ref "IC2") (pin "5") (pinfunction "VOUTD_5") (pintype "bidirectional"))
      (node (ref "R64") (pin "2") (pinfunction "2_2") (pintype "passive"))
    )
    (net (code "95") (name "Net-(IC2-~{SYNC})") (class "Default")
      (node (ref "IC2") (pin "9") (pinfunction "~{SYNC}_9") (pintype "bidirectional"))
      (node (ref "R94") (pin "1") (pinfunction "1_1") (pintype "passive"))
    )
    (net (code "96") (name "Net-(IC3-DIN)") (class "Default")
      (node (ref "IC3") (pin "8") (pinfunction "DIN_8") (pintype "bidirectional"))
      (node (ref "R103") (pin "1") (pinfunction "1_1") (pintype "passive"))
    )
    (net (code "97") (name "Net-(IC3-SCLK)") (class "Default")
      (node (ref "IC3") (pin "10") (pinfunction "SCLK_10") (pintype "bidirectional"))
      (node (ref "R102") (pin "1") (pinfunction "1_1") (pintype "passive"))
    )
    (net (code "98") (name "Net-(IC3-VOUTA)") (class "Default")
      (node (ref "IC3") (pin "2") (pinfunction "VOUTA_2") (pintype "bidirectional"))
      (node (ref "R74") (pin "1") (pinfunction "1_1") (pintype "passive"))
    )
    (net (code "99") (name "Net-(IC3-VOUTB)") (class "Default")
      (node (ref "IC3") (pin "3") (pinfunction "VOUTB_3") (pintype "bidirectional"))
      (node (ref "R75") (pin "1") (pinfunction "1_1") (pintype "passive"))
    )
    (net (code "100") (name "Net-(IC3-~{SYNC})") (class "Default")
      (node (ref "IC3") (pin "9") (pinfunction "~{SYNC}_9") (pintype "bidirectional"))
      (node (ref "R95") (pin "1") (pinfunction "1_1") (pintype "passive"))
    )
    (net (code "101") (name "Net-(IC4A--IN)") (class "Default")
      (node (ref "IC4") (pin "1") (pinfunction "OUT_1") (pintype "output"))
      (node (ref "IC4") (pin "2") (pinfunction "-IN_2") (pintype "input"))
      (node (ref "U4") (pin "3") (pinfunction "IN+_3") (pintype "input"))
      (node (ref "U6") (pin "3") (pinfunction "IN+_3") (pintype "input"))
    )
    (net (code "102") (name "Net-(IC5A--IN)") (class "Default")
      (node (ref "C38") (pin "1") (pinfunction "1_1") (pintype "passive"))
      (node (ref "IC5") (pin "2") (pinfunction "-IN_2") (pintype "input"))
      (node (ref "R28") (pin "1") (pinfunction "1_1") (pintype "passive"))
      (node (ref "STAGE(LEFT)") (pin "8") (pinfunction "OUT_8") (pintype "output"))
    )
    (net (code "103") (name "Net-(IC5B--IN)") (class "Default")
      (node (ref "C37") (pin "1") (pinfunction "1_1") (pintype "passive"))
      (node (ref "IC5") (pin "6") (pinfunction "-IN_6") (pintype "input"))
      (node (ref "R30") (pin "1") (pinfunction "1_1") (pintype "passive"))
      (node (ref "STAGE(RIGHT)") (pin "8") (pinfunction "OUT_8") (pintype "output"))
    )
    (net (code "104") (name "Net-(IC6-CRS_DV{slash}~{MODE2})") (class "Default")
      (node (ref "IC6") (pin "11") (pinfunction "CRS_DV/~{MODE2}_11") (pintype "bidirectional"))
      (node (ref "R21") (pin "2") (pinfunction "2_2") (pintype "passive"))
      (node (ref "R26") (pin "2") (pinfunction "2_2") (pintype "passive"))
    )
    (net (code "105") (name "Net-(IC6-RBIAS)") (class "Default")
      (node (ref "IC6") (pin "24") (pinfunction "RBIAS_24") (pintype "bidirectional"))
      (node (ref "R77") (pin "1") (pinfunction "1_1") (pintype "passive"))
    )
    (net (code "106") (name "Net-(IC6-RXD0{slash}~{MODE0})") (class "Default")
      (node (ref "IC6") (pin "8") (pinfunction "RXD0/~{MODE0}_8") (pintype "bidirectional"))
      (node (ref "R20") (pin "2") (pinfunction "2_2") (pintype "passive"))
      (node (ref "R25") (pin "2") (pinfunction "2_2") (pintype "passive"))
    )
    (net (code "107") (name "Net-(IC6-RXD1{slash}~{MODE1})") (class "Default")
      (node (ref "IC6") (pin "7") (pinfunction "RXD1/~{MODE1}_7") (pintype "bidirectional"))
      (node (ref "R18") (pin "2") (pinfunction "2_2") (pintype "passive"))
      (node (ref "R24") (pin "2") (pinfunction "2_2") (pintype "passive"))
    )
    (net (code "108") (name "Net-(IC6-RXER{slash}~{PHYAD0})") (class "Default")
      (node (ref "IC6") (pin "10") (pinfunction "RXER/~{PHYAD0}_10") (pintype "bidirectional"))
      (node (ref "R27") (pin "2") (pinfunction "2_2") (pintype "passive"))
    )
    (net (code "109") (name "Net-(IC6-VDDCR)") (class "Default")
      (node (ref "C88") (pin "2") (pinfunction "2_2") (pintype "passive"))
      (node (ref "C89") (pin "2") (pinfunction "2_2") (pintype "passive"))
      (node (ref "IC6") (pin "6") (pinfunction "VDDCR_6") (pintype "power_in"))
    )
    (net (code "110") (name "Net-(IC6-XTAL1{slash}CLKIN)") (class "Default")
      (node (ref "C100") (pin "2") (pinfunction "2_2") (pintype "passive"))
      (node (ref "IC6") (pin "5") (pinfunction "XTAL1/CLKIN_5") (pintype "input"))
      (node (ref "Y3") (pin "2") (pinfunction "2_2") (pintype "bidirectional"))
    )
    (net (code "111") (name "Net-(IC6-XTAL2)") (class "Default")
      (node (ref "C40") (pin "2") (pinfunction "2_2") (pintype "passive"))
      (node (ref "IC6") (pin "4") (pinfunction "XTAL2_4") (pintype "bidirectional"))
      (node (ref "Y3") (pin "1") (pinfunction "1_1") (pintype "bidirectional"))
    )
    (net (code "112") (name "Net-(IC7A--IN)") (class "Default")
      (node (ref "IC7") (pin "2") (pinfunction "-IN_2") (pintype "input"))
      (node (ref "R62") (pin "2") (pinfunction "2_2") (pintype "passive"))
      (node (ref "R71") (pin "1") (pinfunction "1_1") (pintype "passive"))
    )
    (net (code "113") (name "Net-(IC7B-+IN)") (class "Default")
      (node (ref "IC7") (pin "5") (pinfunction "+IN_5") (pintype "input"))
      (node (ref "R46") (pin "2") (pinfunction "2_2") (pintype "passive"))
      (node (ref "R73") (pin "1") (pinfunction "1_1") (pintype "passive"))
    )
    (net (code "114") (name "Net-(IC8A--IN)") (class "Default")
      (node (ref "C55") (pin "1") (pinfunction "1_1") (pintype "passive"))
      (node (ref "IC8") (pin "2") (pinfunction "-IN_2") (pintype "input"))
      (node (ref "R48") (pin "1") (pinfunction "1_1") (pintype "passive"))
      (node (ref "VCA1(LEFT)") (pin "8") (pinfunction "OUT_8") (pintype "output"))
    )
    (net (code "115") (name "Net-(IC8B--IN)") (class "Default")
      (node (ref "C56") (pin "1") (pinfunction "1_1") (pintype "passive"))
      (node (ref "IC8") (pin "6") (pinfunction "-IN_6") (pintype "input"))
      (node (ref "R49") (pin "1") (pinfunction "1_1") (pintype "passive"))
      (node (ref "VCA2(RIGHT)") (pin "8") (pinfunction "OUT_8") (pintype "output"))
    )
    (net (code "116") (name "Net-(IC9A--IN)") (class "Default")
      (node (ref "IC9") (pin "2") (pinfunction "-IN_2") (pintype "input"))
      (node (ref "R56") (pin "1") (pinfunction "1_1") (pintype "passive"))
      (node (ref "R57") (pin "2") (pinfunction "2_2") (pintype "passive"))
    )
    (net (code "117") (name "Net-(IC9B--IN)") (class "Default")
      (node (ref "IC9") (pin "6") (pinfunction "-IN_6") (pintype "input"))
      (node (ref "R54") (pin "1") (pinfunction "1_1") (pintype "passive"))
      (node (ref "R55") (pin "2") (pinfunction "2_2") (pintype "passive"))
    )
    (net (code "118") (name "Net-(IC10-PA9)") (class "Default")
      (node (ref "IC10") (pin "101") (pinfunction "PA9_101") (pintype "bidirectional"))
      (node (ref "R19") (pin "1") (pinfunction "1_1") (pintype "passive"))
    )
    (net (code "119") (name "Net-(IC10-VCAP_1)") (class "Default")
      (node (ref "C71") (pin "1") (pinfunction "1_1") (pintype "passive"))
      (node (ref "IC10") (pin "71") (pinfunction "VCAP_1_71") (pintype "bidirectional"))
    )
    (net (code "120") (name "Net-(IC10-VCAP_2)") (class "Default")
      (node (ref "C72") (pin "1") (pinfunction "1_1") (pintype "passive"))
      (node (ref "IC10") (pin "106") (pinfunction "VCAP_2_106") (pintype "bidirectional"))
    )
    (net (code "121") (name "Net-(IC14A--IN)") (class "Default")
      (node (ref "IC14") (pin "2") (pinfunction "-IN_2") (pintype "input"))
      (node (ref "R70") (pin "2") (pinfunction "2_2") (pintype "passive"))
      (node (ref "R72") (pin "1") (pinfunction "1_1") (pintype "passive"))
    )
    (net (code "122") (name "Net-(IC14B-+IN)") (class "Default")
      (node (ref "IC14") (pin "5") (pinfunction "+IN_5") (pintype "input"))
      (node (ref "R58") (pin "2") (pinfunction "2_2") (pintype "passive"))
      (node (ref "R59") (pin "1") (pinfunction "1_1") (pintype "passive"))
    )
    (net (code "123") (name "Net-(IC15A-+IN)") (class "Default")
      (node (ref "IC15") (pin "3") (pinfunction "+IN_3") (pintype "input"))
      (node (ref "R60") (pin "2") (pinfunction "2_2") (pintype "passive"))
      (node (ref "R61") (pin "1") (pinfunction "1_1") (pintype "passive"))
    )
    (net (code "124") (name "Net-(IC16A--IN)") (class "Default")
      (node (ref "IC16") (pin "1") (pinfunction "OUT_1") (pintype "output"))
      (node (ref "IC16") (pin "2") (pinfunction "-IN_2") (pintype "input"))
      (node (ref "U4") (pin "1") (pinfunction "REF_1") (pintype "passive"))
      (node (ref "U6") (pin "2") (pinfunction "IN-_2") (pintype "input"))
    )
    (net (code "125") (name "Net-(IC17-REFCAPA)") (class "Default")
      (node (ref "C116") (pin "1") (pinfunction "1_1") (pintype "passive"))
      (node (ref "IC17") (pin "44") (pinfunction "REFCAPA_44") (pintype "bidirectional"))
      (node (ref "IC17") (pin "45") (pinfunction "REFCAPB_45") (pintype "bidirectional"))
    )
    (net (code "126") (name "Net-(IC17-REFIN{slash}REFOUT)") (class "Default")
      (node (ref "C115") (pin "1") (pinfunction "1_1") (pintype "passive"))
      (node (ref "IC17") (pin "42") (pinfunction "REFIN/REFOUT_42") (pintype "bidirectional"))
    )
    (net (code "127") (name "Net-(IC17-REF_SELECT)") (class "Default")
      (node (ref "IC17") (pin "34") (pinfunction "REF_SELECT_34") (pintype "bidirectional"))
      (node (ref "R96") (pin "2") (pinfunction "2_2") (pintype "passive"))
    )
    (net (code "128") (name "Net-(IC17-REGCAP_1)") (class "Default")
      (node (ref "C117") (pin "1") (pinfunction "1_1") (pintype "passive"))
      (node (ref "IC17") (pin "36") (pinfunction "REGCAP_1_36") (pintype "bidirectional"))
    )
    (net (code "129") (name "Net-(IC17-REGCAP_2)") (class "Default")
      (node (ref "C118") (pin "1") (pinfunction "1_1") (pintype "passive"))
      (node (ref "IC17") (pin "39") (pinfunction "REGCAP_2_39") (pintype "bidirectional"))
    )
    (net (code "130") (name "Net-(IC17-~{PAR}{slash}SER{slash}BYTE_SEL)") (class "Default")
      (node (ref "IC17") (pin "6") (pinfunction "~{PAR}/SER/BYTE_SEL_6") (pintype "bidirectional"))
      (node (ref "R14") (pin "1") (pinfunction "1_1") (pintype "passive"))
    )
    (net (code "131") (name "Net-(IC17-~{STBY})") (class "Default")
      (node (ref "IC17") (pin "7") (pinfunction "~{STBY}_7") (pintype "bidirectional"))
      (node (ref "R35") (pin "1") (pinfunction "1_1") (pintype "passive"))
    )
    (net (code "132") (name "Net-(INSERT_BEFORE_GAIN-Pad2)") (class "Default")
      (node (ref "INSERT_BEFORE_GAIN") (pin "2") (pinfunction "2_2") (pintype "bidirectional"))
      (node (ref "R37") (pin "1") (pinfunction "1_1") (pintype "passive"))
    )
    (net (code "133") (name "Net-(INSERT_BEFORE_GAIN-Pad4)") (class "Default")
      (node (ref "INSERT_BEFORE_GAIN") (pin "4") (pinfunction "4_4") (pintype "bidirectional"))
      (node (ref "R36") (pin "1") (pinfunction "1_1") (pintype "passive"))
    )
    (net (code "134") (name "Net-(IN_LEFT-IN+)") (class "Default")
      (node (ref "C17") (pin "2") (pinfunction "2_2") (pintype "passive"))
      (node (ref "IN_LEFT") (pin "3") (pinfunction "IN+_3") (pintype "input"))
      (node (ref "K4") (pin "S2") (pinfunction "S_S2") (pintype "passive"))
    )
    (net (code "135") (name "Net-(IN_LEFT-IN-)") (class "Default")
      (node (ref "C16") (pin "1") (pinfunction "1_1") (pintype "passive"))
      (node (ref "IN_LEFT") (pin "2") (pinfunction "IN-_2") (pintype "input"))
      (node (ref "K4") (pin "S1") (pinfunction "S_S1") (pintype "passive"))
    )
    (net (code "136") (name "Net-(IN_RIGHT-IN+)") (class "Default")
      (node (ref "C10") (pin "2") (pinfunction "2_2") (pintype "passive"))
      (node (ref "IN_RIGHT") (pin "3") (pinfunction "IN+_3") (pintype "input"))
      (node (ref "K1") (pin "S2") (pinfunction "S_S2") (pintype "passive"))
    )
    (net (code "137") (name "Net-(IN_RIGHT-IN-)") (class "Default")
      (node (ref "C9") (pin "1") (pinfunction "1_1") (pintype "passive"))
      (node (ref "IN_RIGHT") (pin "2") (pinfunction "IN-_2") (pintype "input"))
      (node (ref "K1") (pin "S1") (pinfunction "S_S1") (pintype "passive"))
    )
    (net (code "138") (name "Net-(J1-13)") (class "Default")
      (node (ref "C101") (pin "2") (pinfunction "2_2") (pintype "passive"))
      (node (ref "J1") (pin "MP1") (pinfunction "13_MP1") (pintype "bidirectional"))
      (node (ref "J1") (pin "MP2") (pinfunction "14_MP2") (pintype "bidirectional"))
      (node (ref "R91") (pin "2") (pinfunction "2_2") (pintype "passive"))
    )
    (net (code "139") (name "Net-(J1-GREEN_K)") (class "Default")
      (node (ref "J1") (pin "11") (pinfunction "GREEN_K_11") (pintype "bidirectional"))
      (node (ref "R84") (pin "2") (pinfunction "2_2") (pintype "passive"))
    )
    (net (code "140") (name "Net-(J1-Pad7)") (class "Default")
      (node (ref "J1") (pin "7") (pinfunction "7_7") (pintype "bidirectional"))
      (node (ref "R29") (pin "2") (pinfunction "2_2") (pintype "passive"))
    )
    (net (code "141") (name "Net-(J1-Pad8)") (class "Default")
      (node (ref "J1") (pin "8") (pinfunction "8_8") (pintype "bidirectional"))
      (node (ref "R88") (pin "2") (pinfunction "2_2") (pintype "passive"))
    )
    (net (code "142") (name "Net-(J1-YELLOW_K)") (class "Default")
      (node (ref "J1") (pin "9") (pinfunction "YELLOW_K_9") (pintype "bidirectional"))
      (node (ref "R83") (pin "2") (pinfunction "2_2") (pintype "passive"))
    )
    (net (code "143") (name "Net-(K1B-O)") (class "Default")
      (node (ref "K1") (pin "Q1") (pinfunction "O_Q1") (pintype "passive"))
      (node (ref "K2") (pin "Q1") (pinfunction "O_Q1") (pintype "passive"))
    )
    (net (code "144") (name "Net-(K1C-O)") (class "Default")
      (node (ref "K1") (pin "Q2") (pinfunction "O_Q2") (pintype "passive"))
      (node (ref "K2") (pin "Q2") (pinfunction "O_Q2") (pintype "passive"))
    )
    (net (code "145") (name "Net-(K2B-S)") (class "Default")
      (node (ref "C110") (pin "2") (pinfunction "2_2") (pintype "passive"))
      (node (ref "K2") (pin "S1") (pinfunction "S_S1") (pintype "passive"))
      (node (ref "OUT_RIGHT") (pin "1") (pinfunction "OUT-_1") (pintype "output"))
    )
    (net (code "146") (name "Net-(K2C-S)") (class "Default")
      (node (ref "C111") (pin "2") (pinfunction "2_2") (pintype "passive"))
      (node (ref "K2") (pin "S2") (pinfunction "S_S2") (pintype "passive"))
      (node (ref "OUT_RIGHT") (pin "8") (pinfunction "OUT+_8") (pintype "output"))
    )
    (net (code "147") (name "Net-(K3B-O)") (class "Default")
      (node (ref "K3") (pin "Q1") (pinfunction "O_Q1") (pintype "passive"))
      (node (ref "K4") (pin "Q1") (pinfunction "O_Q1") (pintype "passive"))
    )
    (net (code "148") (name "Net-(K3B-S)") (class "Default")
      (node (ref "C113") (pin "2") (pinfunction "2_2") (pintype "passive"))
      (node (ref "K3") (pin "S1") (pinfunction "S_S1") (pintype "passive"))
      (node (ref "OUT_LEFT") (pin "1") (pinfunction "OUT-_1") (pintype "output"))
    )
    (net (code "149") (name "Net-(K3C-O)") (class "Default")
      (node (ref "K3") (pin "Q2") (pinfunction "O_Q2") (pintype "passive"))
      (node (ref "K4") (pin "Q2") (pinfunction "O_Q2") (pintype "passive"))
    )
    (net (code "150") (name "Net-(K3C-S)") (class "Default")
      (node (ref "C112") (pin "2") (pinfunction "2_2") (pintype "passive"))
      (node (ref "K3") (pin "S2") (pinfunction "S_S2") (pintype "passive"))
      (node (ref "OUT_LEFT") (pin "8") (pinfunction "OUT+_8") (pintype "output"))
    )
    (net (code "151") (name "Net-(K6B-P)") (class "Default")
      (node (ref "K6") (pin "P1") (pinfunction "P_P1") (pintype "passive"))
      (node (ref "K7") (pin "S1") (pinfunction "S_S1") (pintype "passive"))
      (node (ref "K8") (pin "Q1") (pinfunction "O_Q1") (pintype "passive"))
    )
    (net (code "152") (name "Net-(K6B-S)") (class "Default")
      (node (ref "K6") (pin "S1") (pinfunction "S_S1") (pintype "passive"))
      (node (ref "U7") (pin "5") (pinfunction "SEN_5") (pintype "output"))
      (node (ref "U7") (pin "6") (pinfunction "OUT_6") (pintype "output"))
    )
    (net (code "153") (name "Net-(K6C-P)") (class "Default")
      (node (ref "K6") (pin "P2") (pinfunction "P_P2") (pintype "passive"))
      (node (ref "K7") (pin "Q1") (pinfunction "O_Q1") (pintype "passive"))
      (node (ref "K8") (pin "S1") (pinfunction "S_S1") (pintype "passive"))
    )
    (net (code "154") (name "Net-(K6C-S)") (class "Default")
      (node (ref "K6") (pin "S2") (pinfunction "S_S2") (pintype "passive"))
      (node (ref "U8") (pin "5") (pinfunction "SEN_5") (pintype "output"))
      (node (ref "U8") (pin "6") (pinfunction "OUT_6") (pintype "output"))
    )
    (net (code "155") (name "Net-(LD1--)") (class "Default")
      (node (ref "LD1") (pin "1") (pinfunction "-_1") (pintype "passive"))
      (node (ref "R5") (pin "2") (pinfunction "2_2") (pintype "passive"))
    )
    (net (code "156") (name "Net-(LD2--)") (class "Default")
      (node (ref "LD2") (pin "1") (pinfunction "-_1") (pintype "passive"))
      (node (ref "R6") (pin "2") (pinfunction "2_2") (pintype "passive"))
    )
    (net (code "157") (name "Net-(LD3--)") (class "Default")
      (node (ref "LD3") (pin "1") (pinfunction "-_1") (pintype "passive"))
      (node (ref "R13") (pin "2") (pinfunction "2_2") (pintype "passive"))
    )
    (net (code "158") (name "Net-(LED1--)") (class "Default")
      (node (ref "LED1") (pin "1") (pinfunction "-_1") (pintype "passive"))
      (node (ref "R7") (pin "2") (pinfunction "2_2") (pintype "passive"))
    )
    (net (code "159") (name "Net-(LED2--)") (class "Default")
      (node (ref "LED2") (pin "1") (pinfunction "-_1") (pintype "passive"))
      (node (ref "R33") (pin "2") (pinfunction "2_2") (pintype "passive"))
    )
    (net (code "160") (name "Net-(LED3--)") (class "Default")
      (node (ref "LED3") (pin "1") (pinfunction "-_1") (pintype "passive"))
      (node (ref "R8") (pin "2") (pinfunction "2_2") (pintype "passive"))
    )
    (net (code "161") (name "Net-(LED4--)") (class "Default")
      (node (ref "LED4") (pin "1") (pinfunction "-_1") (pintype "passive"))
      (node (ref "R34") (pin "2") (pinfunction "2_2") (pintype "passive"))
    )
    (net (code "162") (name "Net-(LED5--)") (class "Default")
      (node (ref "LED5") (pin "1") (pinfunction "-_1") (pintype "passive"))
      (node (ref "R9") (pin "2") (pinfunction "2_2") (pintype "passive"))
    )
    (net (code "163") (name "Net-(LED6--)") (class "Default")
      (node (ref "LED6") (pin "1") (pinfunction "-_1") (pintype "passive"))
      (node (ref "R10") (pin "2") (pinfunction "2_2") (pintype "passive"))
    )
    (net (code "164") (name "Net-(LED7--)") (class "Default")
      (node (ref "LED7") (pin "1") (pinfunction "-_1") (pintype "passive"))
      (node (ref "R11") (pin "2") (pinfunction "2_2") (pintype "passive"))
    )
    (net (code "165") (name "Net-(LED8--)") (class "Default")
      (node (ref "LED8") (pin "1") (pinfunction "-_1") (pintype "passive"))
      (node (ref "R12") (pin "2") (pinfunction "2_2") (pintype "passive"))
    )
    (net (code "166") (name "Net-(OUT_LEFT-SEN+)") (class "Default")
      (node (ref "C112") (pin "1") (pinfunction "1_1") (pintype "passive"))
      (node (ref "OUT_LEFT") (pin "7") (pinfunction "SEN+_7") (pintype "output"))
    )
    (net (code "167") (name "Net-(OUT_LEFT-SEN-)") (class "Default")
      (node (ref "C113") (pin "1") (pinfunction "1_1") (pintype "passive"))
      (node (ref "OUT_LEFT") (pin "2") (pinfunction "SEN-_2") (pintype "passive"))
    )
    (net (code "168") (name "Net-(OUT_RIGHT-SEN+)") (class "Default")
      (node (ref "C111") (pin "1") (pinfunction "1_1") (pintype "passive"))
      (node (ref "OUT_RIGHT") (pin "7") (pinfunction "SEN+_7") (pintype "output"))
    )
    (net (code "169") (name "Net-(OUT_RIGHT-SEN-)") (class "Default")
      (node (ref "C110") (pin "1") (pinfunction "1_1") (pintype "passive"))
      (node (ref "OUT_RIGHT") (pin "2") (pinfunction "SEN-_2") (pintype "passive"))
    )
    (net (code "170") (name "Net-(STAGE(LEFT)-IN)") (class "Default")
      (node (ref "R36") (pin "2") (pinfunction "2_2") (pintype "passive"))
      (node (ref "STAGE(LEFT)") (pin "1") (pinfunction "IN_1") (pintype "input"))
    )
    (net (code "171") (name "Net-(STAGE(LEFT)-V-)") (class "Default")
      (node (ref "C47") (pin "1") (pinfunction "1_1") (pintype "passive"))
      (node (ref "R31") (pin "2") (pinfunction "2_2") (pintype "passive"))
      (node (ref "STAGE(LEFT)") (pin "5") (pinfunction "V-_5") (pintype "power_in"))
    )
    (net (code "172") (name "Net-(STAGE(RIGHT)-IN)") (class "Default")
      (node (ref "R37") (pin "2") (pinfunction "2_2") (pintype "passive"))
      (node (ref "STAGE(RIGHT)") (pin "1") (pinfunction "IN_1") (pintype "input"))
    )
    (net (code "173") (name "Net-(STAGE(RIGHT)-V-)") (class "Default")
      (node (ref "C43") (pin "1") (pinfunction "1_1") (pintype "passive"))
      (node (ref "R32") (pin "2") (pinfunction "2_2") (pintype "passive"))
      (node (ref "STAGE(RIGHT)") (pin "5") (pinfunction "V-_5") (pintype "power_in"))
    )
    (net (code "174") (name "Net-(T1-NC_4)") (class "Default")
      (node (ref "R89") (pin "2") (pinfunction "2_2") (pintype "passive"))
      (node (ref "T1") (pin "12") (pinfunction "NC_4_12") (pintype "bidirectional"))
    )
    (net (code "175") (name "Net-(T1-NC_6)") (class "Default")
      (node (ref "R90") (pin "2") (pinfunction "2_2") (pintype "passive"))
      (node (ref "T1") (pin "15") (pinfunction "NC_6_15") (pintype "bidirectional"))
    )
    (net (code "176") (name "Net-(T1-RX+)") (class "Default")
      (node (ref "J1") (pin "3") (pinfunction "3_3") (pintype "bidirectional"))
      (node (ref "T1") (pin "11") (pinfunction "RX+_11") (pintype "bidirectional"))
    )
    (net (code "177") (name "Net-(T1-RX-)") (class "Default")
      (node (ref "J1") (pin "6") (pinfunction "6_6") (pintype "bidirectional"))
      (node (ref "T1") (pin "9") (pinfunction "RX-_9") (pintype "bidirectional"))
    )
    (net (code "178") (name "Net-(T1-TX+)") (class "Default")
      (node (ref "J1") (pin "1") (pinfunction "1_1") (pintype "bidirectional"))
      (node (ref "T1") (pin "16") (pinfunction "TX+_16") (pintype "bidirectional"))
    )
    (net (code "179") (name "Net-(T1-TX-)") (class "Default")
      (node (ref "J1") (pin "2") (pinfunction "2_2") (pintype "bidirectional"))
      (node (ref "T1") (pin "14") (pinfunction "TX-_14") (pintype "bidirectional"))
    )
    (net (code "180") (name "Net-(VCA1(LEFT)-IN)") (class "Default")
      (node (ref "R52") (pin "2") (pinfunction "2_2") (pintype "passive"))
      (node (ref "VCA1(LEFT)") (pin "1") (pinfunction "IN_1") (pintype "input"))
    )
    (net (code "181") (name "Net-(VCA1(LEFT)-V-)") (class "Default")
      (node (ref "C61") (pin "1") (pinfunction "1_1") (pintype "passive"))
      (node (ref "R50") (pin "2") (pinfunction "2_2") (pintype "passive"))
      (node (ref "VCA1(LEFT)") (pin "5") (pinfunction "V-_5") (pintype "power_in"))
    )
    (net (code "182") (name "Net-(VCA2(RIGHT)-IN)") (class "Default")
      (node (ref "R53") (pin "2") (pinfunction "2_2") (pintype "passive"))
      (node (ref "VCA2(RIGHT)") (pin "1") (pinfunction "IN_1") (pintype "input"))
    )
    (net (code "183") (name "Net-(VCA2(RIGHT)-V-)") (class "Default")
      (node (ref "C58") (pin "1") (pinfunction "1_1") (pintype "passive"))
      (node (ref "R51") (pin "2") (pinfunction "2_2") (pintype "passive"))
      (node (ref "VCA2(RIGHT)") (pin "5") (pinfunction "V-_5") (pintype "power_in"))
    )
    (net (code "184") (name "OS0") (class "Default")
      (node (ref "IC10") (pin "98") (pinfunction "PC8_98") (pintype "bidirectional"))
      (node (ref "IC17") (pin "3") (pinfunction "OS_0_3") (pintype "bidirectional"))
    )
    (net (code "185") (name "OS1") (class "Default")
      (node (ref "IC10") (pin "99") (pinfunction "PC9_99") (pintype "bidirectional"))
      (node (ref "IC17") (pin "4") (pinfunction "OS_1_4") (pintype "bidirectional"))
    )
    (net (code "186") (name "OS2") (class "Default")
      (node (ref "IC10") (pin "111") (pinfunction "PC10_111") (pintype "bidirectional"))
      (node (ref "IC17") (pin "5") (pinfunction "OS_2_5") (pintype "bidirectional"))
    )
    (net (code "187") (name "OUT1_DRIVER") (class "Default")
      (node (ref "K1") (pin "2") (pinfunction "2_2") (pintype "passive"))
      (node (ref "K2") (pin "2") (pinfunction "2_2") (pintype "passive"))
      (node (ref "R33") (pin "1") (pinfunction "1_1") (pintype "passive"))
      (node (ref "R7") (pin "1") (pinfunction "1_1") (pintype "passive"))
      (node (ref "U12") (pin "16") (pinfunction "OUT1_16") (pintype "bidirectional"))
    )
    (net (code "188") (name "OUT2_DRIVER") (class "Default")
      (node (ref "K3") (pin "2") (pinfunction "2_2") (pintype "passive"))
      (node (ref "K4") (pin "2") (pinfunction "2_2") (pintype "passive"))
      (node (ref "R34") (pin "1") (pinfunction "1_1") (pintype "passive"))
      (node (ref "R8") (pin "1") (pinfunction "1_1") (pintype "passive"))
      (node (ref "U12") (pin "15") (pinfunction "OUT2_15") (pintype "bidirectional"))
    )
    (net (code "189") (name "OUT3_DRIVER") (class "Default")
      (node (ref "K5") (pin "2") (pinfunction "2_2") (pintype "passive"))
      (node (ref "R9") (pin "1") (pinfunction "1_1") (pintype "passive"))
      (node (ref "U12") (pin "14") (pinfunction "OUT3_14") (pintype "bidirectional"))
    )
    (net (code "190") (name "OUT4_DRIVER") (class "Default")
      (node (ref "K6") (pin "2") (pinfunction "2_2") (pintype "passive"))
      (node (ref "R10") (pin "1") (pinfunction "1_1") (pintype "passive"))
      (node (ref "U12") (pin "13") (pinfunction "OUT4_13") (pintype "bidirectional"))
    )
    (net (code "191") (name "OUT5_DRIVER") (class "Default")
      (node (ref "K7") (pin "2") (pinfunction "2_2") (pintype "passive"))
      (node (ref "R11") (pin "1") (pinfunction "1_1") (pintype "passive"))
      (node (ref "U12") (pin "12") (pinfunction "OUT5_12") (pintype "bidirectional"))
    )
    (net (code "192") (name "OUT6_DRIVER") (class "Default")
      (node (ref "K8") (pin "2") (pinfunction "2_2") (pintype "passive"))
      (node (ref "R12") (pin "1") (pinfunction "1_1") (pintype "passive"))
      (node (ref "U12") (pin "11") (pinfunction "OUT6_11") (pintype "bidirectional"))
    )
    (net (code "193") (name "OUT_L{slash}M") (class "Default")
      (node (ref "K8") (pin "P1") (pinfunction "P_P1") (pintype "passive"))
      (node (ref "OUT_LEFT") (pin "4") (pinfunction "IN_4") (pintype "input"))
    )
    (net (code "194") (name "OUT_R{slash}S") (class "Default")
      (node (ref "K7") (pin "P1") (pinfunction "P_P1") (pintype "passive"))
      (node (ref "OUT_RIGHT") (pin "4") (pinfunction "IN_4") (pintype "input"))
    )
    (net (code "195") (name "PB12") (class "Default")
      (node (ref "IC10") (pin "73") (pinfunction "PB12_73") (pintype "bidirectional"))
      (node (ref "TP05") (pin "P$1") (pinfunction "TP_P$1") (pintype "input"))
    )
    (net (code "196") (name "PD10") (class "Default")
      (node (ref "IC10") (pin "79") (pinfunction "PD10_79") (pintype "bidirectional"))
      (node (ref "TP08") (pin "P$1") (pinfunction "TP_P$1") (pintype "input"))
    )
    (net (code "197") (name "PD11") (class "Default")
      (node (ref "IC10") (pin "80") (pinfunction "PD11_80") (pintype "bidirectional"))
      (node (ref "TP09") (pin "P$1") (pinfunction "TP_P$1") (pintype "input"))
    )
    (net (code "198") (name "PD12") (class "Default")
      (node (ref "IC10") (pin "81") (pinfunction "PD12_81") (pintype "bidirectional"))
      (node (ref "TP10") (pin "P$1") (pinfunction "TP_P$1") (pintype "input"))
    )
    (net (code "199") (name "POSITIVE_IN(L{slash}M)") (class "Default")
      (node (ref "IN2(L/M)") (pin "2") (pinfunction "2_2") (pintype "bidirectional"))
      (node (ref "K4") (pin "P2") (pinfunction "P_P2") (pintype "passive"))
    )
    (net (code "200") (name "POSITIVE_IN(R{slash}S)") (class "Default")
      (node (ref "IN1(R/S)") (pin "2") (pinfunction "2_2") (pintype "bidirectional"))
      (node (ref "K1") (pin "P2") (pinfunction "P_P2") (pintype "passive"))
    )
    (net (code "201") (name "POSITIVE_OUT(L{slash}M)") (class "Default")
      (node (ref "C107") (pin "1") (pinfunction "1_1") (pintype "passive"))
      (node (ref "D2") (pin "2") (pinfunction "A_2") (pintype "input"))
      (node (ref "D3") (pin "1") (pinfunction "K_1") (pintype "output"))
      (node (ref "K3") (pin "P2") (pinfunction "P_P2") (pintype "passive"))
      (node (ref "OUT2(L/M)") (pin "2") (pinfunction "2_2") (pintype "bidirectional"))
    )
    (net (code "202") (name "POSITIVE_OUT(R{slash}S)") (class "Default")
      (node (ref "C109") (pin "1") (pinfunction "1_1") (pintype "passive"))
      (node (ref "D10") (pin "1") (pinfunction "K_1") (pintype "output"))
      (node (ref "D8") (pin "2") (pinfunction "A_2") (pintype "input"))
      (node (ref "K2") (pin "P2") (pinfunction "P_P2") (pintype "passive"))
      (node (ref "OUT1(R/S)") (pin "2") (pinfunction "2_2") (pintype "bidirectional"))
    )
    (net (code "203") (name "R") (class "Default")
      (node (ref "IC16") (pin "3") (pinfunction "+IN_3") (pintype "input"))
      (node (ref "IN_RIGHT") (pin "5") (pinfunction "SEN_5") (pintype "output"))
      (node (ref "IN_RIGHT") (pin "6") (pinfunction "OUT_6") (pintype "output"))
      (node (ref "K5") (pin "Q2") (pinfunction "O_Q2") (pintype "passive"))
    )
    (net (code "204") (name "RANGE") (class "Default")
      (node (ref "IC10") (pin "112") (pinfunction "PC11_112") (pintype "bidirectional"))
      (node (ref "IC17") (pin "8") (pinfunction "RANGE_8") (pintype "bidirectional"))
    )
    (net (code "205") (name "RD") (class "Default")
      (node (ref "IC10") (pin "116") (pinfunction "PD2_116") (pintype "bidirectional"))
      (node (ref "IC17") (pin "12") (pinfunction "~{RD}/SCLK_12") (pintype "bidirectional"))
    )
    (net (code "206") (name "RD_N") (class "Default")
      (node (ref "IC13") (pin "6") (pinfunction "I/O4_6") (pintype "bidirectional"))
      (node (ref "IC6") (pin "22") (pinfunction "RXN_22") (pintype "bidirectional"))
      (node (ref "R82") (pin "1") (pinfunction "1_1") (pintype "passive"))
      (node (ref "T1") (pin "8") (pinfunction "RD-_8") (pintype "bidirectional"))
    )
    (net (code "207") (name "RD_P") (class "Default")
      (node (ref "IC13") (pin "1") (pinfunction "I/O1_1") (pintype "bidirectional"))
      (node (ref "IC6") (pin "23") (pinfunction "RXP_23") (pintype "bidirectional"))
      (node (ref "R81") (pin "1") (pinfunction "1_1") (pintype "passive"))
      (node (ref "T1") (pin "6") (pinfunction "RD+_6") (pintype "bidirectional"))
    )
    (net (code "208") (name "RELAIS1") (class "Default")
      (node (ref "IC10") (pin "57") (pinfunction "PG1_57") (pintype "bidirectional"))
      (node (ref "U12") (pin "1") (pinfunction "IN1_1") (pintype "bidirectional"))
    )
    (net (code "209") (name "RELAIS2") (class "Default")
      (node (ref "IC10") (pin "56") (pinfunction "PG0_56") (pintype "bidirectional"))
      (node (ref "U12") (pin "2") (pinfunction "IN2_2") (pintype "bidirectional"))
    )
    (net (code "210") (name "RELAIS3") (class "Default")
      (node (ref "IC10") (pin "132") (pinfunction "PG15_132") (pintype "bidirectional"))
      (node (ref "U12") (pin "3") (pinfunction "IN3_3") (pintype "bidirectional"))
    )
    (net (code "211") (name "RELAIS4") (class "Default")
      (node (ref "IC10") (pin "125") (pinfunction "PG10_125") (pintype "bidirectional"))
      (node (ref "U12") (pin "4") (pinfunction "IN4_4") (pintype "bidirectional"))
    )
    (net (code "212") (name "RELAIS5") (class "Default")
      (node (ref "IC10") (pin "127") (pinfunction "PG12_127") (pintype "bidirectional"))
      (node (ref "U12") (pin "5") (pinfunction "IN5_5") (pintype "bidirectional"))
    )
    (net (code "213") (name "RELAIS6") (class "Default")
      (node (ref "IC10") (pin "124") (pinfunction "PG9_124") (pintype "bidirectional"))
      (node (ref "U12") (pin "6") (pinfunction "IN6_6") (pintype "bidirectional"))
    )
    (net (code "214") (name "RELAIS_TO_STAR_GND") (class "Default")
      (node (ref "R104") (pin "1") (pinfunction "1_1") (pintype "passive"))
      (node (ref "U12") (pin "8") (pinfunction "GND_8") (pintype "bidirectional"))
    )
    (net (code "215") (name "RESET") (class "Default")
      (node (ref "IC10") (pin "87") (pinfunction "PG2_87") (pintype "bidirectional"))
      (node (ref "IC17") (pin "11") (pinfunction "RESET_11") (pintype "bidirectional"))
    )
    (net (code "216") (name "RMII_CRS_DV") (class "Default")
      (node (ref "IC10") (pin "43") (pinfunction "PA7_43") (pintype "bidirectional"))
      (node (ref "R26") (pin "1") (pinfunction "1_1") (pintype "passive"))
    )
    (net (code "217") (name "RMII_MDC") (class "Default")
      (node (ref "IC10") (pin "27") (pinfunction "PC1_27") (pintype "bidirectional"))
      (node (ref "IC6") (pin "13") (pinfunction "MDC_13") (pintype "bidirectional"))
    )
    (net (code "218") (name "RMII_MDIO") (class "Default")
      (node (ref "IC10") (pin "36") (pinfunction "PA2_36") (pintype "bidirectional"))
      (node (ref "IC6") (pin "12") (pinfunction "MDIO_12") (pintype "bidirectional"))
      (node (ref "R22") (pin "2") (pinfunction "2_2") (pintype "passive"))
    )
    (net (code "219") (name "RMII_REF_CLK") (class "Default")
      (node (ref "IC10") (pin "35") (pinfunction "PA1_35") (pintype "bidirectional"))
      (node (ref "IC6") (pin "14") (pinfunction "NINT/REFCLKO_14") (pintype "output"))
      (node (ref "R23") (pin "1") (pinfunction "1_1") (pintype "passive"))
    )
    (net (code "220") (name "RMII_RXD0") (class "Default")
      (node (ref "IC10") (pin "44") (pinfunction "PC4_44") (pintype "bidirectional"))
      (node (ref "R25") (pin "1") (pinfunction "1_1") (pintype "passive"))
    )
    (net (code "221") (name "RMII_RXD1") (class "Default")
      (node (ref "IC10") (pin "45") (pinfunction "PC5_45") (pintype "bidirectional"))
      (node (ref "R24") (pin "1") (pinfunction "1_1") (pintype "passive"))
    )
    (net (code "222") (name "RMII_TXD0") (class "Default")
      (node (ref "IC10") (pin "128") (pinfunction "PG13_128") (pintype "bidirectional"))
      (node (ref "IC6") (pin "17") (pinfunction "TXD0_17") (pintype "bidirectional"))
    )
    (net (code "223") (name "RMII_TXD1") (class "Default")
      (node (ref "IC10") (pin "74") (pinfunction "PB13_74") (pintype "bidirectional"))
      (node (ref "IC6") (pin "18") (pinfunction "TXD1_18") (pintype "bidirectional"))
    )
    (net (code "224") (name "RMII_TX_EN") (class "Default")
      (node (ref "IC10") (pin "126") (pinfunction "PG11_126") (pintype "bidirectional"))
      (node (ref "IC6") (pin "16") (pinfunction "TXEN_16") (pintype "bidirectional"))
    )
    (net (code "225") (name "R{slash}S_IN(VCA2_IN)") (class "Default")
      (node (ref "C67") (pin "1") (pinfunction "1_1") (pintype "passive"))
      (node (ref "IC17") (pin "51") (pinfunction "V2_51") (pintype "bidirectional"))
      (node (ref "K5") (pin "P2") (pinfunction "P_P2") (pintype "passive"))
    )
    (net (code "226") (name "R{slash}S_OUT(OUT_STAGE_RIGHT)") (class "Default")
      (node (ref "IC1") (pin "5") (pinfunction "+IN_5") (pintype "input"))
      (node (ref "INSERT_AFTER_GAIN") (pin "2") (pinfunction "2_2") (pintype "bidirectional"))
      (node (ref "K6") (pin "Q2") (pinfunction "O_Q2") (pintype "passive"))
    )
    (net (code "227") (name "R{slash}S_OUT(OUT_STAGE_RIGHT)_BEFORE") (class "Default")
      (node (ref "C37") (pin "2") (pinfunction "2_2") (pintype "passive"))
      (node (ref "IC17") (pin "61") (pinfunction "V6_61") (pintype "bidirectional"))
      (node (ref "IC5") (pin "7") (pinfunction "OUT_7") (pintype "output"))
      (node (ref "INSERT_AFTER_GAIN") (pin "1") (pinfunction "1_1") (pintype "bidirectional"))
      (node (ref "R30") (pin "2") (pinfunction "2_2") (pintype "passive"))
    )
    (net (code "228") (name "R{slash}S_OUT(VCA2_OUT)") (class "Default")
      (node (ref "C56") (pin "2") (pinfunction "2_2") (pintype "passive"))
      (node (ref "IC17") (pin "57") (pinfunction "V4_57") (pintype "bidirectional"))
      (node (ref "IC8") (pin "7") (pinfunction "OUT_7") (pintype "output"))
      (node (ref "INSERT_BEFORE_GAIN") (pin "1") (pinfunction "1_1") (pintype "bidirectional"))
      (node (ref "R49") (pin "2") (pinfunction "2_2") (pintype "passive"))
    )
    (net (code "229") (name "S") (class "Default")
      (node (ref "K5") (pin "S2") (pinfunction "S_S2") (pintype "passive"))
      (node (ref "U6") (pin "5") (pinfunction "SEN_5") (pintype "output"))
      (node (ref "U6") (pin "6") (pinfunction "OUT_6") (pintype "output"))
    )
    (net (code "230") (name "SCLK_DAC") (class "Default")
      (node (ref "IC10") (pin "69") (pinfunction "PB10_69") (pintype "bidirectional"))
      (node (ref "R102") (pin "2") (pinfunction "2_2") (pintype "passive"))
      (node (ref "R92") (pin "2") (pinfunction "2_2") (pintype "passive"))
      (node (ref "TP03") (pin "P$1") (pinfunction "TP_P$1") (pintype "input"))
    )
    (net (code "231") (name "SWCLK") (class "Default")
      (node (ref "IC10") (pin "109") (pinfunction "PA14_109") (pintype "bidirectional"))
      (node (ref "PROG.") (pin "1") (pinfunction "1_1") (pintype "bidirectional"))
    )
    (net (code "232") (name "SWDIO") (class "Default")
      (node (ref "IC10") (pin "105") (pinfunction "PA13_105") (pintype "bidirectional"))
      (node (ref "PROG.") (pin "3") (pinfunction "3_3") (pintype "bidirectional"))
    )
    (net (code "233") (name "SYM1") (class "Default")
      (node (ref "R38") (pin "1") (pinfunction "1_1") (pintype "passive"))
      (node (ref "R40") (pin "2") (pinfunction "2_2") (pintype "passive"))
      (node (ref "VCA1(LEFT)") (pin "4") (pinfunction "SYM_4") (pintype "passive"))
    )
    (net (code "234") (name "SYM2") (class "Default")
      (node (ref "R41") (pin "1") (pinfunction "1_1") (pintype "passive"))
      (node (ref "R43") (pin "2") (pinfunction "2_2") (pintype "passive"))
      (node (ref "VCA2(RIGHT)") (pin "4") (pinfunction "SYM_4") (pintype "passive"))
    )
    (net (code "235") (name "SYM3") (class "Default")
      (node (ref "R44") (pin "1") (pinfunction "1_1") (pintype "passive"))
      (node (ref "R63") (pin "2") (pinfunction "2_2") (pintype "passive"))
      (node (ref "STAGE(LEFT)") (pin "4") (pinfunction "SYM_4") (pintype "passive"))
    )
    (net (code "236") (name "SYM4") (class "Default")
      (node (ref "R64") (pin "1") (pinfunction "1_1") (pintype "passive"))
      (node (ref "R66") (pin "2") (pinfunction "2_2") (pintype "passive"))
      (node (ref "STAGE(RIGHT)") (pin "4") (pinfunction "SYM_4") (pintype "passive"))
    )
    (net (code "237") (name "TD_N") (class "Default")
      (node (ref "IC13") (pin "4") (pinfunction "I/O3_4") (pintype "bidirectional"))
      (node (ref "IC6") (pin "20") (pinfunction "TXN_20") (pintype "bidirectional"))
      (node (ref "R80") (pin "1") (pinfunction "1_1") (pintype "passive"))
      (node (ref "T1") (pin "3") (pinfunction "TD-_3") (pintype "bidirectional"))
    )
    (net (code "238") (name "TD_P") (class "Default")
      (node (ref "IC13") (pin "3") (pinfunction "I/O2_3") (pintype "bidirectional"))
      (node (ref "IC6") (pin "21") (pinfunction "TXP_21") (pintype "bidirectional"))
      (node (ref "R79") (pin "1") (pinfunction "1_1") (pintype "passive"))
      (node (ref "T1") (pin "1") (pinfunction "TD+_1") (pintype "bidirectional"))
    )
    (net (code "239") (name "USART1_RX") (class "Default")
      (node (ref "IC10") (pin "76") (pinfunction "PB15_76") (pintype "bidirectional"))
    )
    (net (code "240") (name "USART1_TX") (class "Default")
      (node (ref "IC10") (pin "136") (pinfunction "PB6_136") (pintype "bidirectional"))
    )
    (net (code "241") (name "USART3_RX") (class "Default")
      (node (ref "IC10") (pin "77") (pinfunction "PD8_77") (pintype "bidirectional"))
      (node (ref "TP06") (pin "P$1") (pinfunction "TP_P$1") (pintype "input"))
    )
    (net (code "242") (name "USART3_TX") (class "Default")
      (node (ref "IC10") (pin "78") (pinfunction "PD9_78") (pintype "bidirectional"))
      (node (ref "TP07") (pin "P$1") (pinfunction "TP_P$1") (pintype "input"))
    )
    (net (code "243") (name "USART6_RX") (class "Default")
      (node (ref "DISPLAY1") (pin "2") (pinfunction "2_2") (pintype "bidirectional"))
      (node (ref "IC10") (pin "97") (pinfunction "PC7_97") (pintype "bidirectional"))
    )
    (net (code "244") (name "USART6_TX") (class "Default")
      (node (ref "DISPLAY1") (pin "1") (pinfunction "1_1") (pintype "bidirectional"))
      (node (ref "IC10") (pin "96") (pinfunction "PC6_96") (pintype "bidirectional"))
    )
    (net (code "245") (name "USB_ID") (class "Default")
      (node (ref "IC10") (pin "102") (pinfunction "PA10_102") (pintype "bidirectional"))
    )
    (net (code "246") (name "USB_N") (class "Default")
      (node (ref "IC10") (pin "103") (pinfunction "PA11_103") (pintype "bidirectional"))
      (node (ref "IC12") (pin "3") (pinfunction "3_3") (pintype "bidirectional"))
      (node (ref "X1") (pin "2") (pinfunction "2_2") (pintype "bidirectional"))
    )
    (net (code "247") (name "USB_OVERCURRENT") (class "Default")
      (node (ref "IC10") (pin "92") (pinfunction "PG7_92") (pintype "bidirectional"))
    )
    (net (code "248") (name "USB_P") (class "Default")
      (node (ref "IC10") (pin "104") (pinfunction "PA12_104") (pintype "bidirectional"))
      (node (ref "IC12") (pin "6") (pinfunction "6_6") (pintype "bidirectional"))
      (node (ref "X1") (pin "3") (pinfunction "3_3") (pintype "bidirectional"))
    )
    (net (code "249") (name "USB_POWERSWITCHON") (class "Default")
      (node (ref "IC10") (pin "91") (pinfunction "PG6_91") (pintype "bidirectional"))
    )
    (net (code "250") (name "USB_SOF") (class "Default")
      (node (ref "IC10") (pin "100") (pinfunction "PA8_100") (pintype "bidirectional"))
    )
    (net (code "251") (name "USB_VBUS") (class "Default")
      (node (ref "IC12") (pin "1") (pinfunction "1_1") (pintype "bidirectional"))
      (node (ref "R19") (pin "2") (pinfunction "2_2") (pintype "passive"))
      (node (ref "X1") (pin "1") (pinfunction "1_1") (pintype "bidirectional"))
    )
    (net (code "252") (name "V+") (class "Default")
      (node (ref "ANALOG_VOLT_IN") (pin "1") (pinfunction "1_1") (pintype "bidirectional"))
      (node (ref "ANALOG_VOLT_OUT") (pin "1") (pinfunction "1_1") (pintype "bidirectional"))
      (node (ref "C103") (pin "1") (pinfunction "1_1") (pintype "passive"))
      (node (ref "C104") (pin "1") (pinfunction "1_1") (pintype "passive"))
      (node (ref "C12") (pin "1") (pinfunction "1_1") (pintype "passive"))
      (node (ref "C21") (pin "1") (pinfunction "1_1") (pintype "passive"))
      (node (ref "C25") (pin "1") (pinfunction "1_1") (pintype "passive"))
      (node (ref "C27") (pin "1") (pinfunction "1_1") (pintype "passive"))
      (node (ref "C29") (pin "1") (pinfunction "1_1") (pintype "passive"))
      (node (ref "C3") (pin "1") (pinfunction "1_1") (pintype "passive"))
      (node (ref "C30") (pin "1") (pinfunction "1_1") (pintype "passive"))
      (node (ref "C4") (pin "1") (pinfunction "1_1") (pintype "passive"))
      (node (ref "C45") (pin "1") (pinfunction "1_1") (pintype "passive"))
      (node (ref "C46") (pin "1") (pinfunction "1_1") (pintype "passive"))
      (node (ref "C48") (pin "1") (pinfunction "1_1") (pintype "passive"))
      (node (ref "C50") (pin "1") (pinfunction "1_1") (pintype "passive"))
      (node (ref "C54") (pin "1") (pinfunction "1_1") (pintype "passive"))
      (node (ref "C6") (pin "1") (pinfunction "1_1") (pintype "passive"))
      (node (ref "C60") (pin "1") (pinfunction "1_1") (pintype "passive"))
      (node (ref "C62") (pin "1") (pinfunction "1_1") (pintype "passive"))
      (node (ref "C63") (pin "1") (pinfunction "1_1") (pintype "passive"))
      (node (ref "C8") (pin "1") (pinfunction "1_1") (pintype "passive"))
      (node (ref "C95") (pin "1") (pinfunction "1_1") (pintype "passive"))
      (node (ref "C97") (pin "1") (pinfunction "1_1") (pintype "passive"))
      (node (ref "D1") (pin "1") (pinfunction "K_1") (pintype "output"))
      (node (ref "D2") (pin "1") (pinfunction "K_1") (pintype "output"))
      (node (ref "D5") (pin "1") (pinfunction "K_1") (pintype "output"))
      (node (ref "D8") (pin "1") (pinfunction "K_1") (pintype "output"))
      (node (ref "IC1") (pin "8") (pinfunction "V+_8") (pintype "power_in"))
      (node (ref "IC14") (pin "8") (pinfunction "V+_8") (pintype "power_in"))
      (node (ref "IC15") (pin "8") (pinfunction "V+_8") (pintype "power_in"))
      (node (ref "IC16") (pin "8") (pinfunction "V+_8") (pintype "power_in"))
      (node (ref "IC4") (pin "8") (pinfunction "V+_8") (pintype "power_in"))
      (node (ref "IC5") (pin "8") (pinfunction "V+_8") (pintype "power_in"))
      (node (ref "IC7") (pin "8") (pinfunction "V+_8") (pintype "power_in"))
      (node (ref "IC8") (pin "8") (pinfunction "V+_8") (pintype "power_in"))
      (node (ref "IC9") (pin "8") (pinfunction "V+_8") (pintype "power_in"))
      (node (ref "IN_LEFT") (pin "7") (pinfunction "V+_7") (pintype "power_in"))
      (node (ref "IN_RIGHT") (pin "7") (pinfunction "V+_7") (pintype "power_in"))
      (node (ref "K1") (pin "1") (pinfunction "1_1") (pintype "passive"))
      (node (ref "K2") (pin "1") (pinfunction "1_1") (pintype "passive"))
      (node (ref "K3") (pin "1") (pinfunction "1_1") (pintype "passive"))
      (node (ref "K4") (pin "1") (pinfunction "1_1") (pintype "passive"))
      (node (ref "K5") (pin "1") (pinfunction "1_1") (pintype "passive"))
      (node (ref "K6") (pin "1") (pinfunction "1_1") (pintype "passive"))
      (node (ref "K7") (pin "1") (pinfunction "1_1") (pintype "passive"))
      (node (ref "K8") (pin "1") (pinfunction "1_1") (pintype "passive"))
      (node (ref "LED1") (pin "2") (pinfunction "+_2") (pintype "passive"))
      (node (ref "LED2") (pin "2") (pinfunction "+_2") (pintype "passive"))
      (node (ref "LED3") (pin "2") (pinfunction "+_2") (pintype "passive"))
      (node (ref "LED4") (pin "2") (pinfunction "+_2") (pintype "passive"))
      (node (ref "LED5") (pin "2") (pinfunction "+_2") (pintype "passive"))
      (node (ref "LED6") (pin "2") (pinfunction "+_2") (pintype "passive"))
      (node (ref "LED7") (pin "2") (pinfunction "+_2") (pintype "passive"))
      (node (ref "LED8") (pin "2") (pinfunction "+_2") (pintype "passive"))
      (node (ref "OUT_LEFT") (pin "6") (pinfunction "V+_6") (pintype "power_in"))
      (node (ref "OUT_RIGHT") (pin "6") (pinfunction "V+_6") (pintype "power_in"))
      (node (ref "R98") (pin "2") (pinfunction "2_2") (pintype "passive"))
      (node (ref "STAGE(LEFT)") (pin "7") (pinfunction "V+_7") (pintype "power_in"))
      (node (ref "STAGE(RIGHT)") (pin "7") (pinfunction "V+_7") (pintype "power_in"))
      (node (ref "U1") (pin "1") (pinfunction "VI_1") (pintype "input"))
      (node (ref "U12") (pin "9") (pinfunction "COM_9") (pintype "bidirectional"))
      (node (ref "U4") (pin "7") (pinfunction "V+_7") (pintype "power_in"))
      (node (ref "U6") (pin "7") (pinfunction "V+_7") (pintype "power_in"))
      (node (ref "U7") (pin "7") (pinfunction "V+_7") (pintype "power_in"))
      (node (ref "U8") (pin "7") (pinfunction "V+_7") (pintype "power_in"))
      (node (ref "VCA1(LEFT)") (pin "7") (pinfunction "V+_7") (pintype "power_in"))
      (node (ref "VCA2(RIGHT)") (pin "7") (pinfunction "V+_7") (pintype "power_in"))
    )
    (net (code "253") (name "V-") (class "Default")
      (node (ref "ANALOG_VOLT_IN") (pin "2") (pinfunction "2_2") (pintype "bidirectional"))
      (node (ref "ANALOG_VOLT_OUT") (pin "2") (pinfunction "2_2") (pintype "bidirectional"))
      (node (ref "C1") (pin "1") (pinfunction "1_1") (pintype "passive"))
      (node (ref "C11") (pin "1") (pinfunction "1_1") (pintype "passive"))
      (node (ref "C13") (pin "1") (pinfunction "1_1") (pintype "passive"))
      (node (ref "C2") (pin "1") (pinfunction "1_1") (pintype "passive"))
      (node (ref "C20") (pin "1") (pinfunction "1_1") (pintype "passive"))
      (node (ref "C23") (pin "1") (pinfunction "1_1") (pintype "passive"))
      (node (ref "C26") (pin "1") (pinfunction "1_1") (pintype "passive"))
      (node (ref "C28") (pin "1") (pinfunction "1_1") (pintype "passive"))
      (node (ref "C35") (pin "1") (pinfunction "1_1") (pintype "passive"))
      (node (ref "C49") (pin "1") (pinfunction "1_1") (pintype "passive"))
      (node (ref "C5") (pin "1") (pinfunction "1_1") (pintype "passive"))
      (node (ref "C53") (pin "1") (pinfunction "1_1") (pintype "passive"))
      (node (ref "C57") (pin "1") (pinfunction "1_1") (pintype "passive"))
      (node (ref "C68") (pin "1") (pinfunction "1_1") (pintype "passive"))
      (node (ref "C7") (pin "1") (pinfunction "1_1") (pintype "passive"))
      (node (ref "C96") (pin "1") (pinfunction "1_1") (pintype "passive"))
      (node (ref "C98") (pin "1") (pinfunction "1_1") (pintype "passive"))
      (node (ref "D10") (pin "2") (pinfunction "A_2") (pintype "input"))
      (node (ref "D3") (pin "2") (pinfunction "A_2") (pintype "input"))
      (node (ref "D4") (pin "2") (pinfunction "A_2") (pintype "input"))
      (node (ref "D9") (pin "2") (pinfunction "A_2") (pintype "input"))
      (node (ref "IC1") (pin "4") (pinfunction "V-_4") (pintype "power_in"))
      (node (ref "IC14") (pin "4") (pinfunction "V-_4") (pintype "power_in"))
      (node (ref "IC15") (pin "4") (pinfunction "V-_4") (pintype "power_in"))
      (node (ref "IC16") (pin "4") (pinfunction "V-_4") (pintype "power_in"))
      (node (ref "IC4") (pin "4") (pinfunction "V-_4") (pintype "power_in"))
      (node (ref "IC5") (pin "4") (pinfunction "V-_4") (pintype "power_in"))
      (node (ref "IC7") (pin "4") (pinfunction "V-_4") (pintype "power_in"))
      (node (ref "IC8") (pin "4") (pinfunction "V-_4") (pintype "power_in"))
      (node (ref "IC9") (pin "4") (pinfunction "V-_4") (pintype "power_in"))
      (node (ref "IN_LEFT") (pin "4") (pinfunction "V-_4") (pintype "power_in"))
      (node (ref "IN_RIGHT") (pin "4") (pinfunction "V-_4") (pintype "power_in"))
      (node (ref "OUT_LEFT") (pin "5") (pinfunction "V-_5") (pintype "power_in"))
      (node (ref "OUT_RIGHT") (pin "5") (pinfunction "V-_5") (pintype "power_in"))
      (node (ref "R31") (pin "1") (pinfunction "1_1") (pintype "passive"))
      (node (ref "R32") (pin "1") (pinfunction "1_1") (pintype "passive"))
      (node (ref "R40") (pin "1") (pinfunction "1_1") (pintype "passive"))
      (node (ref "R43") (pin "1") (pinfunction "1_1") (pintype "passive"))
      (node (ref "R50") (pin "1") (pinfunction "1_1") (pintype "passive"))
      (node (ref "R51") (pin "1") (pinfunction "1_1") (pintype "passive"))
      (node (ref "R63") (pin "1") (pinfunction "1_1") (pintype "passive"))
      (node (ref "R66") (pin "1") (pinfunction "1_1") (pintype "passive"))
      (node (ref "R97") (pin "1") (pinfunction "1_1") (pintype "passive"))
      (node (ref "U4") (pin "4") (pinfunction "V-_4") (pintype "power_in"))
      (node (ref "U6") (pin "4") (pinfunction "V-_4") (pintype "power_in"))
      (node (ref "U7") (pin "4") (pinfunction "V-_4") (pintype "power_in"))
      (node (ref "U8") (pin "4") (pinfunction "V-_4") (pintype "power_in"))
    )
    (net (code "254") (name "unconnected-(IC10-PA15-Pad110)") (class "Default")
      (node (ref "IC10") (pin "110") (pinfunction "PA15_110") (pintype "bidirectional"))
    )
    (net (code "255") (name "unconnected-(IC10-PB2-Pad48)") (class "Default")
      (node (ref "IC10") (pin "48") (pinfunction "PB2_48") (pintype "bidirectional"))
    )
    (net (code "256") (name "unconnected-(IC10-PB3-Pad133)") (class "Default")
      (node (ref "IC10") (pin "133") (pinfunction "PB3_133") (pintype "bidirectional"))
    )
    (net (code "257") (name "unconnected-(IC10-PB8-Pad139)") (class "Default")
      (node (ref "IC10") (pin "139") (pinfunction "PB8_139") (pintype "bidirectional"))
    )
    (net (code "258") (name "unconnected-(IC10-PB9-Pad140)") (class "Default")
      (node (ref "IC10") (pin "140") (pinfunction "PB9_140") (pintype "bidirectional"))
    )
    (net (code "259") (name "unconnected-(IC10-PB11-Pad70)") (class "Default")
      (node (ref "IC10") (pin "70") (pinfunction "PB11_70") (pintype "bidirectional"))
    )
    (net (code "260") (name "unconnected-(IC10-PC2-Pad28)") (class "Default")
      (node (ref "IC10") (pin "28") (pinfunction "PC2_28") (pintype "bidirectional"))
    )
    (net (code "261") (name "unconnected-(IC10-PC13-Pad7)") (class "Default")
      (node (ref "IC10") (pin "7") (pinfunction "PC13_7") (pintype "bidirectional"))
    )
    (net (code "262") (name "unconnected-(IC10-PD0-Pad114)") (class "Default")
      (node (ref "IC10") (pin "114") (pinfunction "PD0_114") (pintype "bidirectional"))
    )
    (net (code "263") (name "unconnected-(IC10-PD3-Pad117)") (class "Default")
      (node (ref "IC10") (pin "117") (pinfunction "PD3_117") (pintype "bidirectional"))
    )
    (net (code "264") (name "unconnected-(IC10-PD4-Pad118)") (class "Default")
      (node (ref "IC10") (pin "118") (pinfunction "PD4_118") (pintype "bidirectional"))
    )
    (net (code "265") (name "unconnected-(IC10-PD5-Pad119)") (class "Default")
      (node (ref "IC10") (pin "119") (pinfunction "PD5_119") (pintype "bidirectional"))
    )
    (net (code "266") (name "unconnected-(IC10-PD13-Pad82)") (class "Default")
      (node (ref "IC10") (pin "82") (pinfunction "PD13_82") (pintype "bidirectional"))
    )
    (net (code "267") (name "unconnected-(IC10-PD14-Pad85)") (class "Default")
      (node (ref "IC10") (pin "85") (pinfunction "PD14_85") (pintype "bidirectional"))
    )
    (net (code "268") (name "unconnected-(IC10-PD15-Pad86)") (class "Default")
      (node (ref "IC10") (pin "86") (pinfunction "PD15_86") (pintype "bidirectional"))
    )
    (net (code "269") (name "unconnected-(IC10-PF0-Pad10)") (class "Default")
      (node (ref "IC10") (pin "10") (pinfunction "PF0_10") (pintype "bidirectional"))
    )
    (net (code "270") (name "unconnected-(IC10-PF1-Pad11)") (class "Default")
      (node (ref "IC10") (pin "11") (pinfunction "PF1_11") (pintype "bidirectional"))
    )
    (net (code "271") (name "unconnected-(IC10-PF2-Pad12)") (class "Default")
      (node (ref "IC10") (pin "12") (pinfunction "PF2_12") (pintype "bidirectional"))
    )
    (net (code "272") (name "unconnected-(IC10-PF3-Pad13)") (class "Default")
      (node (ref "IC10") (pin "13") (pinfunction "PF3_13") (pintype "bidirectional"))
    )
    (net (code "273") (name "unconnected-(IC10-PF4-Pad14)") (class "Default")
      (node (ref "IC10") (pin "14") (pinfunction "PF4_14") (pintype "bidirectional"))
    )
    (net (code "274") (name "unconnected-(IC10-PF5-Pad15)") (class "Default")
      (node (ref "IC10") (pin "15") (pinfunction "PF5_15") (pintype "bidirectional"))
    )
    (net (code "275") (name "unconnected-(IC10-PF6-Pad18)") (class "Default")
      (node (ref "IC10") (pin "18") (pinfunction "PF6_18") (pintype "bidirectional"))
    )
    (net (code "276") (name "unconnected-(IC10-PF7-Pad19)") (class "Default")
      (node (ref "IC10") (pin "19") (pinfunction "PF7_19") (pintype "bidirectional"))
    )
    (net (code "277") (name "unconnected-(IC10-PF8-Pad20)") (class "Default")
      (node (ref "IC10") (pin "20") (pinfunction "PF8_20") (pintype "bidirectional"))
    )
    (net (code "278") (name "unconnected-(IC10-PF10-Pad22)") (class "Default")
      (node (ref "IC10") (pin "22") (pinfunction "PF10_22") (pintype "bidirectional"))
    )
    (net (code "279") (name "unconnected-(IC10-PF11-Pad49)") (class "Default")
      (node (ref "IC10") (pin "49") (pinfunction "PF11_49") (pintype "bidirectional"))
    )
    (net (code "280") (name "unconnected-(IC10-PF12-Pad50)") (class "Default")
      (node (ref "IC10") (pin "50") (pinfunction "PF12_50") (pintype "bidirectional"))
    )
    (net (code "281") (name "unconnected-(IC10-PF13-Pad53)") (class "Default")
      (node (ref "IC10") (pin "53") (pinfunction "PF13_53") (pintype "bidirectional"))
    )
    (net (code "282") (name "unconnected-(IC10-PF14-Pad54)") (class "Default")
      (node (ref "IC10") (pin "54") (pinfunction "PF14_54") (pintype "bidirectional"))
    )
    (net (code "283") (name "unconnected-(IC10-PF15-Pad55)") (class "Default")
      (node (ref "IC10") (pin "55") (pinfunction "PF15_55") (pintype "bidirectional"))
    )
    (net (code "284") (name "unconnected-(IC10-PG4-Pad89)") (class "Default")
      (node (ref "IC10") (pin "89") (pinfunction "PG4_89") (pintype "bidirectional"))
    )
    (net (code "285") (name "unconnected-(IC10-PG5-Pad90)") (class "Default")
      (node (ref "IC10") (pin "90") (pinfunction "PG5_90") (pintype "bidirectional"))
    )
    (net (code "286") (name "unconnected-(IC10-PG8-Pad93)") (class "Default")
      (node (ref "IC10") (pin "93") (pinfunction "PG8_93") (pintype "bidirectional"))
    )
    (net (code "287") (name "unconnected-(IC10-PG14-Pad129)") (class "Default")
      (node (ref "IC10") (pin "129") (pinfunction "PG14_129") (pintype "bidirectional"))
    )
    (net (code "288") (name "unconnected-(IC12-Pad4)") (class "Default")
      (node (ref "IC12") (pin "4") (pinfunction "4_4") (pintype "bidirectional"))
    )
    (net (code "289") (name "unconnected-(J1-Pad4)") (class "Default")
      (node (ref "J1") (pin "4") (pinfunction "4_4") (pintype "bidirectional"))
    )
    (net (code "290") (name "unconnected-(J1-Pad5)") (class "Default")
      (node (ref "J1") (pin "5") (pinfunction "5_5") (pintype "bidirectional"))
    )
    (net (code "291") (name "unconnected-(K7C-O-PadQ2)") (class "Default")
      (node (ref "K7") (pin "Q2") (pinfunction "O_Q2") (pintype "passive"))
    )
    (net (code "292") (name "unconnected-(K7C-P-PadP2)") (class "Default")
      (node (ref "K7") (pin "P2") (pinfunction "P_P2") (pintype "passive"))
    )
    (net (code "293") (name "unconnected-(K7C-S-PadS2)") (class "Default")
      (node (ref "K7") (pin "S2") (pinfunction "S_S2") (pintype "passive"))
    )
    (net (code "294") (name "unconnected-(K8C-O-PadQ2)") (class "Default")
      (node (ref "K8") (pin "Q2") (pinfunction "O_Q2") (pintype "passive"))
    )
    (net (code "295") (name "unconnected-(K8C-P-PadP2)") (class "Default")
      (node (ref "K8") (pin "P2") (pinfunction "P_P2") (pintype "passive"))
    )
    (net (code "296") (name "unconnected-(K8C-S-PadS2)") (class "Default")
      (node (ref "K8") (pin "S2") (pinfunction "S_S2") (pintype "passive"))
    )
    (net (code "297") (name "unconnected-(T1-NC_1-Pad4)") (class "Default")
      (node (ref "T1") (pin "4") (pinfunction "NC_1_4") (pintype "bidirectional"))
    )
    (net (code "298") (name "unconnected-(T1-NC_2-Pad5)") (class "Default")
      (node (ref "T1") (pin "5") (pinfunction "NC_2_5") (pintype "bidirectional"))
    )
    (net (code "299") (name "unconnected-(T1-NC_3-Pad10)") (class "Default")
      (node (ref "T1") (pin "10") (pinfunction "NC_3_10") (pintype "bidirectional"))
    )
    (net (code "300") (name "unconnected-(T1-NC_5-Pad13)") (class "Default")
      (node (ref "T1") (pin "13") (pinfunction "NC_5_13") (pintype "bidirectional"))
    )
    (net (code "301") (name "unconnected-(U12-IN7-Pad7)") (class "Default")
      (node (ref "U12") (pin "7") (pinfunction "IN7_7") (pintype "bidirectional"))
    )
    (net (code "302") (name "unconnected-(U12-OUT7-Pad10)") (class "Default")
      (node (ref "U12") (pin "10") (pinfunction "OUT7_10") (pintype "bidirectional"))
    )
  )
)
